# TeenyV4.net
KiCad netlist of a schematic drawn in EasyEDA Pro
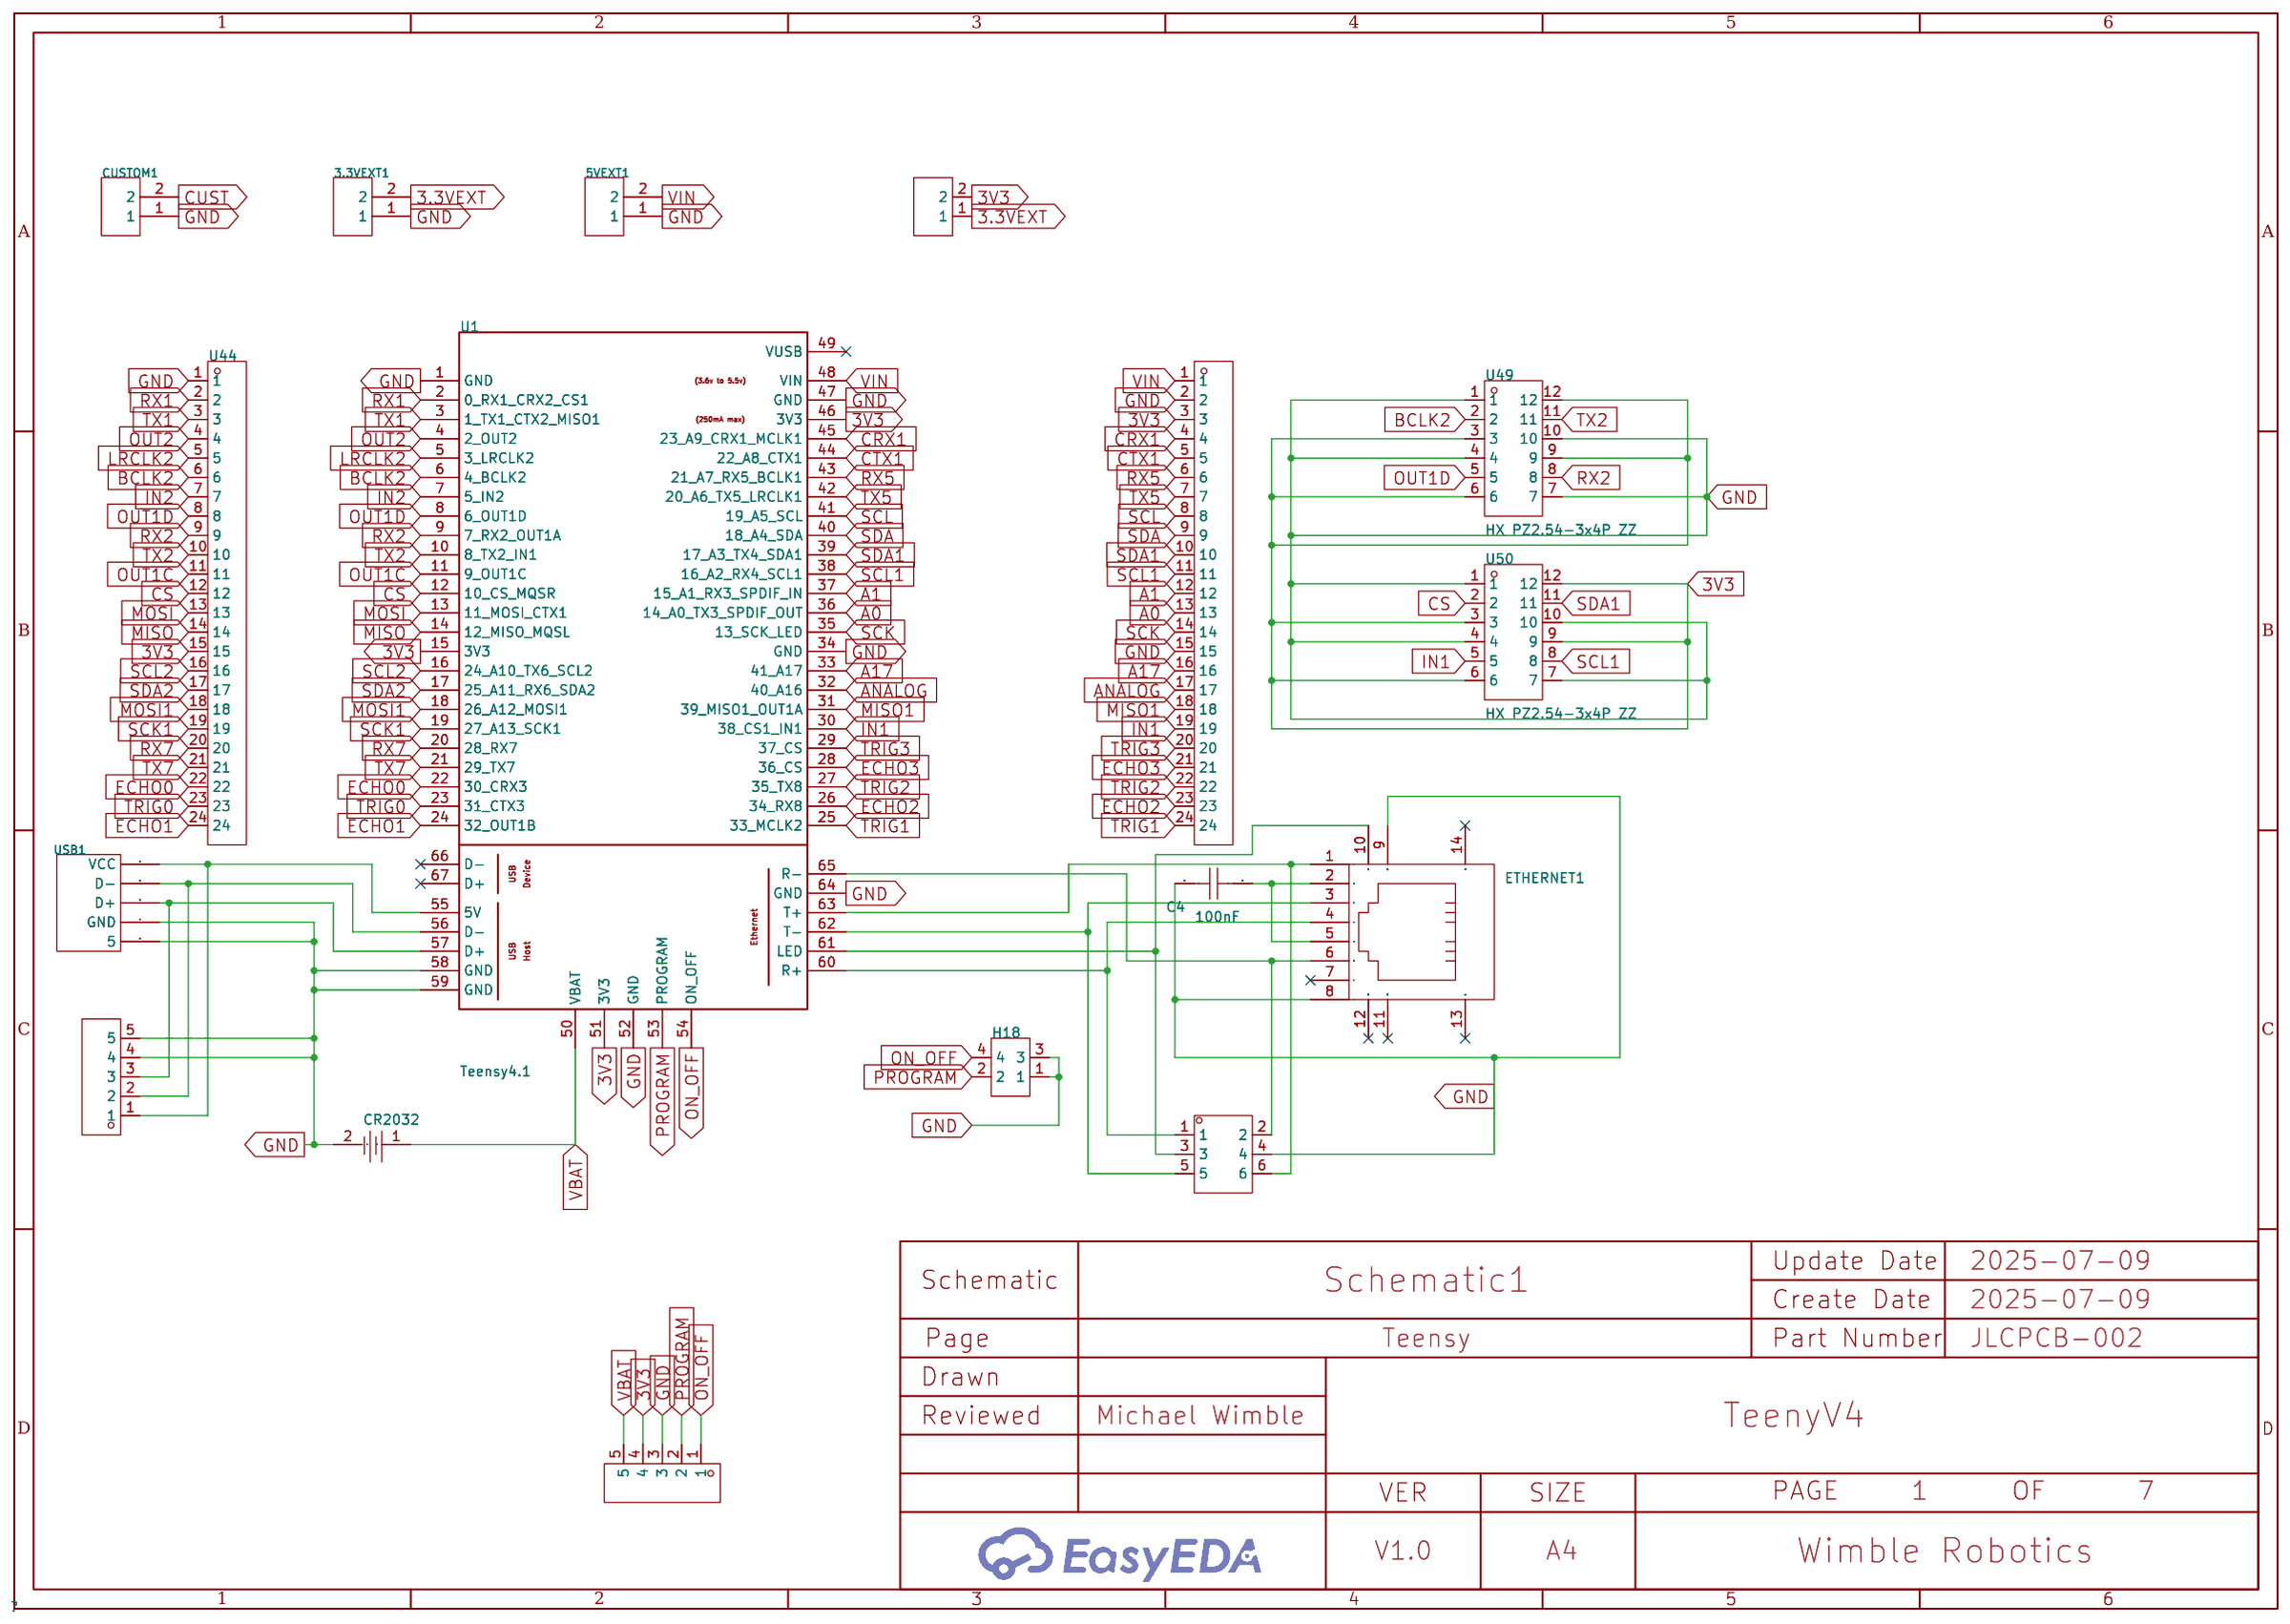
[diagram p0: Teensy]
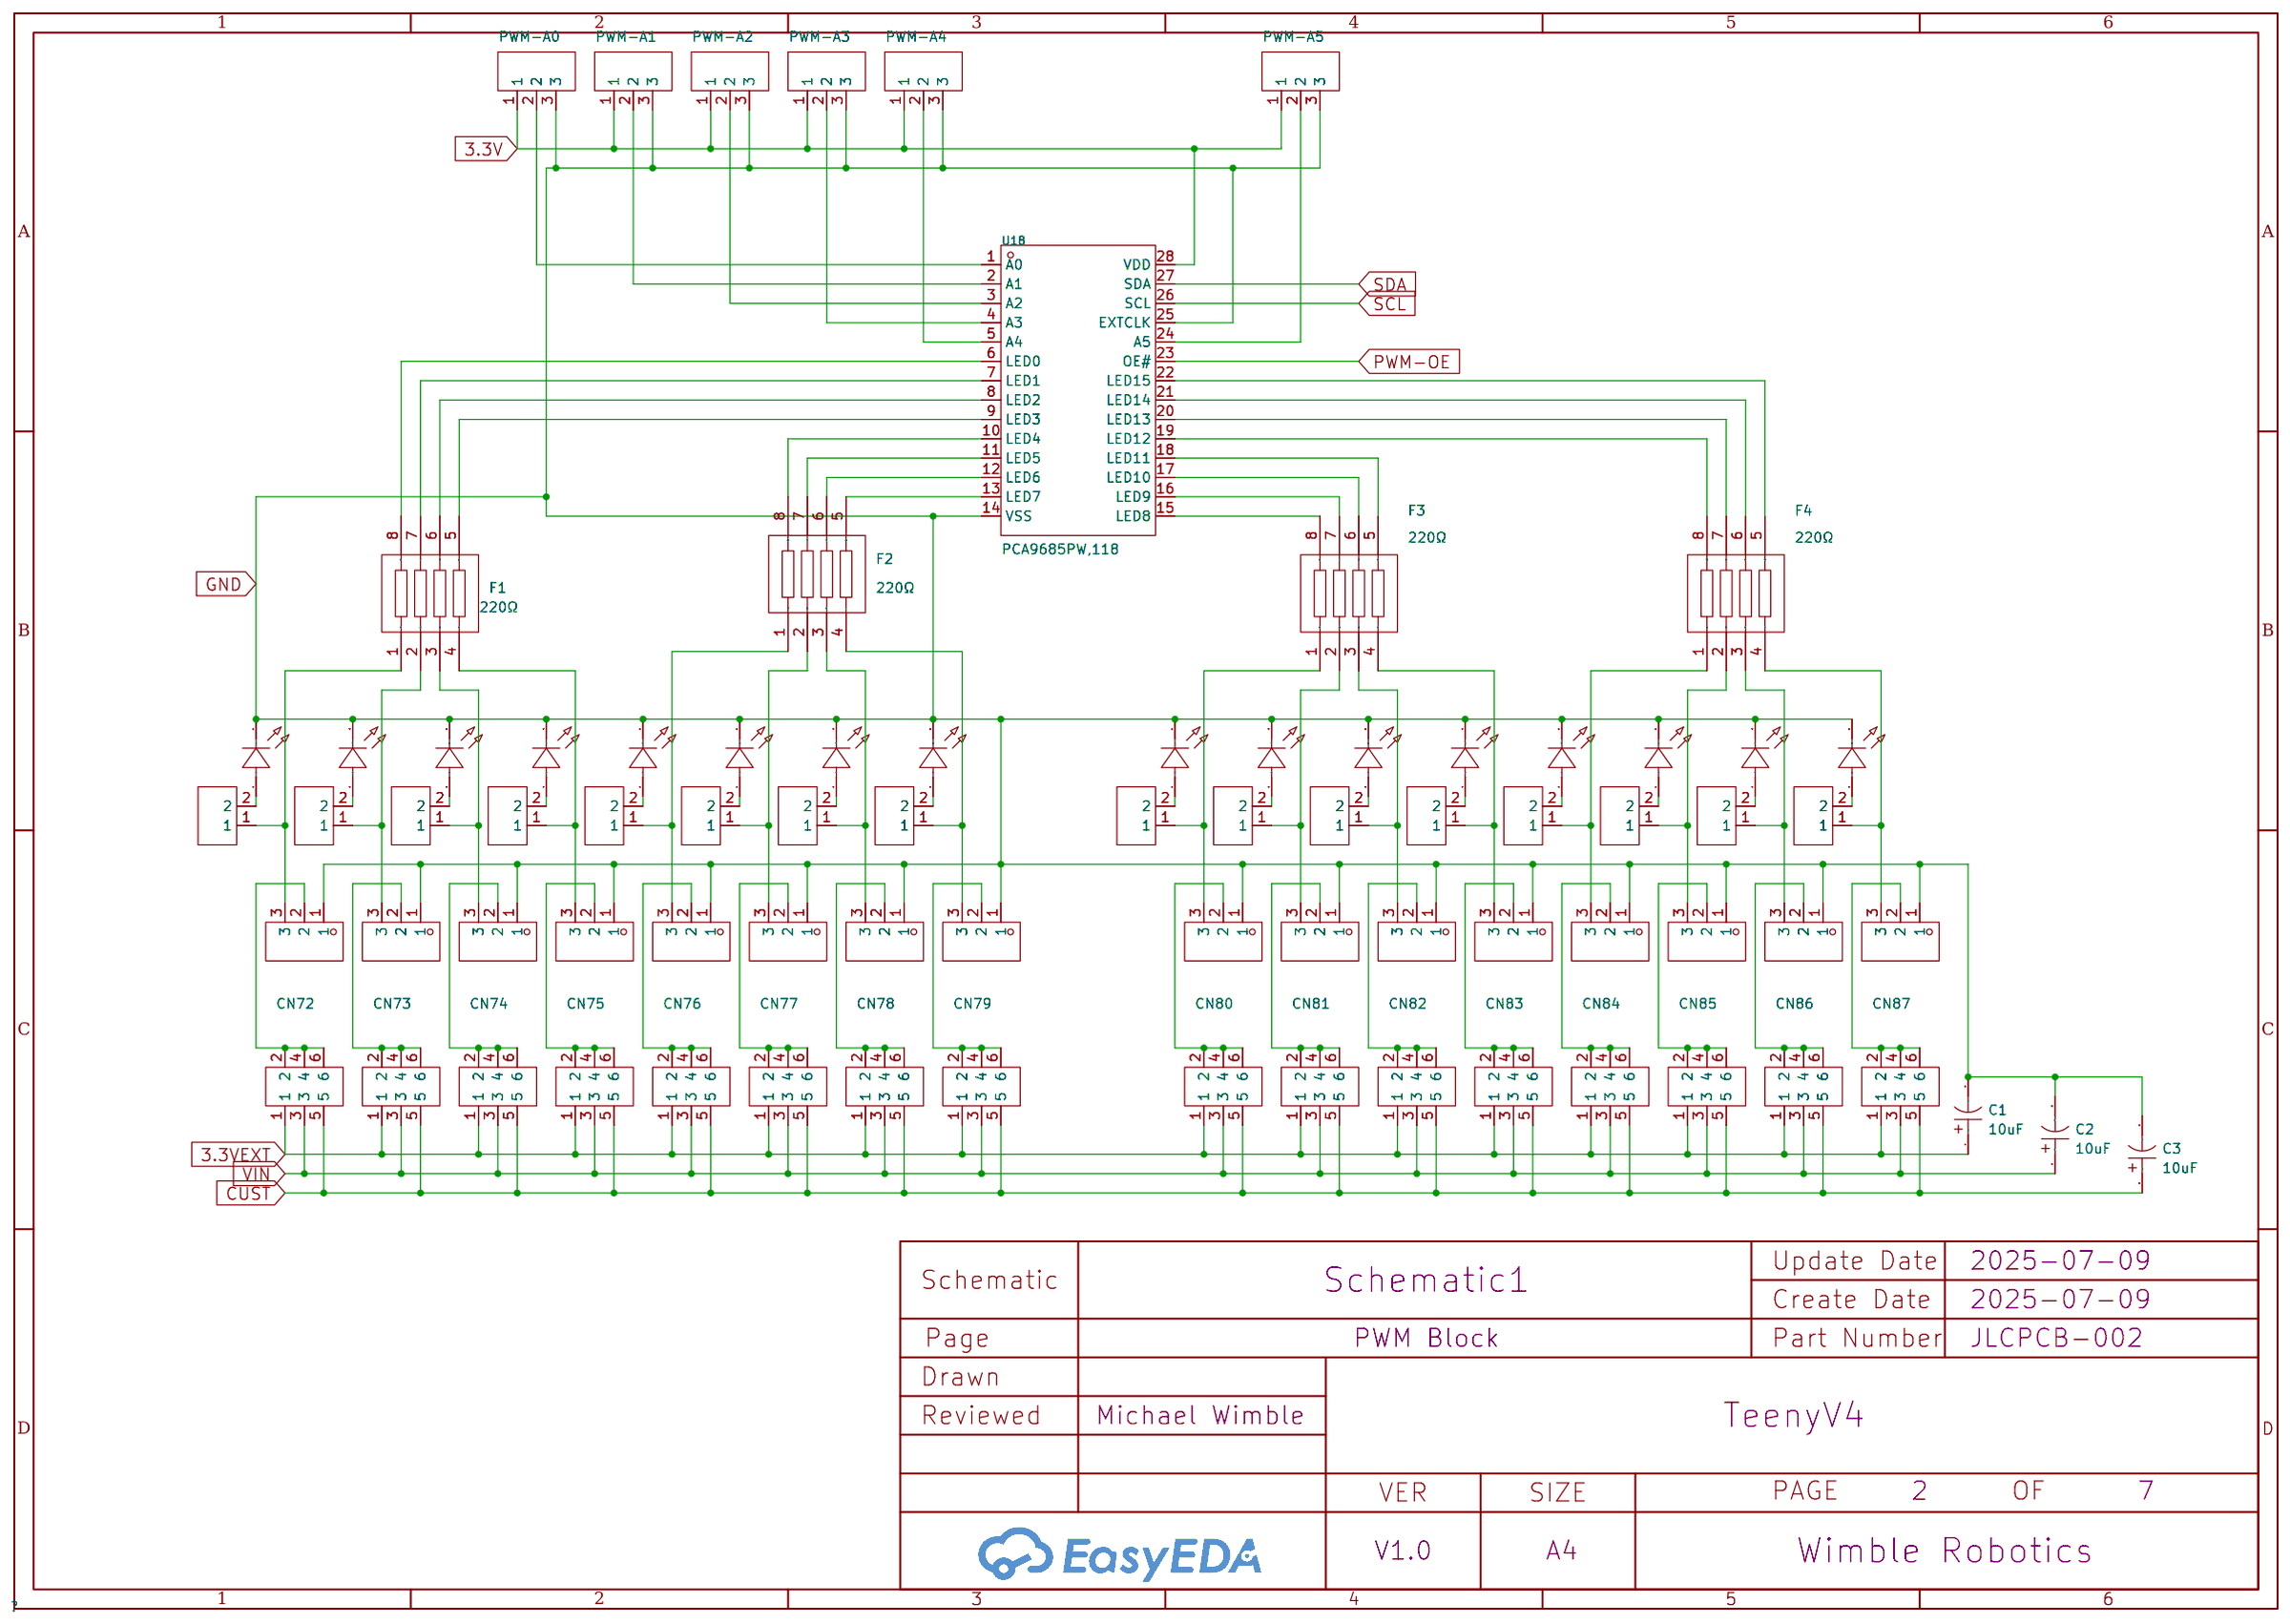
[diagram p1: PWM Block]
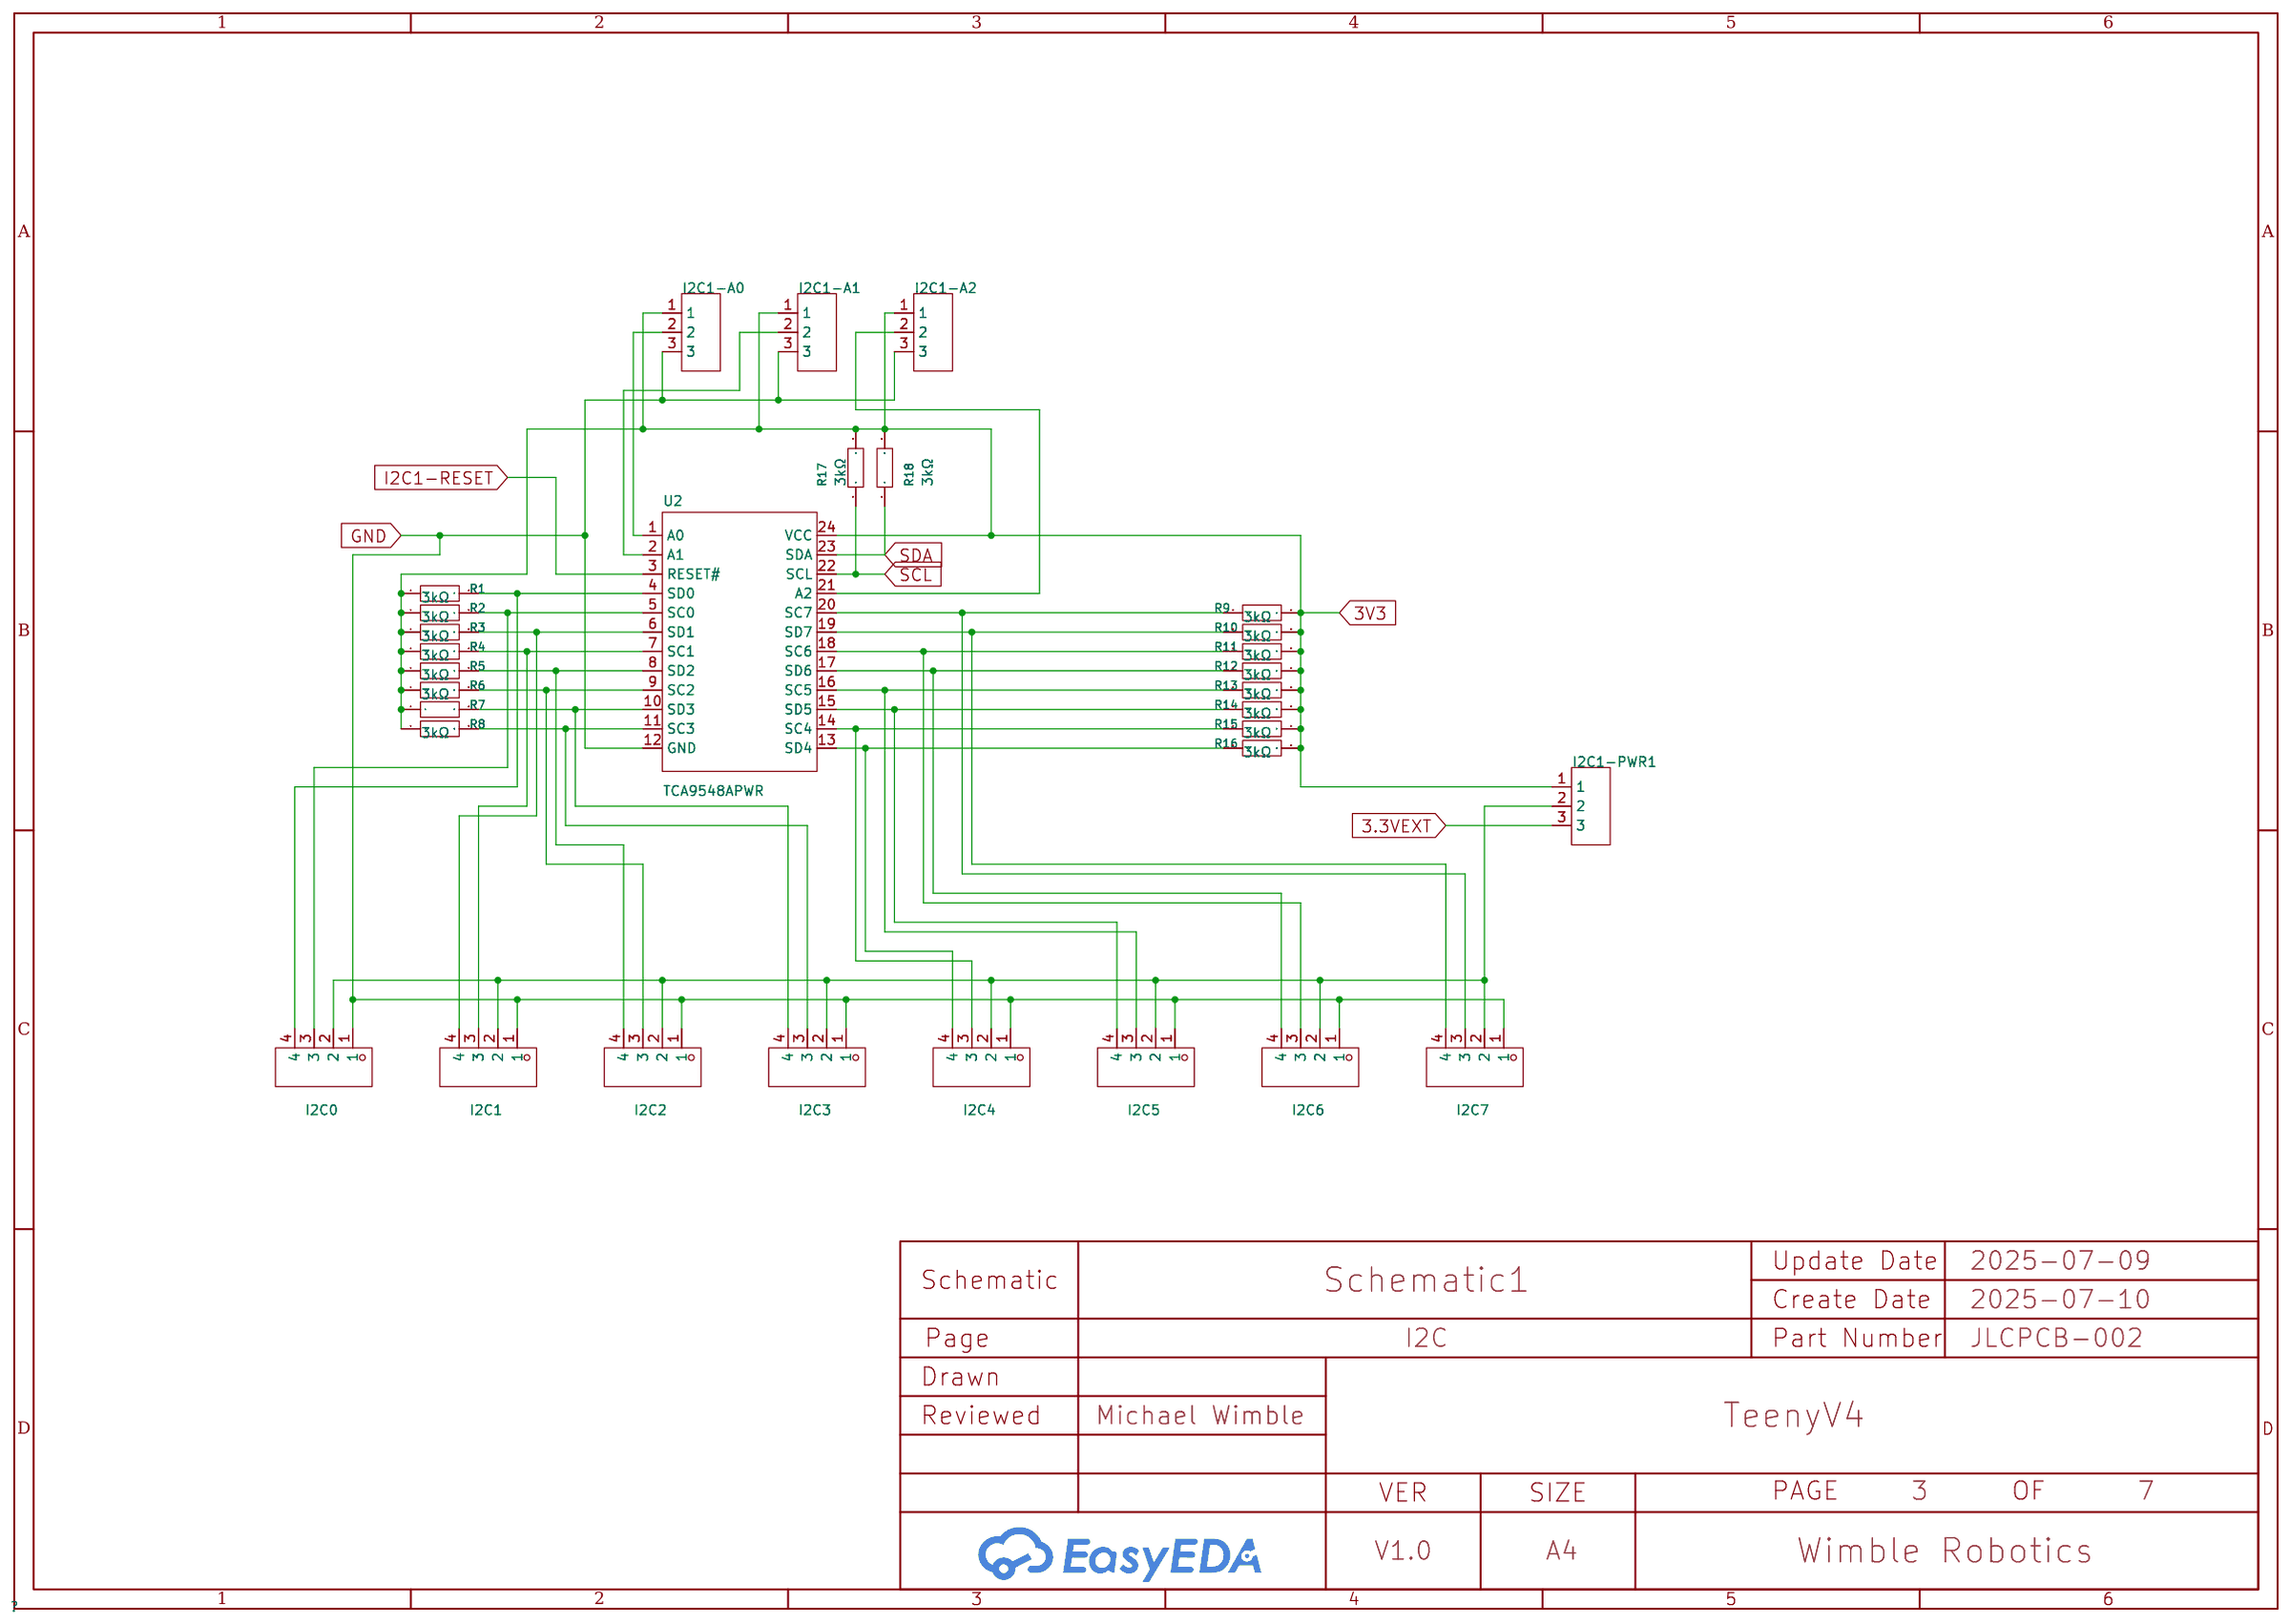
[diagram p2: I2C]
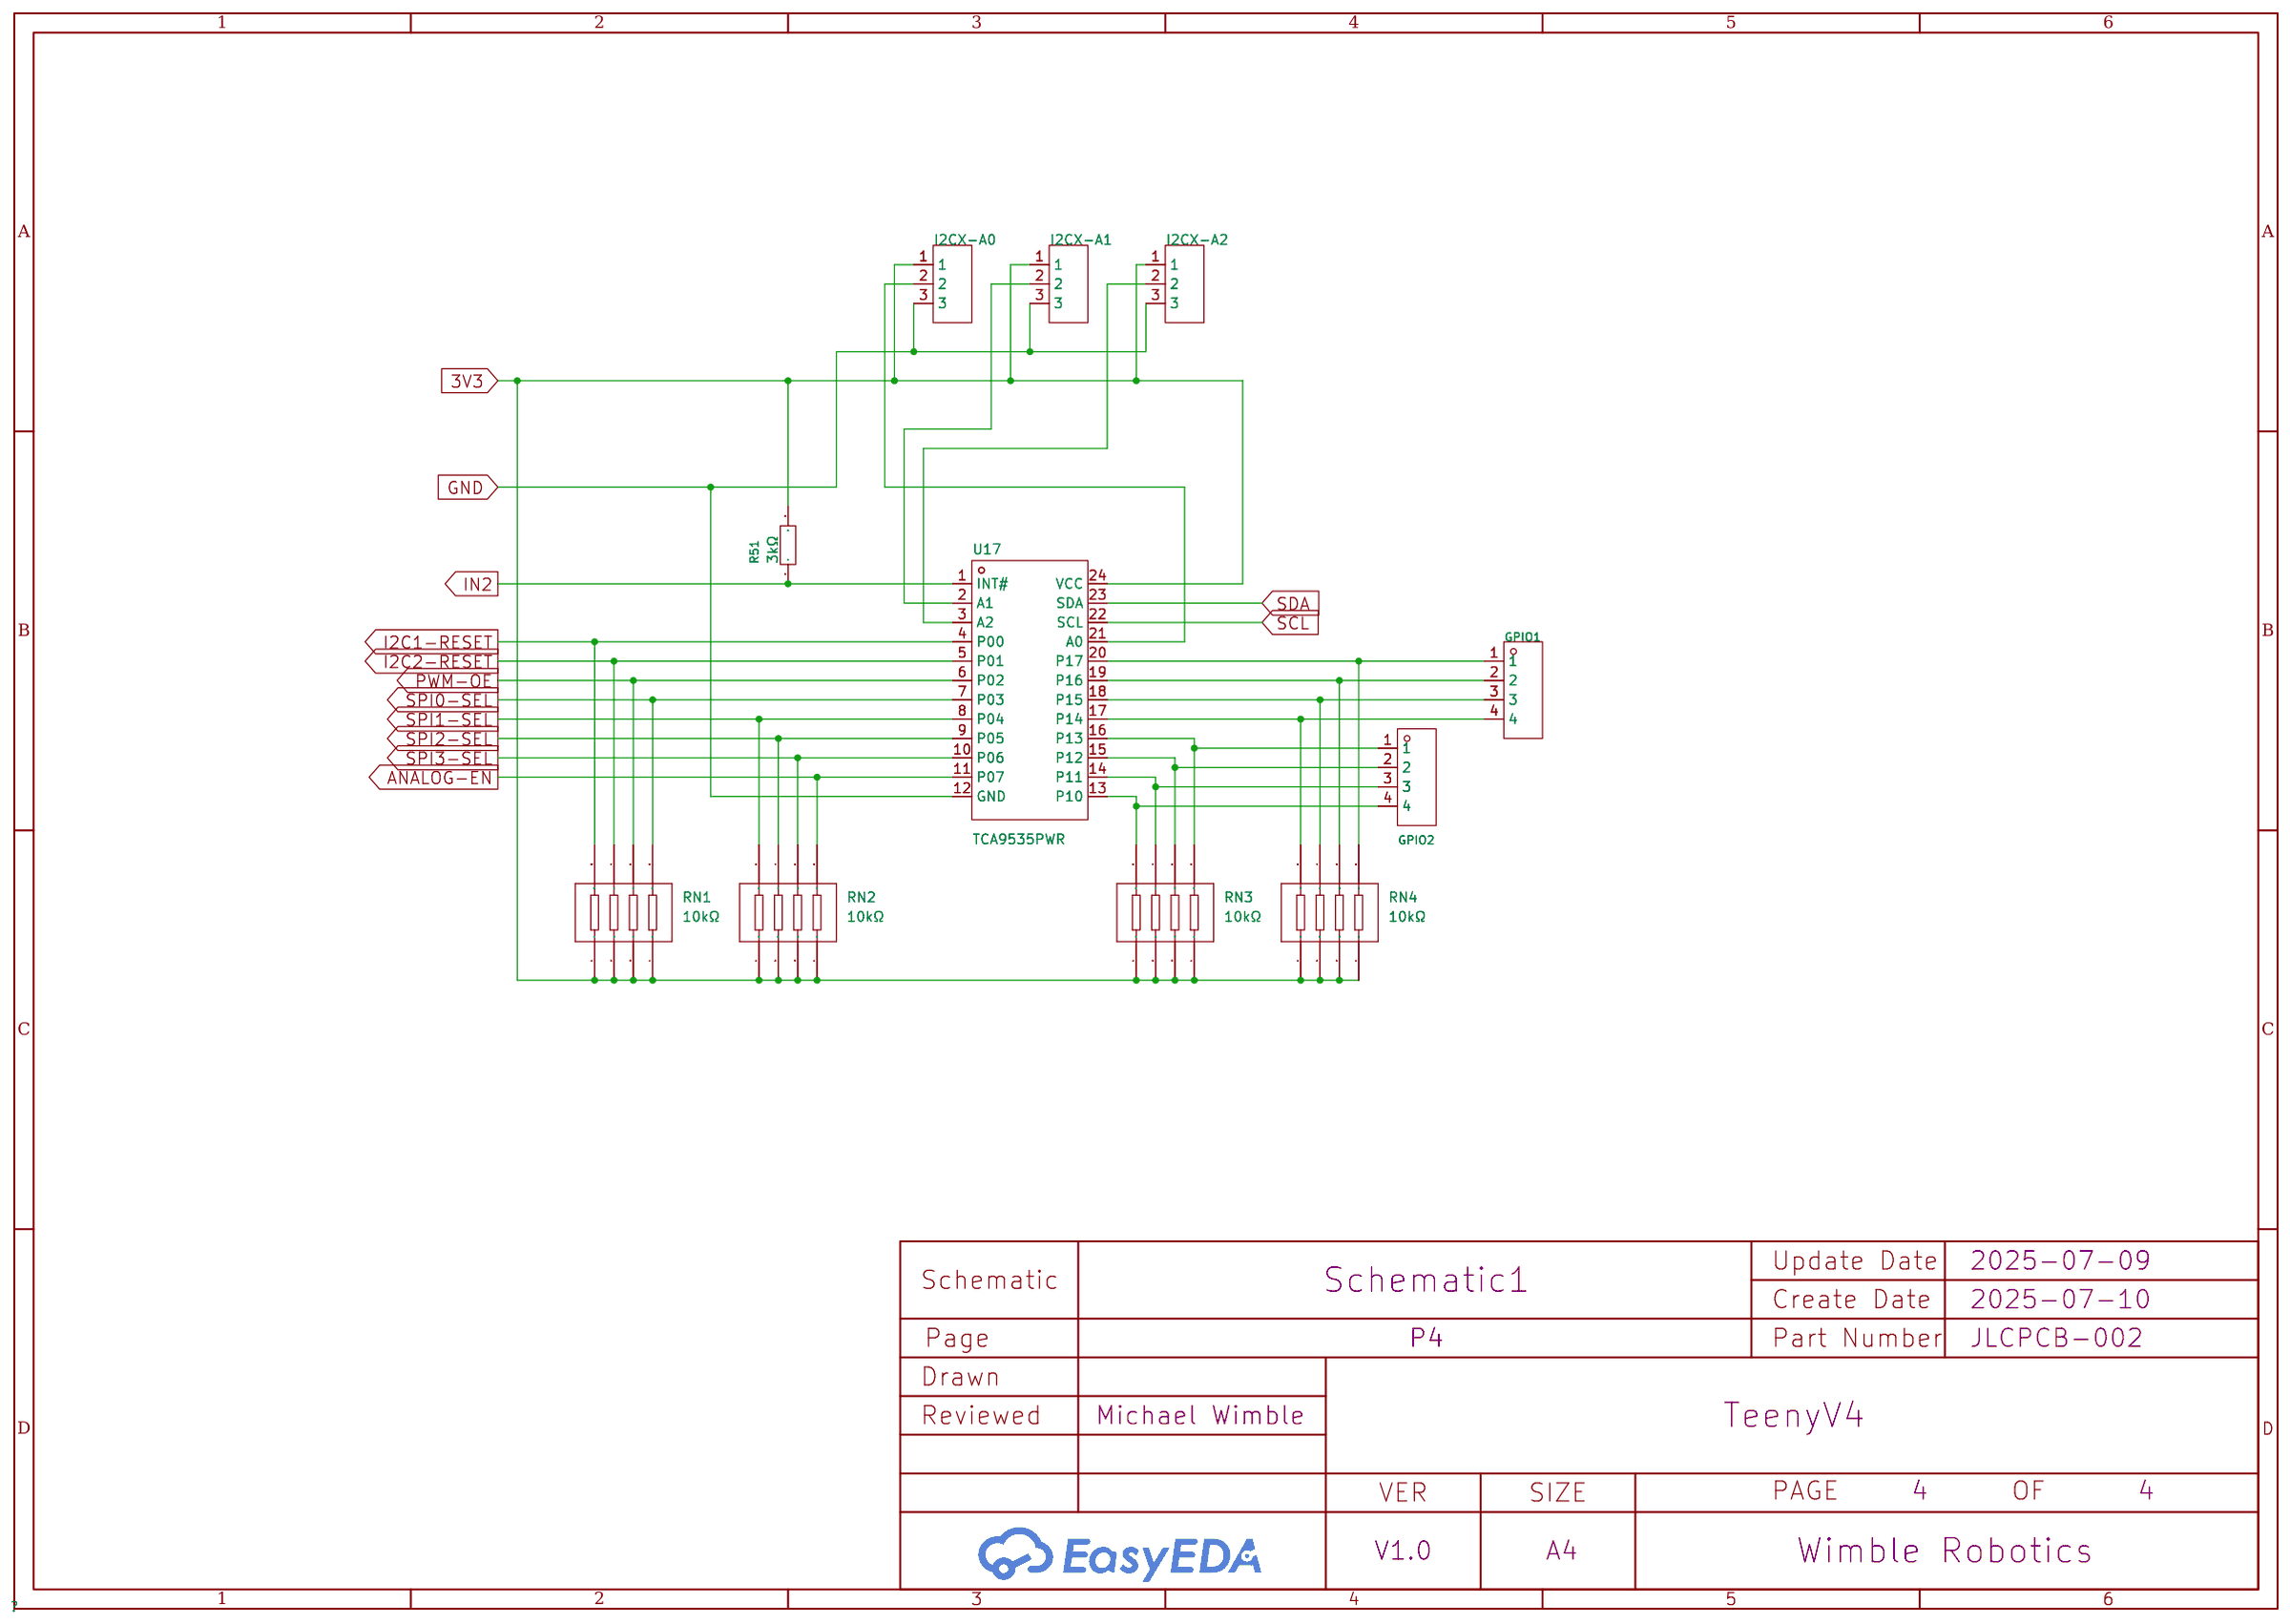
[diagram p3: GPIO]
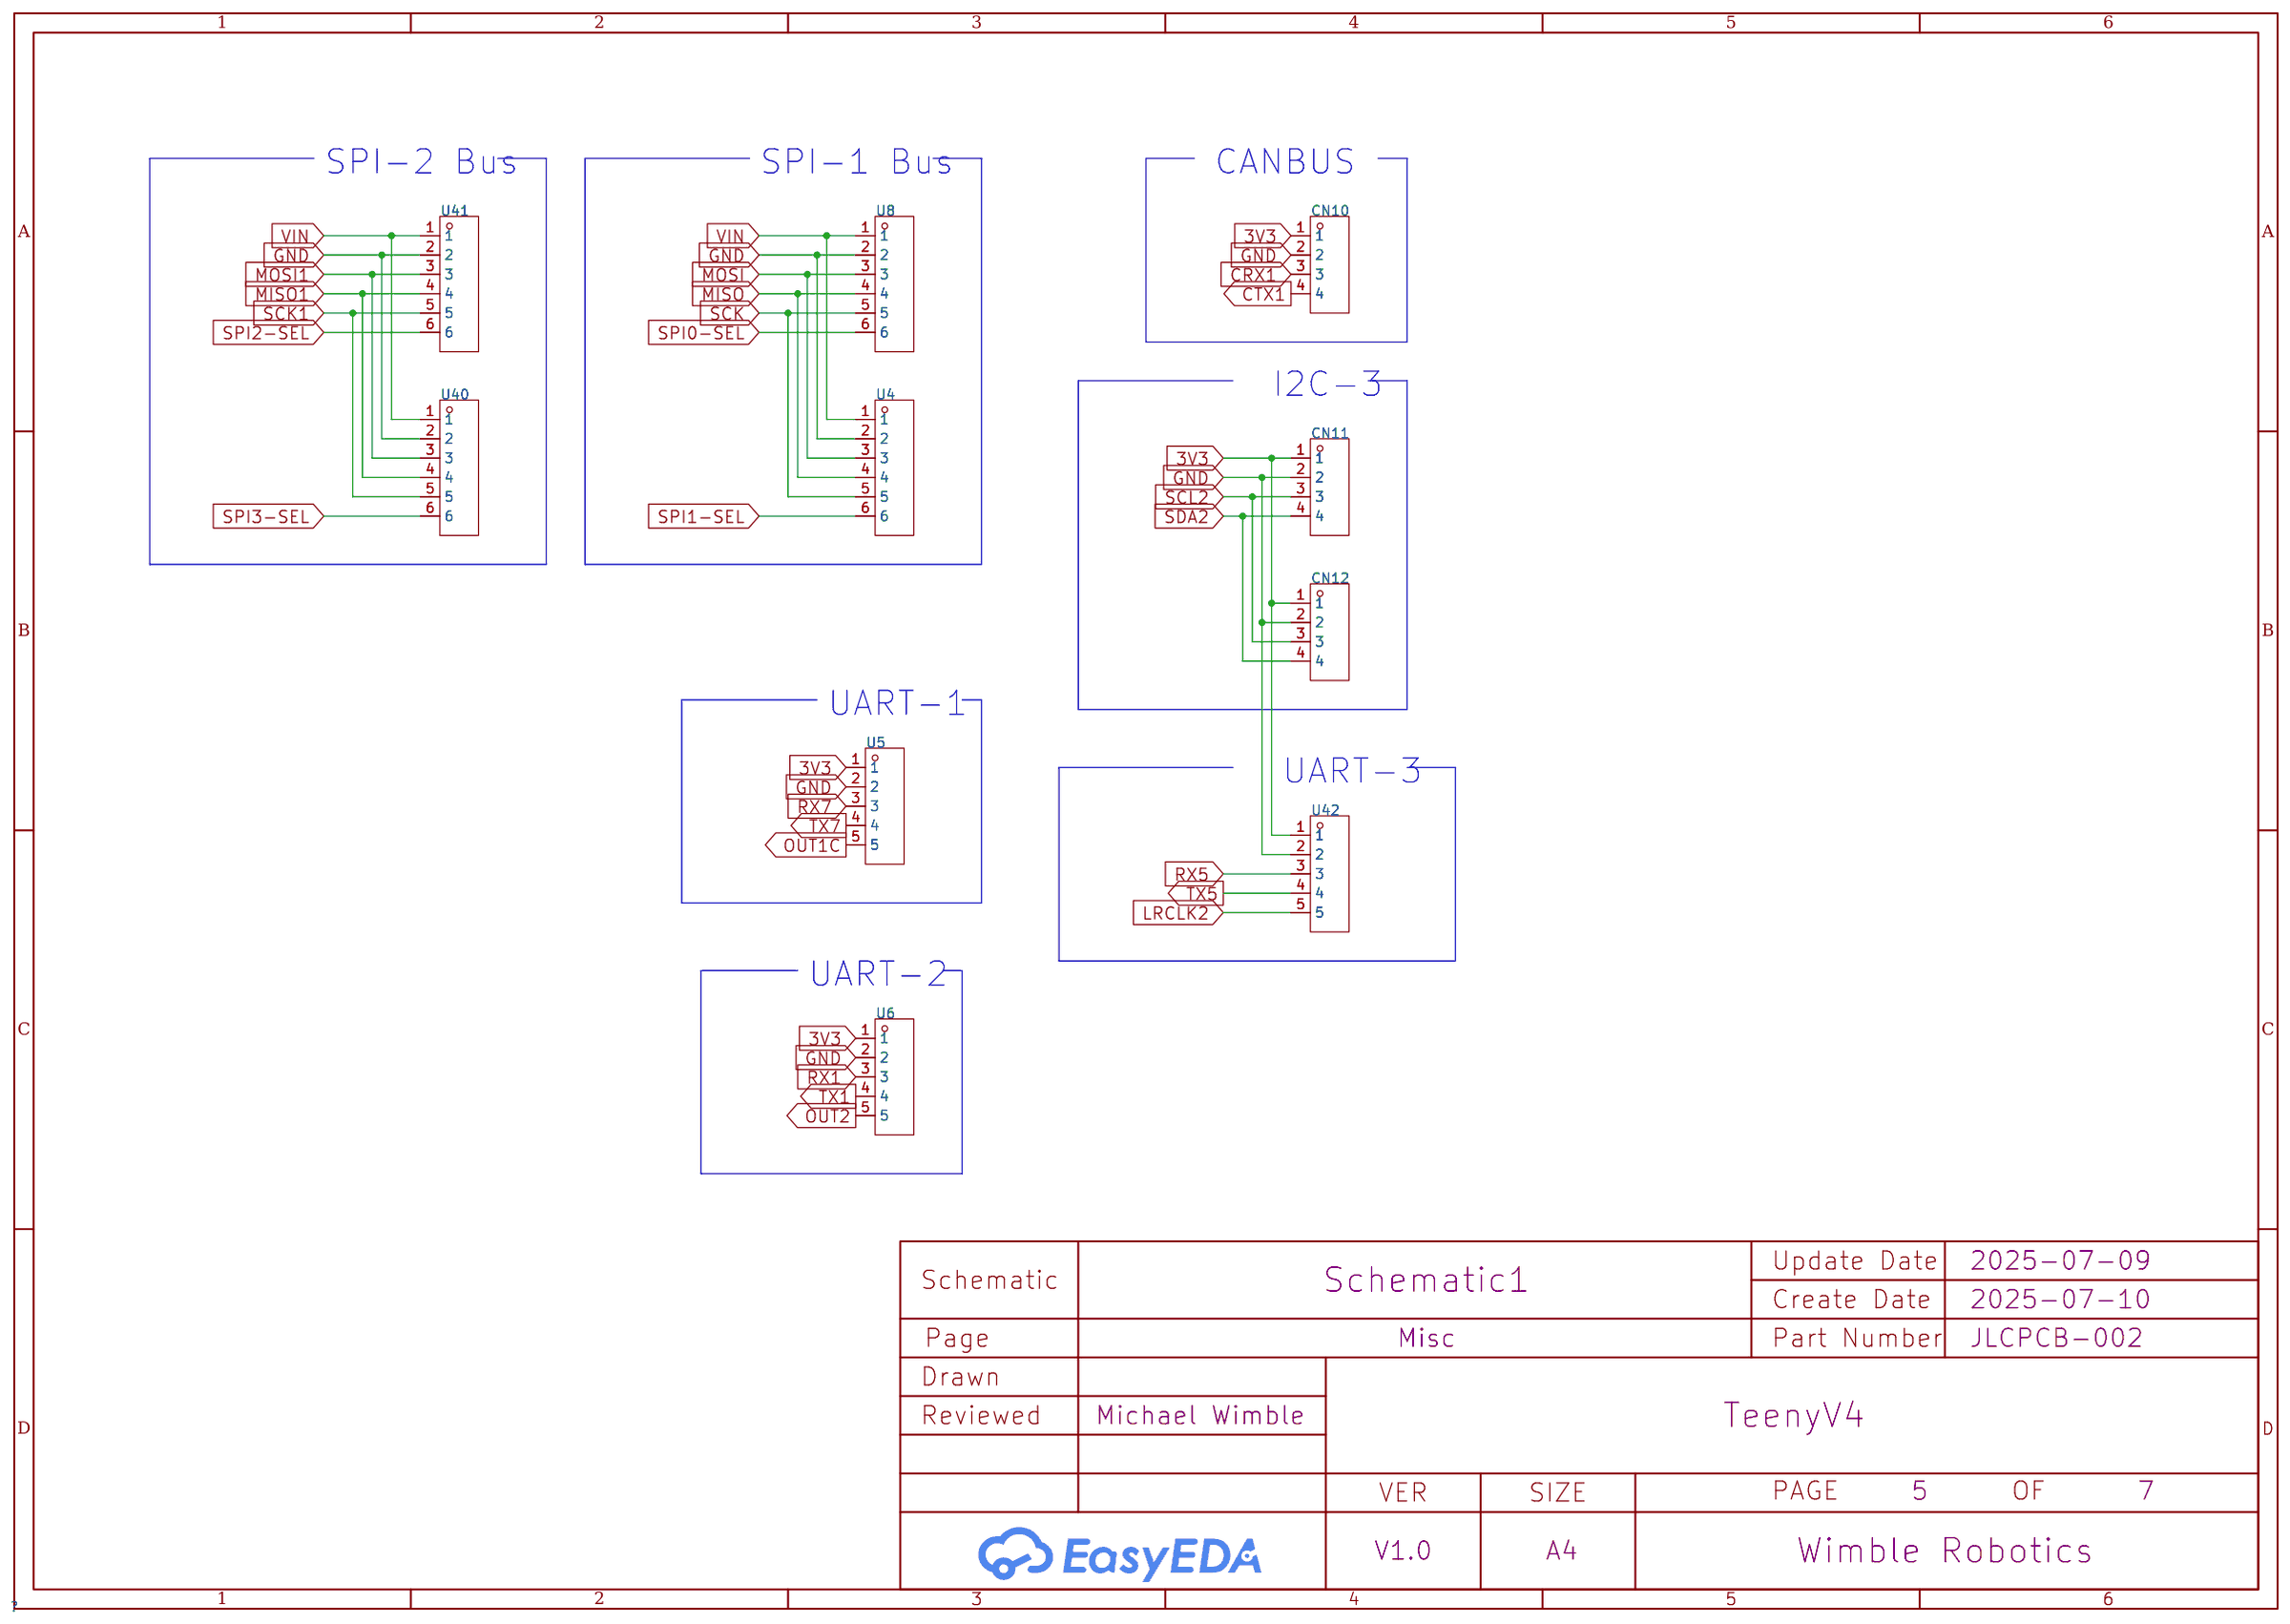
[diagram p4: Misc]
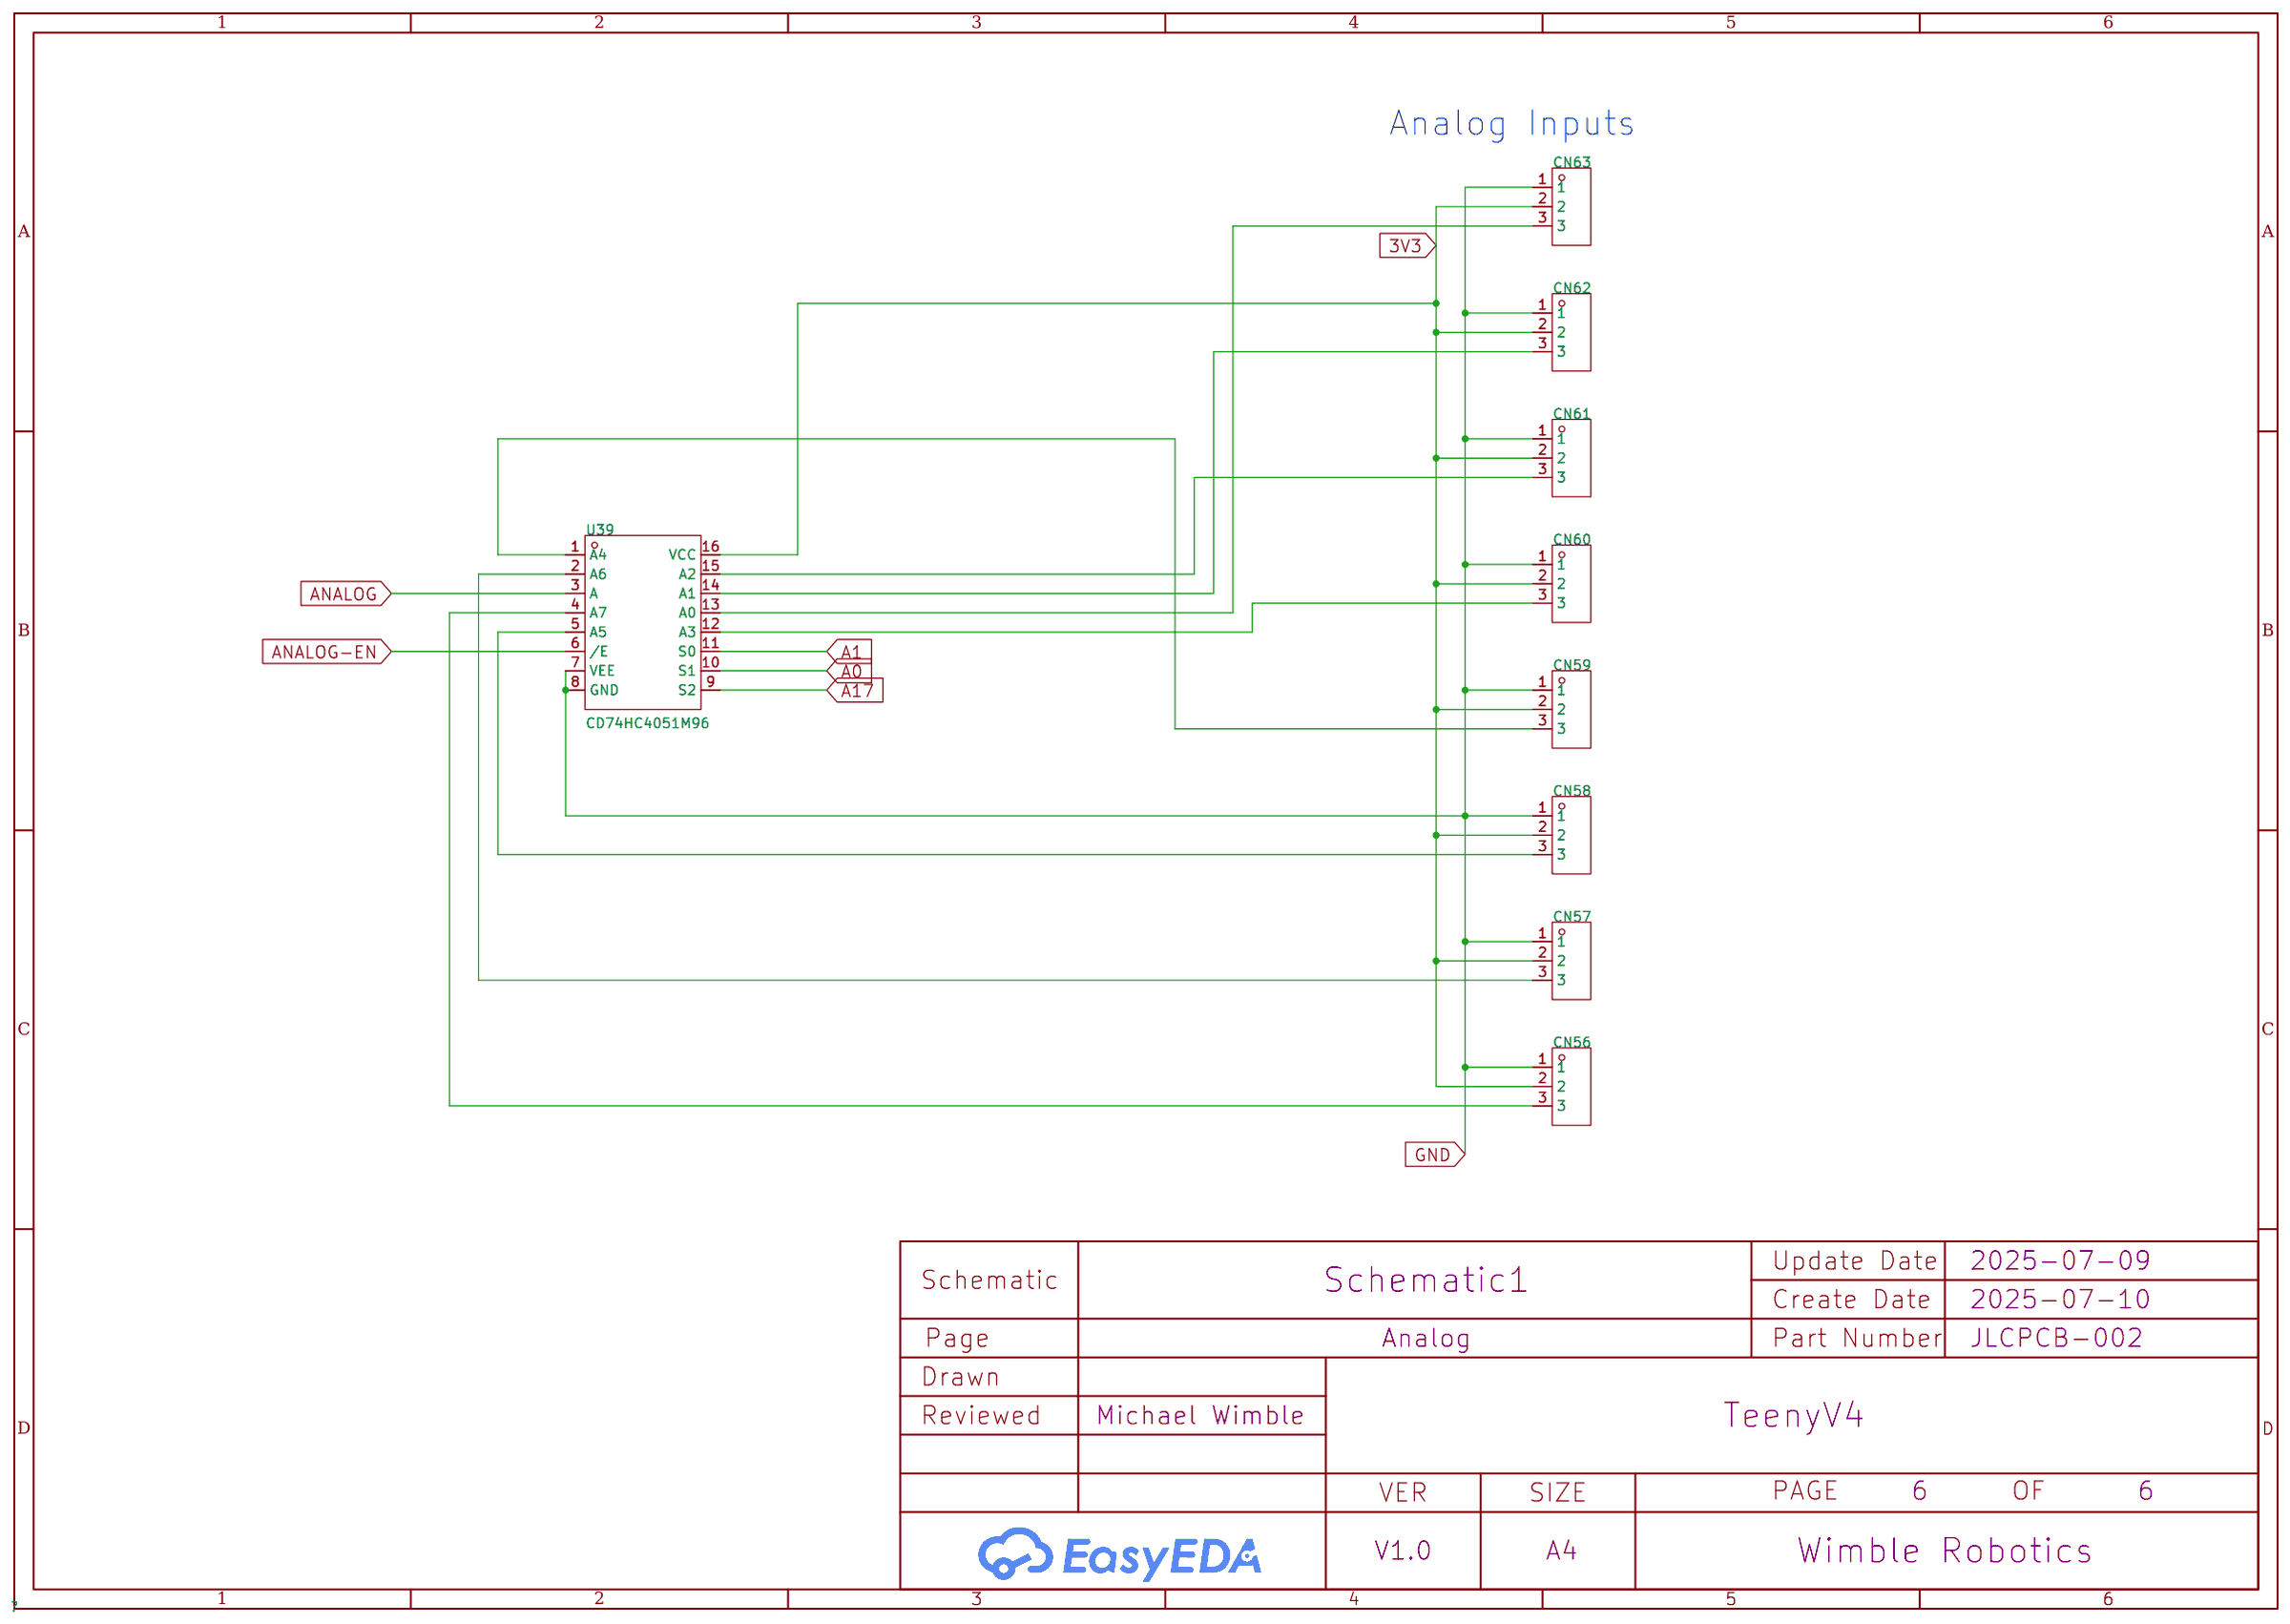
[diagram p5: Analog]
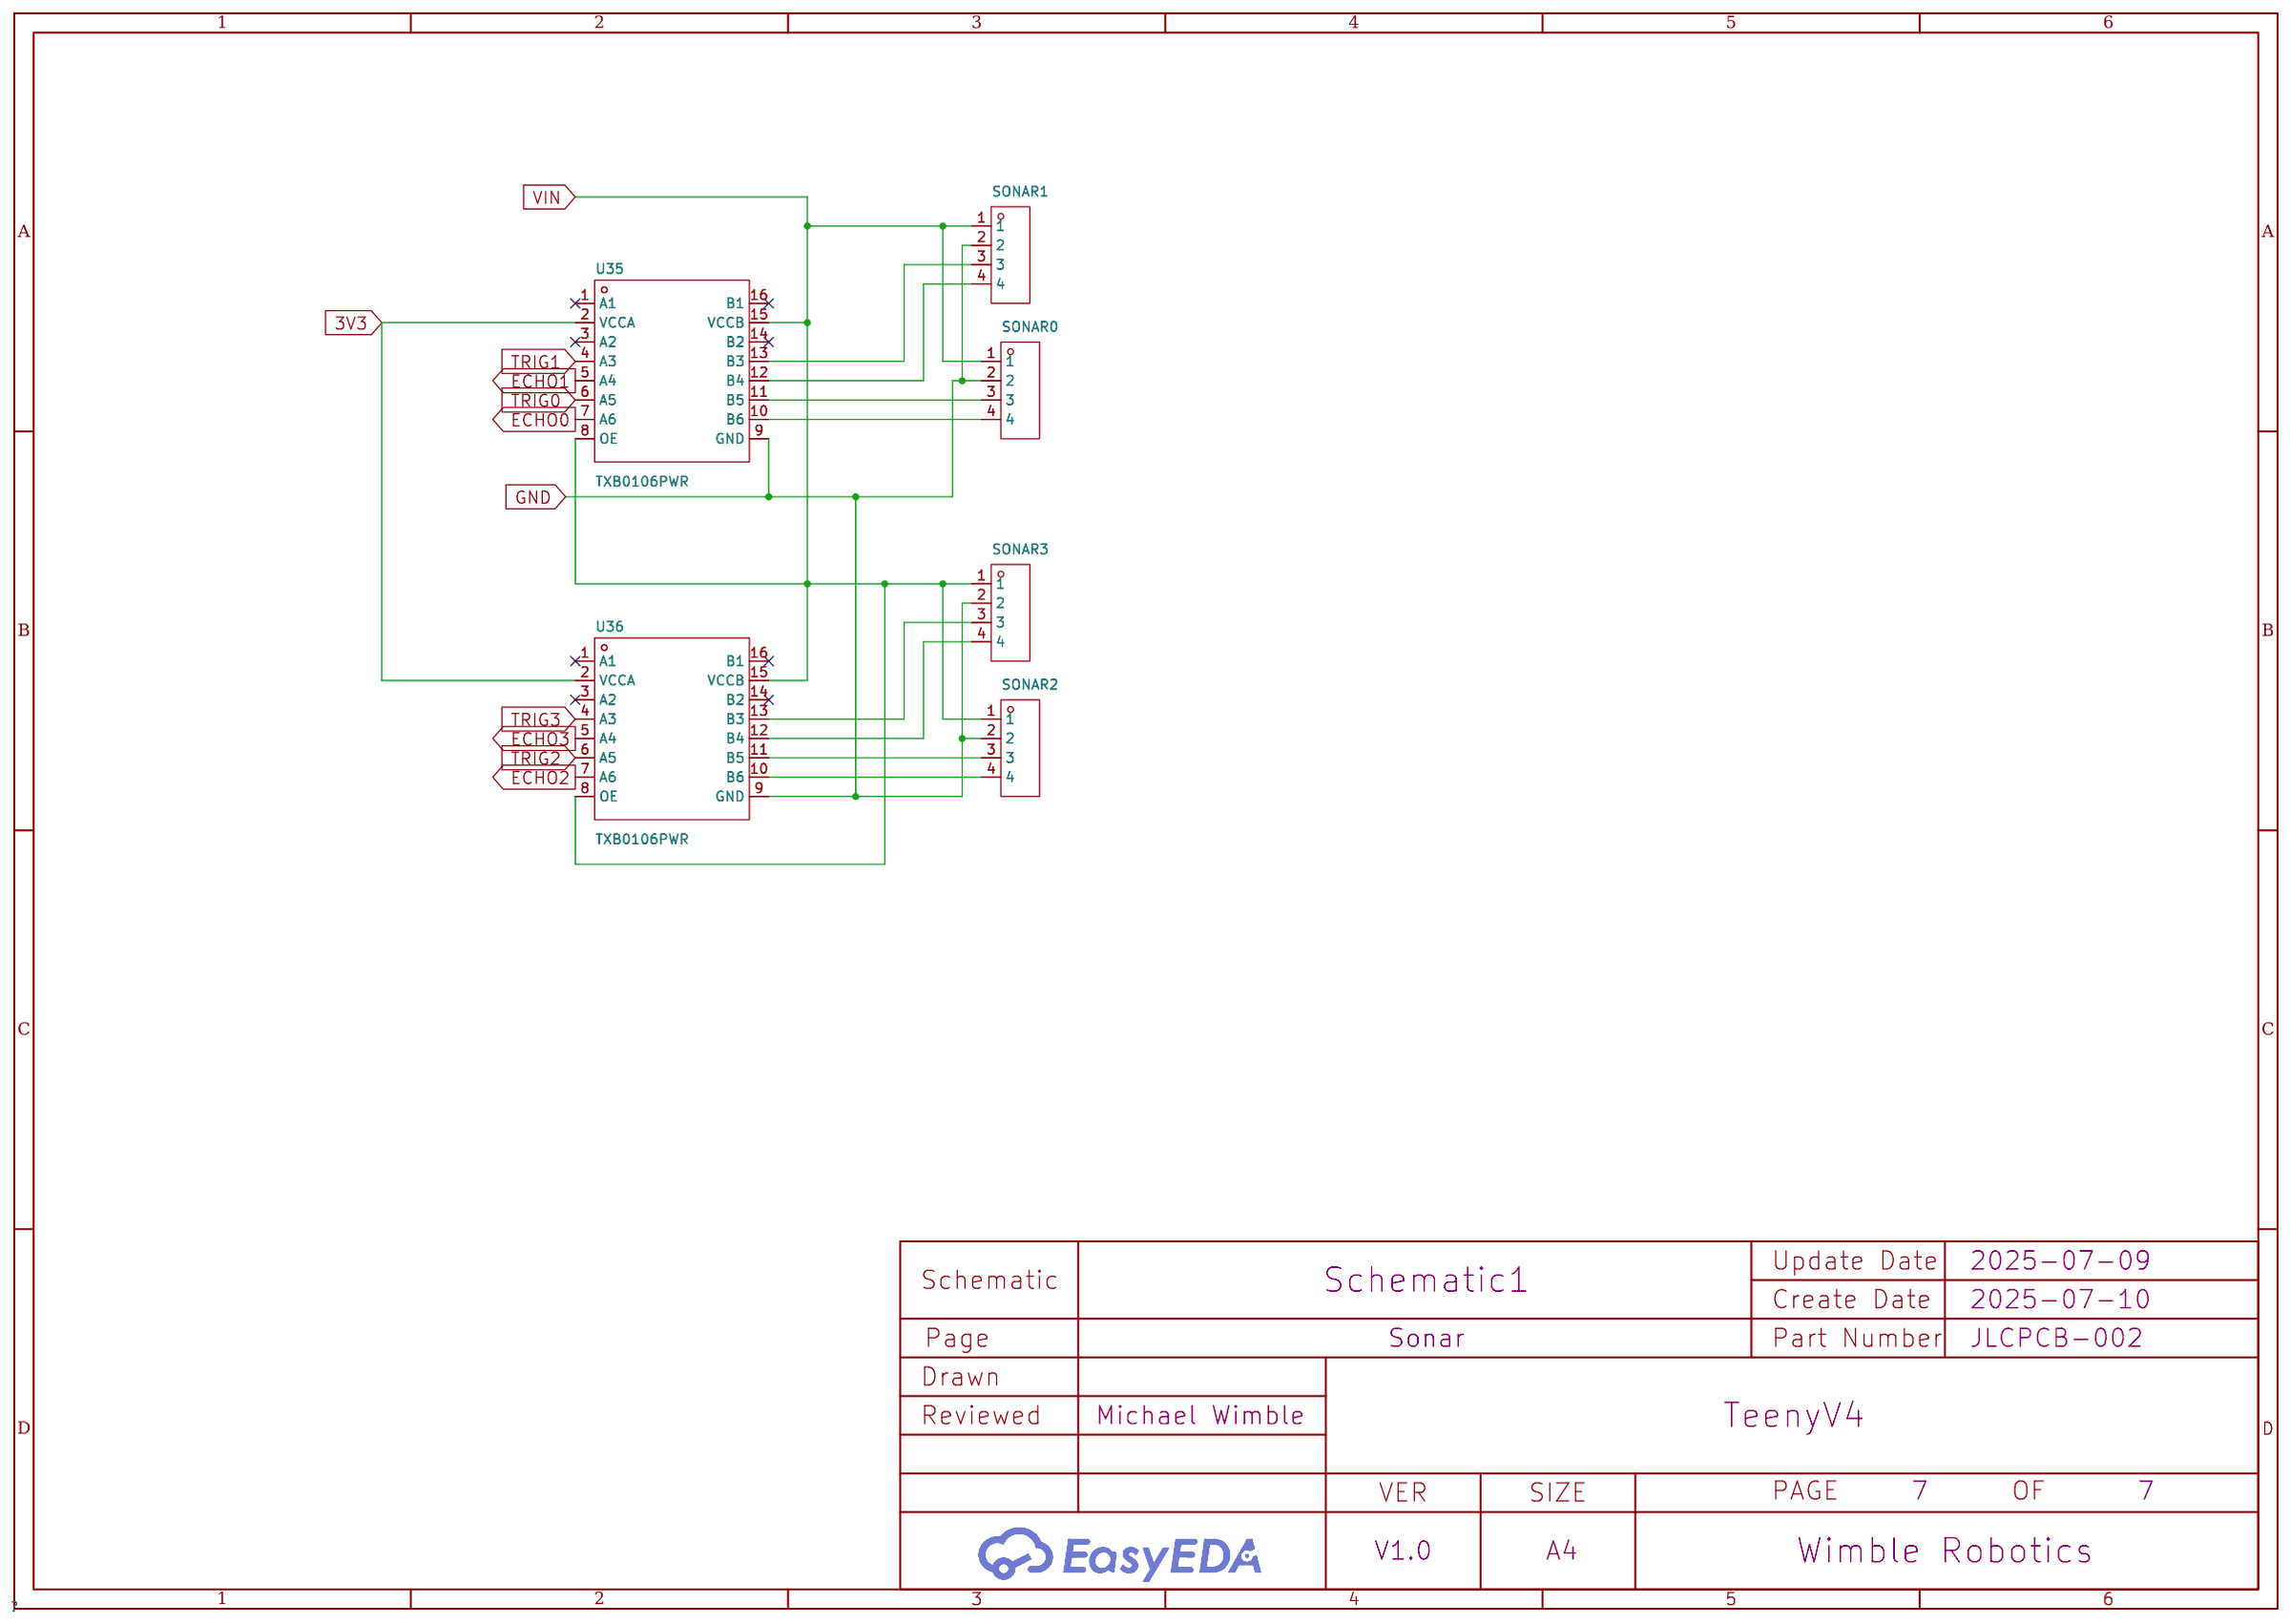
[diagram p6: Sonar]

(export (version "E")
  (design (tool "Eeschema 10.0.6"))
  (components
    (comp (ref "3.3VEXT1")
      (value "WJ127-5.0-2P")
      (footprint "easyedapro:CONN-TH_2P-P5.00_CPC3703CTR")
      (fields (field (name "Manufacturer") "KANGNEX(康奈克斯电气)"))
      (libsource (lib "easyedapro") (part "WJ127-5.0-2P"))
    )
    (comp (ref "5VEXT1")
      (value "WJ127-5.0-2P")
      (footprint "easyedapro:CONN-TH_2P-P5.00_CPC3703CTR")
      (fields (field (name "Manufacturer") "KANGNEX(康奈克斯电气)"))
      (libsource (lib "easyedapro") (part "WJ127-5.0-2P"))
    )
    (comp (ref "C4")
      (value "100nF")
      (footprint "easyedapro:C0805")
      (description "Capacitance:100nF Tolerance:±10% Tolerance:±10% Voltage Rating:50V Temperature Coefficient:-")
      (fields
        (field (name "Manufacturer Part") "CT41G-0805-2X1-50V-0.1μF-K(N)")
        (field (name "Manufacturer") "TORCH(火炬)")
      )
      (libsource (lib "easyedapro") (part "CT41G-0805-2X1-50V-0.1UF-K(N)"))
    )
    (comp (ref "CR2032")
      (value "CR2032-BS-6")
      (footprint "easyedapro:BAT-TH_CR2032-BS-6-1")
      (fields (field (name "Manufacturer") "LX(连欣科技)"))
      (libsource (lib "easyedapro") (part "CR2032-BS-6"))
    )
    (comp (ref "CUSTOM1")
      (value "WJ127-5.0-2P")
      (footprint "easyedapro:CONN-TH_2P-P5.00_CPC3703CTR")
      (fields (field (name "Manufacturer") "KANGNEX(康奈克斯电气)"))
      (libsource (lib "easyedapro") (part "WJ127-5.0-2P"))
    )
    (comp (ref "ETHERNET1")
      (value "J1B1211CCD")
      (footprint "easyedapro:RJ45-TH_J1B1211CCD")
      (fields (field (name "Manufacturer") "WIZNET"))
      (libsource (lib "easyedapro") (part "J1B1211CCD"))
    )
    (comp (ref "H18")
      (value "HX PZ2.54-2x2P ZZ")
      (footprint "easyedapro:HDR-TH_HX-PZ2.54-2X2P-ZZ")
      (fields (field (name "Manufacturer") "hanxia(韩下)"))
      (libsource (lib "easyedapro") (part "HX PZ2.54-2X2P ZZ"))
    )
    (comp (ref "H19")
      (value "PH-00013")
      (footprint "easyedapro:HDR-TH_2P-P2.54-V-M-R2-C1-S2.54")
      (fields (field (name "Manufacturer") "Liansheng(连盛)"))
      (libsource (lib "easyedapro") (part "PH-00013"))
    )
    (comp (ref "U1")
      (value "Teensy4.1")
      (footprint "easyedapro:Teensy41KiCad")
      (libsource (lib "easyedapro") (part "Teensy4.1"))
    )
    (comp (ref "U43")
      (value "HC-PM254-8.5H-1x24PZ")
      (footprint "easyedapro:HDR-TH_24P-P2.54-V-F")
      (fields (field (name "Manufacturer") "HC(虹成电子)"))
      (libsource (lib "easyedapro") (part "HC-PM254-8.5H-1X24PZ"))
    )
    (comp (ref "U44")
      (value "HC-PM254-8.5H-1x24PZ")
      (footprint "easyedapro:HDR-TH_24P-P2.54-V-F")
      (fields (field (name "Manufacturer") "HC(虹成电子)"))
      (libsource (lib "easyedapro") (part "HC-PM254-8.5H-1X24PZ"))
    )
    (comp (ref "U46")
      (value "PM2.54-1*5")
      (footprint "easyedapro:HDR-TH_5P-P2.54-V-F")
      (fields (field (name "Manufacturer") "ZHOURI(洲日)"))
      (libsource (lib "easyedapro") (part "PM2.54-1*5"))
    )
    (comp (ref "U47")
      (value "2.0-2*3P母")
      (footprint "easyedapro:HDR-TH_6P-P2.00-V-F-R2-C3-S2.00")
      (fields (field (name "Manufacturer") "BOOMELE(博穆精密)"))
      (libsource (lib "easyedapro") (part "2*3P"))
    )
    (comp (ref "U48")
      (value "PM2.54-1*5")
      (footprint "easyedapro:HDR-TH_5P-P2.54-V-F")
      (fields (field (name "Manufacturer") "ZHOURI(洲日)"))
      (libsource (lib "easyedapro") (part "PM2.54-1*5"))
    )
    (comp (ref "U49")
      (value "HX PZ2.54-3x4P ZZ")
      (footprint "easyedapro:HDR-TH_12P-P2.54-V-M-R3-C4-S2.54")
      (fields (field (name "Manufacturer") "hanxia(韩下)"))
      (libsource (lib "easyedapro") (part "HX PZ2.54-3X4P ZZ"))
    )
    (comp (ref "U50")
      (value "HX PZ2.54-3x4P ZZ")
      (footprint "easyedapro:HDR-TH_12P-P2.54-V-M-R3-C4-S2.54")
      (fields (field (name "Manufacturer") "hanxia(韩下)"))
      (libsource (lib "easyedapro") (part "HX PZ2.54-3X4P ZZ"))
    )
    (comp (ref "USB1")
      (value "904-131A2032S10100")
      (footprint "easyedapro:USB-A-SMD_FUS270-FSBW5K")
      (fields (field (name "Manufacturer") "精拓金"))
      (libsource (lib "easyedapro") (part "YJ-USB-AF-SMT-01"))
    )
    (comp (ref "C1")
      (value "10uF")
      (footprint "easyedapro:CAP-SMD_BD4.0-L4.3-W4.3-LS5.0-FD")
      (fields
        (field (name "Manufacturer Part") "VT10UF16V167RV0128")
        (field (name "Manufacturer") "KNSCHA(科尼盛)")
      )
      (libsource (lib "easyedapro") (part "VT10UF16V167RV0128"))
    )
    (comp (ref "C2")
      (value "10uF")
      (footprint "easyedapro:CAP-SMD_BD4.0-L4.3-W4.3-LS5.0-FD")
      (fields
        (field (name "Manufacturer Part") "VT10UF16V167RV0128")
        (field (name "Manufacturer") "KNSCHA(科尼盛)")
      )
      (libsource (lib "easyedapro") (part "VT10UF16V167RV0128"))
    )
    (comp (ref "C3")
      (value "10uF")
      (footprint "easyedapro:CAP-SMD_BD4.0-L4.3-W4.3-LS5.0-FD")
      (fields
        (field (name "Manufacturer Part") "VT10UF16V167RV0128")
        (field (name "Manufacturer") "KNSCHA(科尼盛)")
      )
      (libsource (lib "easyedapro") (part "VT10UF16V167RV0128"))
    )
    (comp (ref "CN72")
      (value "ZX-XH2.54-3PZZ")
      (footprint "easyedapro:CONN-TH_3P-P2.54_2501S-3P")
      (fields (field (name "Manufacturer") "Megastar(兆星)"))
      (libsource (lib "easyedapro") (part "ZX-XH2.54-3PZZ"))
    )
    (comp (ref "CN73")
      (value "ZX-XH2.54-3PZZ")
      (footprint "easyedapro:CONN-TH_3P-P2.54_2501S-3P")
      (fields (field (name "Manufacturer") "Megastar(兆星)"))
      (libsource (lib "easyedapro") (part "ZX-XH2.54-3PZZ"))
    )
    (comp (ref "CN74")
      (value "ZX-XH2.54-3PZZ")
      (footprint "easyedapro:CONN-TH_3P-P2.54_2501S-3P")
      (fields (field (name "Manufacturer") "Megastar(兆星)"))
      (libsource (lib "easyedapro") (part "ZX-XH2.54-3PZZ"))
    )
    (comp (ref "CN75")
      (value "ZX-XH2.54-3PZZ")
      (footprint "easyedapro:CONN-TH_3P-P2.54_2501S-3P")
      (fields (field (name "Manufacturer") "Megastar(兆星)"))
      (libsource (lib "easyedapro") (part "ZX-XH2.54-3PZZ"))
    )
    (comp (ref "CN76")
      (value "ZX-XH2.54-3PZZ")
      (footprint "easyedapro:CONN-TH_3P-P2.54_2501S-3P")
      (fields (field (name "Manufacturer") "Megastar(兆星)"))
      (libsource (lib "easyedapro") (part "ZX-XH2.54-3PZZ"))
    )
    (comp (ref "CN77")
      (value "ZX-XH2.54-3PZZ")
      (footprint "easyedapro:CONN-TH_3P-P2.54_2501S-3P")
      (fields (field (name "Manufacturer") "Megastar(兆星)"))
      (libsource (lib "easyedapro") (part "ZX-XH2.54-3PZZ"))
    )
    (comp (ref "CN78")
      (value "ZX-XH2.54-3PZZ")
      (footprint "easyedapro:CONN-TH_3P-P2.54_2501S-3P")
      (fields (field (name "Manufacturer") "Megastar(兆星)"))
      (libsource (lib "easyedapro") (part "ZX-XH2.54-3PZZ"))
    )
    (comp (ref "CN79")
      (value "ZX-XH2.54-3PZZ")
      (footprint "easyedapro:CONN-TH_3P-P2.54_2501S-3P")
      (fields (field (name "Manufacturer") "Megastar(兆星)"))
      (libsource (lib "easyedapro") (part "ZX-XH2.54-3PZZ"))
    )
    (comp (ref "CN80")
      (value "ZX-XH2.54-3PZZ")
      (footprint "easyedapro:CONN-TH_3P-P2.54_2501S-3P")
      (fields (field (name "Manufacturer") "Megastar(兆星)"))
      (libsource (lib "easyedapro") (part "ZX-XH2.54-3PZZ"))
    )
    (comp (ref "CN81")
      (value "ZX-XH2.54-3PZZ")
      (footprint "easyedapro:CONN-TH_3P-P2.54_2501S-3P")
      (fields (field (name "Manufacturer") "Megastar(兆星)"))
      (libsource (lib "easyedapro") (part "ZX-XH2.54-3PZZ"))
    )
    (comp (ref "CN82")
      (value "ZX-XH2.54-3PZZ")
      (footprint "easyedapro:CONN-TH_3P-P2.54_2501S-3P")
      (fields (field (name "Manufacturer") "Megastar(兆星)"))
      (libsource (lib "easyedapro") (part "ZX-XH2.54-3PZZ"))
    )
    (comp (ref "CN83")
      (value "ZX-XH2.54-3PZZ")
      (footprint "easyedapro:CONN-TH_3P-P2.54_2501S-3P")
      (fields (field (name "Manufacturer") "Megastar(兆星)"))
      (libsource (lib "easyedapro") (part "ZX-XH2.54-3PZZ"))
    )
    (comp (ref "CN84")
      (value "ZX-XH2.54-3PZZ")
      (footprint "easyedapro:CONN-TH_3P-P2.54_2501S-3P")
      (fields (field (name "Manufacturer") "Megastar(兆星)"))
      (libsource (lib "easyedapro") (part "ZX-XH2.54-3PZZ"))
    )
    (comp (ref "CN85")
      (value "ZX-XH2.54-3PZZ")
      (footprint "easyedapro:CONN-TH_3P-P2.54_2501S-3P")
      (fields (field (name "Manufacturer") "Megastar(兆星)"))
      (libsource (lib "easyedapro") (part "ZX-XH2.54-3PZZ"))
    )
    (comp (ref "CN86")
      (value "ZX-XH2.54-3PZZ")
      (footprint "easyedapro:CONN-TH_3P-P2.54_2501S-3P")
      (fields (field (name "Manufacturer") "Megastar(兆星)"))
      (libsource (lib "easyedapro") (part "ZX-XH2.54-3PZZ"))
    )
    (comp (ref "CN87")
      (value "ZX-XH2.54-3PZZ")
      (footprint "easyedapro:CONN-TH_3P-P2.54_2501S-3P")
      (fields (field (name "Manufacturer") "Megastar(兆星)"))
      (libsource (lib "easyedapro") (part "ZX-XH2.54-3PZZ"))
    )
    (comp (ref "F1")
      (value "220Ω")
      (footprint "easyedapro:RES-ARRAY-SMD_0603-8P-L3.2-W1.6-TL")
      (fields (field (name "Manufacturer Part") "YC164-JR-07220RL") (field (name "Manufacturer") "YAGEO(国巨)"))
      (libsource (lib "easyedapro") (part "YC164-JR-07220RL"))
    )
    (comp (ref "F2")
      (value "220Ω")
      (footprint "easyedapro:RES-ARRAY-SMD_0603-8P-L3.2-W1.6-TL")
      (fields (field (name "Manufacturer Part") "YC164-JR-07220RL") (field (name "Manufacturer") "YAGEO(国巨)"))
      (libsource (lib "easyedapro") (part "YC164-JR-07220RL"))
    )
    (comp (ref "F3")
      (value "220Ω")
      (footprint "easyedapro:RES-ARRAY-SMD_0603-8P-L3.2-W1.6-TL")
      (fields (field (name "Manufacturer Part") "YC164-JR-07220RL") (field (name "Manufacturer") "YAGEO(国巨)"))
      (libsource (lib "easyedapro") (part "YC164-JR-07220RL"))
    )
    (comp (ref "F4")
      (value "220Ω")
      (footprint "easyedapro:RES-ARRAY-SMD_0603-8P-L3.2-W1.6-TL")
      (fields (field (name "Manufacturer Part") "YC164-JR-07220RL") (field (name "Manufacturer") "YAGEO(国巨)"))
      (libsource (lib "easyedapro") (part "YC164-JR-07220RL"))
    )
    (comp (ref "H2")
      (value "PH-00013")
      (footprint "easyedapro:HDR-TH_2P-P2.54-V-M-R2-C1-S2.54")
      (fields (field (name "Manufacturer") "Liansheng(连盛)"))
      (libsource (lib "easyedapro") (part "PH-00013"))
    )
    (comp (ref "H3")
      (value "PH-00013")
      (footprint "easyedapro:HDR-TH_2P-P2.54-V-M-R2-C1-S2.54")
      (fields (field (name "Manufacturer") "Liansheng(连盛)"))
      (libsource (lib "easyedapro") (part "PH-00013"))
    )
    (comp (ref "H4")
      (value "PH-00013")
      (footprint "easyedapro:HDR-TH_2P-P2.54-V-M-R2-C1-S2.54")
      (fields (field (name "Manufacturer") "Liansheng(连盛)"))
      (libsource (lib "easyedapro") (part "PH-00013"))
    )
    (comp (ref "H5")
      (value "PH-00013")
      (footprint "easyedapro:HDR-TH_2P-P2.54-V-M-R2-C1-S2.54")
      (fields (field (name "Manufacturer") "Liansheng(连盛)"))
      (libsource (lib "easyedapro") (part "PH-00013"))
    )
    (comp (ref "H6")
      (value "PH-00013")
      (footprint "easyedapro:HDR-TH_2P-P2.54-V-M-R2-C1-S2.54")
      (fields (field (name "Manufacturer") "Liansheng(连盛)"))
      (libsource (lib "easyedapro") (part "PH-00013"))
    )
    (comp (ref "H7")
      (value "PH-00013")
      (footprint "easyedapro:HDR-TH_2P-P2.54-V-M-R2-C1-S2.54")
      (fields (field (name "Manufacturer") "Liansheng(连盛)"))
      (libsource (lib "easyedapro") (part "PH-00013"))
    )
    (comp (ref "H8")
      (value "PH-00013")
      (footprint "easyedapro:HDR-TH_2P-P2.54-V-M-R2-C1-S2.54")
      (fields (field (name "Manufacturer") "Liansheng(连盛)"))
      (libsource (lib "easyedapro") (part "PH-00013"))
    )
    (comp (ref "H9")
      (value "PH-00013")
      (footprint "easyedapro:HDR-TH_2P-P2.54-V-M-R2-C1-S2.54")
      (fields (field (name "Manufacturer") "Liansheng(连盛)"))
      (libsource (lib "easyedapro") (part "PH-00013"))
    )
    (comp (ref "H10")
      (value "PH-00013")
      (footprint "easyedapro:HDR-TH_2P-P2.54-V-M-R2-C1-S2.54")
      (fields (field (name "Manufacturer") "Liansheng(连盛)"))
      (libsource (lib "easyedapro") (part "PH-00013"))
    )
    (comp (ref "H11")
      (value "PH-00013")
      (footprint "easyedapro:HDR-TH_2P-P2.54-V-M-R2-C1-S2.54")
      (fields (field (name "Manufacturer") "Liansheng(连盛)"))
      (libsource (lib "easyedapro") (part "PH-00013"))
    )
    (comp (ref "H12")
      (value "PH-00013")
      (footprint "easyedapro:HDR-TH_2P-P2.54-V-M-R2-C1-S2.54")
      (fields (field (name "Manufacturer") "Liansheng(连盛)"))
      (libsource (lib "easyedapro") (part "PH-00013"))
    )
    (comp (ref "H13")
      (value "PH-00013")
      (footprint "easyedapro:HDR-TH_2P-P2.54-V-M-R2-C1-S2.54")
      (fields (field (name "Manufacturer") "Liansheng(连盛)"))
      (libsource (lib "easyedapro") (part "PH-00013"))
    )
    (comp (ref "H14")
      (value "PH-00013")
      (footprint "easyedapro:HDR-TH_2P-P2.54-V-M-R2-C1-S2.54")
      (fields (field (name "Manufacturer") "Liansheng(连盛)"))
      (libsource (lib "easyedapro") (part "PH-00013"))
    )
    (comp (ref "H15")
      (value "PH-00013")
      (footprint "easyedapro:HDR-TH_2P-P2.54-V-M-R2-C1-S2.54")
      (fields (field (name "Manufacturer") "Liansheng(连盛)"))
      (libsource (lib "easyedapro") (part "PH-00013"))
    )
    (comp (ref "H16")
      (value "PH-00013")
      (footprint "easyedapro:HDR-TH_2P-P2.54-V-M-R2-C1-S2.54")
      (fields (field (name "Manufacturer") "Liansheng(连盛)"))
      (libsource (lib "easyedapro") (part "PH-00013"))
    )
    (comp (ref "H17")
      (value "PH-00013")
      (footprint "easyedapro:HDR-TH_2P-P2.54-V-M-R2-C1-S2.54")
      (fields (field (name "Manufacturer") "Liansheng(连盛)"))
      (libsource (lib "easyedapro") (part "PH-00013"))
    )
    (comp (ref "LED1")
      (value "19-219/GHC-YR2T1B5Y/3T")
      (footprint "easyedapro:LED-SMD_L1.6-W0.8_19-219-GHC-YR2T1B5Y-3T")
      (fields (field (name "Manufacturer") "EVERLIGHT(亿光)"))
      (libsource (lib "easyedapro") (part "19-219/GHC-YR2T1B5Y/3T"))
    )
    (comp (ref "LED2")
      (value "19-219/GHC-YR2T1B5Y/3T")
      (footprint "easyedapro:LED-SMD_L1.6-W0.8_19-219-GHC-YR2T1B5Y-3T")
      (fields (field (name "Manufacturer") "EVERLIGHT(亿光)"))
      (libsource (lib "easyedapro") (part "19-219/GHC-YR2T1B5Y/3T"))
    )
    (comp (ref "LED3")
      (value "19-219/GHC-YR2T1B5Y/3T")
      (footprint "easyedapro:LED-SMD_L1.6-W0.8_19-219-GHC-YR2T1B5Y-3T")
      (fields (field (name "Manufacturer") "EVERLIGHT(亿光)"))
      (libsource (lib "easyedapro") (part "19-219/GHC-YR2T1B5Y/3T"))
    )
    (comp (ref "LED4")
      (value "19-219/GHC-YR2T1B5Y/3T")
      (footprint "easyedapro:LED-SMD_L1.6-W0.8_19-219-GHC-YR2T1B5Y-3T")
      (fields (field (name "Manufacturer") "EVERLIGHT(亿光)"))
      (libsource (lib "easyedapro") (part "19-219/GHC-YR2T1B5Y/3T"))
    )
    (comp (ref "LED5")
      (value "19-219/GHC-YR2T1B5Y/3T")
      (footprint "easyedapro:LED-SMD_L1.6-W0.8_19-219-GHC-YR2T1B5Y-3T")
      (fields (field (name "Manufacturer") "EVERLIGHT(亿光)"))
      (libsource (lib "easyedapro") (part "19-219/GHC-YR2T1B5Y/3T"))
    )
    (comp (ref "LED6")
      (value "19-219/GHC-YR2T1B5Y/3T")
      (footprint "easyedapro:LED-SMD_L1.6-W0.8_19-219-GHC-YR2T1B5Y-3T")
      (fields (field (name "Manufacturer") "EVERLIGHT(亿光)"))
      (libsource (lib "easyedapro") (part "19-219/GHC-YR2T1B5Y/3T"))
    )
    (comp (ref "LED7")
      (value "19-219/GHC-YR2T1B5Y/3T")
      (footprint "easyedapro:LED-SMD_L1.6-W0.8_19-219-GHC-YR2T1B5Y-3T")
      (fields (field (name "Manufacturer") "EVERLIGHT(亿光)"))
      (libsource (lib "easyedapro") (part "19-219/GHC-YR2T1B5Y/3T"))
    )
    (comp (ref "LED8")
      (value "19-219/GHC-YR2T1B5Y/3T")
      (footprint "easyedapro:LED-SMD_L1.6-W0.8_19-219-GHC-YR2T1B5Y-3T")
      (fields (field (name "Manufacturer") "EVERLIGHT(亿光)"))
      (libsource (lib "easyedapro") (part "19-219/GHC-YR2T1B5Y/3T"))
    )
    (comp (ref "LED9")
      (value "19-219/GHC-YR2T1B5Y/3T")
      (footprint "easyedapro:LED-SMD_L1.6-W0.8_19-219-GHC-YR2T1B5Y-3T")
      (fields (field (name "Manufacturer") "EVERLIGHT(亿光)"))
      (libsource (lib "easyedapro") (part "19-219/GHC-YR2T1B5Y/3T"))
    )
    (comp (ref "LED10")
      (value "19-219/GHC-YR2T1B5Y/3T")
      (footprint "easyedapro:LED-SMD_L1.6-W0.8_19-219-GHC-YR2T1B5Y-3T")
      (fields (field (name "Manufacturer") "EVERLIGHT(亿光)"))
      (libsource (lib "easyedapro") (part "19-219/GHC-YR2T1B5Y/3T"))
    )
    (comp (ref "LED11")
      (value "19-219/GHC-YR2T1B5Y/3T")
      (footprint "easyedapro:LED-SMD_L1.6-W0.8_19-219-GHC-YR2T1B5Y-3T")
      (fields (field (name "Manufacturer") "EVERLIGHT(亿光)"))
      (libsource (lib "easyedapro") (part "19-219/GHC-YR2T1B5Y/3T"))
    )
    (comp (ref "LED12")
      (value "19-219/GHC-YR2T1B5Y/3T")
      (footprint "easyedapro:LED-SMD_L1.6-W0.8_19-219-GHC-YR2T1B5Y-3T")
      (fields (field (name "Manufacturer") "EVERLIGHT(亿光)"))
      (libsource (lib "easyedapro") (part "19-219/GHC-YR2T1B5Y/3T"))
    )
    (comp (ref "LED13")
      (value "19-219/GHC-YR2T1B5Y/3T")
      (footprint "easyedapro:LED-SMD_L1.6-W0.8_19-219-GHC-YR2T1B5Y-3T")
      (fields (field (name "Manufacturer") "EVERLIGHT(亿光)"))
      (libsource (lib "easyedapro") (part "19-219/GHC-YR2T1B5Y/3T"))
    )
    (comp (ref "LED14")
      (value "19-219/GHC-YR2T1B5Y/3T")
      (footprint "easyedapro:LED-SMD_L1.6-W0.8_19-219-GHC-YR2T1B5Y-3T")
      (fields (field (name "Manufacturer") "EVERLIGHT(亿光)"))
      (libsource (lib "easyedapro") (part "19-219/GHC-YR2T1B5Y/3T"))
    )
    (comp (ref "LED15")
      (value "19-219/GHC-YR2T1B5Y/3T")
      (footprint "easyedapro:LED-SMD_L1.6-W0.8_19-219-GHC-YR2T1B5Y-3T")
      (fields (field (name "Manufacturer") "EVERLIGHT(亿光)"))
      (libsource (lib "easyedapro") (part "19-219/GHC-YR2T1B5Y/3T"))
    )
    (comp (ref "LED16")
      (value "19-219/GHC-YR2T1B5Y/3T")
      (footprint "easyedapro:LED-SMD_L1.6-W0.8_19-219-GHC-YR2T1B5Y-3T")
      (fields (field (name "Manufacturer") "EVERLIGHT(亿光)"))
      (libsource (lib "easyedapro") (part "19-219/GHC-YR2T1B5Y/3T"))
    )
    (comp (ref "PWM-A0")
      (value "PZ254V-11-03P")
      (footprint "easyedapro:HDR-TH_3P-P2.54-V-M")
      (fields (field (name "Manufacturer") "XFCN(兴飞)"))
      (libsource (lib "easyedapro") (part "PZ254V-11-03P_C2937625"))
    )
    (comp (ref "PWM-A1")
      (value "PZ254V-11-03P")
      (footprint "easyedapro:HDR-TH_3P-P2.54-V-M")
      (fields (field (name "Manufacturer") "XFCN(兴飞)"))
      (libsource (lib "easyedapro") (part "PZ254V-11-03P_C2937625"))
    )
    (comp (ref "PWM-A2")
      (value "PZ254V-11-03P")
      (footprint "easyedapro:HDR-TH_3P-P2.54-V-M")
      (fields (field (name "Manufacturer") "XFCN(兴飞)"))
      (libsource (lib "easyedapro") (part "PZ254V-11-03P_C2937625"))
    )
    (comp (ref "PWM-A3")
      (value "PZ254V-11-03P")
      (footprint "easyedapro:HDR-TH_3P-P2.54-V-M")
      (fields (field (name "Manufacturer") "XFCN(兴飞)"))
      (libsource (lib "easyedapro") (part "PZ254V-11-03P_C2937625"))
    )
    (comp (ref "PWM-A4")
      (value "PZ254V-11-03P")
      (footprint "easyedapro:HDR-TH_3P-P2.54-V-M")
      (fields (field (name "Manufacturer") "XFCN(兴飞)"))
      (libsource (lib "easyedapro") (part "PZ254V-11-03P_C2937625"))
    )
    (comp (ref "PWM-A5")
      (value "PZ254V-11-03P")
      (footprint "easyedapro:HDR-TH_3P-P2.54-V-M")
      (fields (field (name "Manufacturer") "XFCN(兴飞)"))
      (libsource (lib "easyedapro") (part "PZ254V-11-03P_C2937625"))
    )
    (comp (ref "U18")
      (value "PCA9685PW,118")
      (footprint "easyedapro:TSSOP-28_L9.7-W4.4-P0.65-LS6.4-TL")
      (fields (field (name "Manufacturer") "NXP(恩智浦)"))
      (libsource (lib "easyedapro") (part "PCA9685PW,118"))
    )
    (comp (ref "U19")
      (value "BX-PZ2.54-2-3PZZ")
      (footprint "easyedapro:HDR-TH_6P-P2.54-V-M-R2-C3-S2.54")
      (fields (field (name "Manufacturer") "Bossie(博锡)"))
      (libsource (lib "easyedapro") (part "BX-PZ2.54-2-3PZZ"))
    )
    (comp (ref "U20")
      (value "BX-PZ2.54-2-3PZZ")
      (footprint "easyedapro:HDR-TH_6P-P2.54-V-M-R2-C3-S2.54")
      (fields (field (name "Manufacturer") "Bossie(博锡)"))
      (libsource (lib "easyedapro") (part "BX-PZ2.54-2-3PZZ"))
    )
    (comp (ref "U21")
      (value "BX-PZ2.54-2-3PZZ")
      (footprint "easyedapro:HDR-TH_6P-P2.54-V-M-R2-C3-S2.54")
      (fields (field (name "Manufacturer") "Bossie(博锡)"))
      (libsource (lib "easyedapro") (part "BX-PZ2.54-2-3PZZ"))
    )
    (comp (ref "U22")
      (value "BX-PZ2.54-2-3PZZ")
      (footprint "easyedapro:HDR-TH_6P-P2.54-V-M-R2-C3-S2.54")
      (fields (field (name "Manufacturer") "Bossie(博锡)"))
      (libsource (lib "easyedapro") (part "BX-PZ2.54-2-3PZZ"))
    )
    (comp (ref "U23")
      (value "BX-PZ2.54-2-3PZZ")
      (footprint "easyedapro:HDR-TH_6P-P2.54-V-M-R2-C3-S2.54")
      (fields (field (name "Manufacturer") "Bossie(博锡)"))
      (libsource (lib "easyedapro") (part "BX-PZ2.54-2-3PZZ"))
    )
    (comp (ref "U24")
      (value "BX-PZ2.54-2-3PZZ")
      (footprint "easyedapro:HDR-TH_6P-P2.54-V-M-R2-C3-S2.54")
      (fields (field (name "Manufacturer") "Bossie(博锡)"))
      (libsource (lib "easyedapro") (part "BX-PZ2.54-2-3PZZ"))
    )
    (comp (ref "U25")
      (value "BX-PZ2.54-2-3PZZ")
      (footprint "easyedapro:HDR-TH_6P-P2.54-V-M-R2-C3-S2.54")
      (fields (field (name "Manufacturer") "Bossie(博锡)"))
      (libsource (lib "easyedapro") (part "BX-PZ2.54-2-3PZZ"))
    )
    (comp (ref "U26")
      (value "BX-PZ2.54-2-3PZZ")
      (footprint "easyedapro:HDR-TH_6P-P2.54-V-M-R2-C3-S2.54")
      (fields (field (name "Manufacturer") "Bossie(博锡)"))
      (libsource (lib "easyedapro") (part "BX-PZ2.54-2-3PZZ"))
    )
    (comp (ref "U27")
      (value "BX-PZ2.54-2-3PZZ")
      (footprint "easyedapro:HDR-TH_6P-P2.54-V-M-R2-C3-S2.54")
      (fields (field (name "Manufacturer") "Bossie(博锡)"))
      (libsource (lib "easyedapro") (part "BX-PZ2.54-2-3PZZ"))
    )
    (comp (ref "U28")
      (value "BX-PZ2.54-2-3PZZ")
      (footprint "easyedapro:HDR-TH_6P-P2.54-V-M-R2-C3-S2.54")
      (fields (field (name "Manufacturer") "Bossie(博锡)"))
      (libsource (lib "easyedapro") (part "BX-PZ2.54-2-3PZZ"))
    )
    (comp (ref "U29")
      (value "BX-PZ2.54-2-3PZZ")
      (footprint "easyedapro:HDR-TH_6P-P2.54-V-M-R2-C3-S2.54")
      (fields (field (name "Manufacturer") "Bossie(博锡)"))
      (libsource (lib "easyedapro") (part "BX-PZ2.54-2-3PZZ"))
    )
    (comp (ref "U30")
      (value "BX-PZ2.54-2-3PZZ")
      (footprint "easyedapro:HDR-TH_6P-P2.54-V-M-R2-C3-S2.54")
      (fields (field (name "Manufacturer") "Bossie(博锡)"))
      (libsource (lib "easyedapro") (part "BX-PZ2.54-2-3PZZ"))
    )
    (comp (ref "U31")
      (value "BX-PZ2.54-2-3PZZ")
      (footprint "easyedapro:HDR-TH_6P-P2.54-V-M-R2-C3-S2.54")
      (fields (field (name "Manufacturer") "Bossie(博锡)"))
      (libsource (lib "easyedapro") (part "BX-PZ2.54-2-3PZZ"))
    )
    (comp (ref "U32")
      (value "BX-PZ2.54-2-3PZZ")
      (footprint "easyedapro:HDR-TH_6P-P2.54-V-M-R2-C3-S2.54")
      (fields (field (name "Manufacturer") "Bossie(博锡)"))
      (libsource (lib "easyedapro") (part "BX-PZ2.54-2-3PZZ"))
    )
    (comp (ref "U33")
      (value "BX-PZ2.54-2-3PZZ")
      (footprint "easyedapro:HDR-TH_6P-P2.54-V-M-R2-C3-S2.54")
      (fields (field (name "Manufacturer") "Bossie(博锡)"))
      (libsource (lib "easyedapro") (part "BX-PZ2.54-2-3PZZ"))
    )
    (comp (ref "U34")
      (value "BX-PZ2.54-2-3PZZ")
      (footprint "easyedapro:HDR-TH_6P-P2.54-V-M-R2-C3-S2.54")
      (fields (field (name "Manufacturer") "Bossie(博锡)"))
      (libsource (lib "easyedapro") (part "BX-PZ2.54-2-3PZZ"))
    )
    (comp (ref "I2C0")
      (value "ZX-XH2.54-4PZZ")
      (footprint "easyedapro:CONN-TH_4P-P2.50_4PIN")
      (fields (field (name "Manufacturer") "Megastar(兆星)"))
      (libsource (lib "easyedapro") (part "ZX-XH2.54-4PZZ"))
    )
    (comp (ref "I2C1")
      (value "ZX-XH2.54-4PZZ")
      (footprint "easyedapro:CONN-TH_4P-P2.50_4PIN")
      (fields (field (name "Manufacturer") "Megastar(兆星)"))
      (libsource (lib "easyedapro") (part "ZX-XH2.54-4PZZ"))
    )
    (comp (ref "I2C1-A0")
      (value "PZ254V-11-03P")
      (footprint "easyedapro:HDR-TH_3P-P2.54-V-M")
      (fields (field (name "Manufacturer") "XFCN(兴飞)"))
      (libsource (lib "easyedapro") (part "PZ254V-11-03P_C2937625"))
    )
    (comp (ref "I2C1-A1")
      (value "PZ254V-11-03P")
      (footprint "easyedapro:HDR-TH_3P-P2.54-V-M")
      (fields (field (name "Manufacturer") "XFCN(兴飞)"))
      (libsource (lib "easyedapro") (part "PZ254V-11-03P_C2937625"))
    )
    (comp (ref "I2C1-A2")
      (value "PZ254V-11-03P")
      (footprint "easyedapro:HDR-TH_3P-P2.54-V-M")
      (fields (field (name "Manufacturer") "XFCN(兴飞)"))
      (libsource (lib "easyedapro") (part "PZ254V-11-03P_C2937625"))
    )
    (comp (ref "I2C1-PWR1")
      (value "PZ254V-11-03P")
      (footprint "easyedapro:HDR-TH_3P-P2.54-V-M")
      (fields (field (name "Manufacturer") "XFCN(兴飞)"))
      (libsource (lib "easyedapro") (part "PZ254V-11-03P_C2937625"))
    )
    (comp (ref "I2C2")
      (value "ZX-XH2.54-4PZZ")
      (footprint "easyedapro:CONN-TH_4P-P2.50_4PIN")
      (fields (field (name "Manufacturer") "Megastar(兆星)"))
      (libsource (lib "easyedapro") (part "ZX-XH2.54-4PZZ"))
    )
    (comp (ref "I2C3")
      (value "ZX-XH2.54-4PZZ")
      (footprint "easyedapro:CONN-TH_4P-P2.50_4PIN")
      (fields (field (name "Manufacturer") "Megastar(兆星)"))
      (libsource (lib "easyedapro") (part "ZX-XH2.54-4PZZ"))
    )
    (comp (ref "I2C4")
      (value "ZX-XH2.54-4PZZ")
      (footprint "easyedapro:CONN-TH_4P-P2.50_4PIN")
      (fields (field (name "Manufacturer") "Megastar(兆星)"))
      (libsource (lib "easyedapro") (part "ZX-XH2.54-4PZZ"))
    )
    (comp (ref "I2C5")
      (value "ZX-XH2.54-4PZZ")
      (footprint "easyedapro:CONN-TH_4P-P2.50_4PIN")
      (fields (field (name "Manufacturer") "Megastar(兆星)"))
      (libsource (lib "easyedapro") (part "ZX-XH2.54-4PZZ"))
    )
    (comp (ref "I2C6")
      (value "ZX-XH2.54-4PZZ")
      (footprint "easyedapro:CONN-TH_4P-P2.50_4PIN")
      (fields (field (name "Manufacturer") "Megastar(兆星)"))
      (libsource (lib "easyedapro") (part "ZX-XH2.54-4PZZ"))
    )
    (comp (ref "I2C7")
      (value "ZX-XH2.54-4PZZ")
      (footprint "easyedapro:CONN-TH_4P-P2.50_4PIN")
      (fields (field (name "Manufacturer") "Megastar(兆星)"))
      (libsource (lib "easyedapro") (part "ZX-XH2.54-4PZZ"))
    )
    (comp (ref "R1")
      (value "3kΩ")
      (footprint "easyedapro:R0603")
      (fields
        (field (name "Manufacturer Part") "0603WAF3001T5E")
        (field (name "Manufacturer") "UNI-ROYAL(厚声)")
      )
      (libsource (lib "easyedapro") (part "0603WAF3001T5E"))
    )
    (comp (ref "R2")
      (value "3kΩ")
      (footprint "easyedapro:R0603")
      (fields
        (field (name "Manufacturer Part") "0603WAF3001T5E")
        (field (name "Manufacturer") "UNI-ROYAL(厚声)")
      )
      (libsource (lib "easyedapro") (part "0603WAF3001T5E"))
    )
    (comp (ref "R3")
      (value "3kΩ")
      (footprint "easyedapro:R0603")
      (fields
        (field (name "Manufacturer Part") "0603WAF3001T5E")
        (field (name "Manufacturer") "UNI-ROYAL(厚声)")
      )
      (libsource (lib "easyedapro") (part "0603WAF3001T5E"))
    )
    (comp (ref "R4")
      (value "3kΩ")
      (footprint "easyedapro:R0603")
      (fields
        (field (name "Manufacturer Part") "0603WAF3001T5E")
        (field (name "Manufacturer") "UNI-ROYAL(厚声)")
      )
      (libsource (lib "easyedapro") (part "0603WAF3001T5E"))
    )
    (comp (ref "R5")
      (value "3kΩ")
      (footprint "easyedapro:R0603")
      (fields
        (field (name "Manufacturer Part") "0603WAF3001T5E")
        (field (name "Manufacturer") "UNI-ROYAL(厚声)")
      )
      (libsource (lib "easyedapro") (part "0603WAF3001T5E"))
    )
    (comp (ref "R6")
      (value "3kΩ")
      (footprint "easyedapro:R0603")
      (fields
        (field (name "Manufacturer Part") "0603WAF3001T5E")
        (field (name "Manufacturer") "UNI-ROYAL(厚声)")
      )
      (libsource (lib "easyedapro") (part "0603WAF3001T5E"))
    )
    (comp (ref "R7")
      (value "3kΩ")
      (footprint "easyedapro:R0603")
      (fields
        (field (name "Manufacturer Part") "0603WAF3001T5E")
        (field (name "Manufacturer") "UNI-ROYAL(厚声)")
      )
      (libsource (lib "easyedapro") (part "0603WAF3001T5E"))
    )
    (comp (ref "R8")
      (value "3kΩ")
      (footprint "easyedapro:R0603")
      (fields
        (field (name "Manufacturer Part") "0603WAF3001T5E")
        (field (name "Manufacturer") "UNI-ROYAL(厚声)")
      )
      (libsource (lib "easyedapro") (part "0603WAF3001T5E"))
    )
    (comp (ref "R9")
      (value "3kΩ")
      (footprint "easyedapro:R0603")
      (fields
        (field (name "Manufacturer Part") "0603WAF3001T5E")
        (field (name "Manufacturer") "UNI-ROYAL(厚声)")
      )
      (libsource (lib "easyedapro") (part "0603WAF3001T5E"))
    )
    (comp (ref "R10")
      (value "3kΩ")
      (footprint "easyedapro:R0603")
      (fields
        (field (name "Manufacturer Part") "0603WAF3001T5E")
        (field (name "Manufacturer") "UNI-ROYAL(厚声)")
      )
      (libsource (lib "easyedapro") (part "0603WAF3001T5E"))
    )
    (comp (ref "R11")
      (value "3kΩ")
      (footprint "easyedapro:R0603")
      (fields
        (field (name "Manufacturer Part") "0603WAF3001T5E")
        (field (name "Manufacturer") "UNI-ROYAL(厚声)")
      )
      (libsource (lib "easyedapro") (part "0603WAF3001T5E"))
    )
    (comp (ref "R12")
      (value "3kΩ")
      (footprint "easyedapro:R0603")
      (fields
        (field (name "Manufacturer Part") "0603WAF3001T5E")
        (field (name "Manufacturer") "UNI-ROYAL(厚声)")
      )
      (libsource (lib "easyedapro") (part "0603WAF3001T5E"))
    )
    (comp (ref "R13")
      (value "3kΩ")
      (footprint "easyedapro:R0603")
      (fields
        (field (name "Manufacturer Part") "0603WAF3001T5E")
        (field (name "Manufacturer") "UNI-ROYAL(厚声)")
      )
      (libsource (lib "easyedapro") (part "0603WAF3001T5E"))
    )
    (comp (ref "R14")
      (value "3kΩ")
      (footprint "easyedapro:R0603")
      (fields
        (field (name "Manufacturer Part") "0603WAF3001T5E")
        (field (name "Manufacturer") "UNI-ROYAL(厚声)")
      )
      (libsource (lib "easyedapro") (part "0603WAF3001T5E"))
    )
    (comp (ref "R15")
      (value "3kΩ")
      (footprint "easyedapro:R0603")
      (fields
        (field (name "Manufacturer Part") "0603WAF3001T5E")
        (field (name "Manufacturer") "UNI-ROYAL(厚声)")
      )
      (libsource (lib "easyedapro") (part "0603WAF3001T5E"))
    )
    (comp (ref "R16")
      (value "3kΩ")
      (footprint "easyedapro:R0603")
      (fields
        (field (name "Manufacturer Part") "0603WAF3001T5E")
        (field (name "Manufacturer") "UNI-ROYAL(厚声)")
      )
      (libsource (lib "easyedapro") (part "0603WAF3001T5E"))
    )
    (comp (ref "R17")
      (value "3kΩ")
      (footprint "easyedapro:R0603")
      (fields
        (field (name "Manufacturer Part") "0603WAF3001T5E")
        (field (name "Manufacturer") "UNI-ROYAL(厚声)")
      )
      (libsource (lib "easyedapro") (part "0603WAF3001T5E"))
    )
    (comp (ref "R18")
      (value "3kΩ")
      (footprint "easyedapro:R0603")
      (fields
        (field (name "Manufacturer Part") "0603WAF3001T5E")
        (field (name "Manufacturer") "UNI-ROYAL(厚声)")
      )
      (libsource (lib "easyedapro") (part "0603WAF3001T5E"))
    )
    (comp (ref "U2")
      (value "TCA9548APWR")
      (footprint "easyedapro:TSSOP-24_L7.8-W4.4-P0.65-LS6.4-BL")
      (fields (field (name "Manufacturer") "TI(德州仪器)"))
      (libsource (lib "easyedapro") (part "TCA9548APWR"))
    )
    (comp (ref "GPIO1")
      (value "PZ254V-11-04P")
      (footprint "easyedapro:HDR-TH_4P-P2.54-V-M")
      (fields (field (name "Manufacturer") "XFCN(兴飞)"))
      (libsource (lib "easyedapro") (part "PZ254V-11-04P_C2691448"))
    )
    (comp (ref "GPIO2")
      (value "PZ254V-11-04P")
      (footprint "easyedapro:HDR-TH_4P-P2.54-V-M")
      (fields (field (name "Manufacturer") "XFCN(兴飞)"))
      (libsource (lib "easyedapro") (part "PZ254V-11-04P_C2691448"))
    )
    (comp (ref "I2CX-A0")
      (value "PZ254V-11-03P")
      (footprint "easyedapro:HDR-TH_3P-P2.54-V-M")
      (fields (field (name "Manufacturer") "XFCN(兴飞)"))
      (libsource (lib "easyedapro") (part "PZ254V-11-03P_C2937625"))
    )
    (comp (ref "I2CX-A1")
      (value "PZ254V-11-03P")
      (footprint "easyedapro:HDR-TH_3P-P2.54-V-M")
      (fields (field (name "Manufacturer") "XFCN(兴飞)"))
      (libsource (lib "easyedapro") (part "PZ254V-11-03P_C2937625"))
    )
    (comp (ref "I2CX-A2")
      (value "PZ254V-11-03P")
      (footprint "easyedapro:HDR-TH_3P-P2.54-V-M")
      (fields (field (name "Manufacturer") "XFCN(兴飞)"))
      (libsource (lib "easyedapro") (part "PZ254V-11-03P_C2937625"))
    )
    (comp (ref "R51")
      (value "3kΩ")
      (footprint "easyedapro:R0603")
      (fields
        (field (name "Manufacturer Part") "0603WAF3001T5E")
        (field (name "Manufacturer") "UNI-ROYAL(厚声)")
      )
      (libsource (lib "easyedapro") (part "0603WAF3001T5E"))
    )
    (comp (ref "RN1")
      (value "10kΩ")
      (footprint "easyedapro:RES-ARRAY-SMD_0603-8P-L3.2-W1.6-BL")
      (fields
        (field (name "Manufacturer Part") "4D03WGJ0103T5E")
        (field (name "Manufacturer") "UNI-ROYAL(厚声)")
      )
      (libsource (lib "easyedapro") (part "4D03WGJ0103T5E"))
    )
    (comp (ref "RN2")
      (value "10kΩ")
      (footprint "easyedapro:RES-ARRAY-SMD_0603-8P-L3.2-W1.6-BL")
      (fields
        (field (name "Manufacturer Part") "4D03WGJ0103T5E")
        (field (name "Manufacturer") "UNI-ROYAL(厚声)")
      )
      (libsource (lib "easyedapro") (part "4D03WGJ0103T5E"))
    )
    (comp (ref "RN3")
      (value "10kΩ")
      (footprint "easyedapro:RES-ARRAY-SMD_0603-8P-L3.2-W1.6-BL")
      (fields
        (field (name "Manufacturer Part") "4D03WGJ0103T5E")
        (field (name "Manufacturer") "UNI-ROYAL(厚声)")
      )
      (libsource (lib "easyedapro") (part "4D03WGJ0103T5E"))
    )
    (comp (ref "RN4")
      (value "10kΩ")
      (footprint "easyedapro:RES-ARRAY-SMD_0603-8P-L3.2-W1.6-BL")
      (fields
        (field (name "Manufacturer Part") "4D03WGJ0103T5E")
        (field (name "Manufacturer") "UNI-ROYAL(厚声)")
      )
      (libsource (lib "easyedapro") (part "4D03WGJ0103T5E"))
    )
    (comp (ref "U17")
      (value "TCA9535PWR")
      (footprint "easyedapro:TSSOP-24_L7.8-W4.4-P0.65-LS6.4-BL")
      (fields (field (name "Manufacturer") "TI(德州仪器)"))
      (libsource (lib "easyedapro") (part "TCA9535PWR_C130204"))
    )
    (comp (ref "CN10")
      (value "ZX-XH2.54-4PZZ")
      (footprint "easyedapro:CONN-TH_4P-P2.50_4PIN")
      (fields (field (name "Manufacturer") "Megastar(兆星)"))
      (libsource (lib "easyedapro") (part "ZX-XH2.54-4PZZ"))
    )
    (comp (ref "CN11")
      (value "ZX-XH2.54-4PZZ")
      (footprint "easyedapro:CONN-TH_4P-P2.50_4PIN")
      (fields (field (name "Manufacturer") "Megastar(兆星)"))
      (libsource (lib "easyedapro") (part "ZX-XH2.54-4PZZ"))
    )
    (comp (ref "CN12")
      (value "ZX-XH2.54-4PZZ")
      (footprint "easyedapro:CONN-TH_4P-P2.50_4PIN")
      (fields (field (name "Manufacturer") "Megastar(兆星)"))
      (libsource (lib "easyedapro") (part "ZX-XH2.54-4PZZ"))
    )
    (comp (ref "U4")
      (value "ZX-XH2.54-6PZZ")
      (footprint "easyedapro:CONN-TH_6P-P2.50_ZX-XH2.54-6PZZ")
      (fields (field (name "Manufacturer") "Megastar(兆星)"))
      (libsource (lib "easyedapro") (part "ZX-XH2.54-6PZZ"))
    )
    (comp (ref "U5")
      (value "ZX-XH2.54-5PZZ")
      (footprint "easyedapro:CONN-TH_5P-P2.50_ZX-XH2.54-5PZZ")
      (fields (field (name "Manufacturer") "Megastar(兆星)"))
      (libsource (lib "easyedapro") (part "ZX-XH2.54-5PZZ"))
    )
    (comp (ref "U6")
      (value "ZX-XH2.54-5PZZ")
      (footprint "easyedapro:CONN-TH_5P-P2.50_ZX-XH2.54-5PZZ")
      (fields (field (name "Manufacturer") "Megastar(兆星)"))
      (libsource (lib "easyedapro") (part "ZX-XH2.54-5PZZ"))
    )
    (comp (ref "U8")
      (value "ZX-XH2.54-6PZZ")
      (footprint "easyedapro:CONN-TH_6P-P2.50_ZX-XH2.54-6PZZ")
      (fields (field (name "Manufacturer") "Megastar(兆星)"))
      (libsource (lib "easyedapro") (part "ZX-XH2.54-6PZZ"))
    )
    (comp (ref "U40")
      (value "ZX-XH2.54-6PZZ")
      (footprint "easyedapro:CONN-TH_6P-P2.50_ZX-XH2.54-6PZZ")
      (fields (field (name "Manufacturer") "Megastar(兆星)"))
      (libsource (lib "easyedapro") (part "ZX-XH2.54-6PZZ"))
    )
    (comp (ref "U41")
      (value "ZX-XH2.54-6PZZ")
      (footprint "easyedapro:CONN-TH_6P-P2.50_ZX-XH2.54-6PZZ")
      (fields (field (name "Manufacturer") "Megastar(兆星)"))
      (libsource (lib "easyedapro") (part "ZX-XH2.54-6PZZ"))
    )
    (comp (ref "U42")
      (value "ZX-XH2.54-5PZZ")
      (footprint "easyedapro:CONN-TH_5P-P2.50_ZX-XH2.54-5PZZ")
      (fields (field (name "Manufacturer") "Megastar(兆星)"))
      (libsource (lib "easyedapro") (part "ZX-XH2.54-5PZZ"))
    )
    (comp (ref "CN56")
      (value "ZX-XH2.54-3PZZ")
      (footprint "easyedapro:CONN-TH_3P-P2.54_2501S-3P")
      (fields (field (name "Manufacturer") "Megastar(兆星)"))
      (libsource (lib "easyedapro") (part "ZX-XH2.54-3PZZ"))
    )
    (comp (ref "CN57")
      (value "ZX-XH2.54-3PZZ")
      (footprint "easyedapro:CONN-TH_3P-P2.54_2501S-3P")
      (fields (field (name "Manufacturer") "Megastar(兆星)"))
      (libsource (lib "easyedapro") (part "ZX-XH2.54-3PZZ"))
    )
    (comp (ref "CN58")
      (value "ZX-XH2.54-3PZZ")
      (footprint "easyedapro:CONN-TH_3P-P2.54_2501S-3P")
      (fields (field (name "Manufacturer") "Megastar(兆星)"))
      (libsource (lib "easyedapro") (part "ZX-XH2.54-3PZZ"))
    )
    (comp (ref "CN59")
      (value "ZX-XH2.54-3PZZ")
      (footprint "easyedapro:CONN-TH_3P-P2.54_2501S-3P")
      (fields (field (name "Manufacturer") "Megastar(兆星)"))
      (libsource (lib "easyedapro") (part "ZX-XH2.54-3PZZ"))
    )
    (comp (ref "CN60")
      (value "ZX-XH2.54-3PZZ")
      (footprint "easyedapro:CONN-TH_3P-P2.54_2501S-3P")
      (fields (field (name "Manufacturer") "Megastar(兆星)"))
      (libsource (lib "easyedapro") (part "ZX-XH2.54-3PZZ"))
    )
    (comp (ref "CN61")
      (value "ZX-XH2.54-3PZZ")
      (footprint "easyedapro:CONN-TH_3P-P2.54_2501S-3P")
      (fields (field (name "Manufacturer") "Megastar(兆星)"))
      (libsource (lib "easyedapro") (part "ZX-XH2.54-3PZZ"))
    )
    (comp (ref "CN62")
      (value "ZX-XH2.54-3PZZ")
      (footprint "easyedapro:CONN-TH_3P-P2.54_2501S-3P")
      (fields (field (name "Manufacturer") "Megastar(兆星)"))
      (libsource (lib "easyedapro") (part "ZX-XH2.54-3PZZ"))
    )
    (comp (ref "CN63")
      (value "ZX-XH2.54-3PZZ")
      (footprint "easyedapro:CONN-TH_3P-P2.54_2501S-3P")
      (fields (field (name "Manufacturer") "Megastar(兆星)"))
      (libsource (lib "easyedapro") (part "ZX-XH2.54-3PZZ"))
    )
    (comp (ref "U39")
      (value "CD74HC4051M96")
      (footprint "easyedapro:SOIC-16_L9.9-W3.9-P1.27-LS6.0-BL")
      (fields (field (name "Manufacturer") "TI(德州仪器)"))
      (libsource (lib "easyedapro") (part "CD74HC4051M96"))
    )
    (comp (ref "SONAR0")
      (value "ZX-XH2.54-4PZZ")
      (footprint "easyedapro:CONN-TH_4P-P2.50_4PIN")
      (fields (field (name "Manufacturer") "Megastar(兆星)"))
      (libsource (lib "easyedapro") (part "ZX-XH2.54-4PZZ"))
    )
    (comp (ref "SONAR1")
      (value "ZX-XH2.54-4PZZ")
      (footprint "easyedapro:CONN-TH_4P-P2.50_4PIN")
      (fields (field (name "Manufacturer") "Megastar(兆星)"))
      (libsource (lib "easyedapro") (part "ZX-XH2.54-4PZZ"))
    )
    (comp (ref "SONAR2")
      (value "ZX-XH2.54-4PZZ")
      (footprint "easyedapro:CONN-TH_4P-P2.50_4PIN")
      (fields (field (name "Manufacturer") "Megastar(兆星)"))
      (libsource (lib "easyedapro") (part "ZX-XH2.54-4PZZ"))
    )
    (comp (ref "SONAR3")
      (value "ZX-XH2.54-4PZZ")
      (footprint "easyedapro:CONN-TH_4P-P2.50_4PIN")
      (fields (field (name "Manufacturer") "Megastar(兆星)"))
      (libsource (lib "easyedapro") (part "ZX-XH2.54-4PZZ"))
    )
    (comp (ref "U35")
      (value "TXB0106PWR")
      (footprint "easyedapro:TSSOP-16_L5.0-W4.4-P0.65-LS6.4-BL")
      (fields (field (name "Manufacturer") "TI(德州仪器)"))
      (libsource (lib "easyedapro") (part "TXB0106PWR"))
    )
    (comp (ref "U36")
      (value "TXB0106PWR")
      (footprint "easyedapro:TSSOP-16_L5.0-W4.4-P0.65-LS6.4-BL")
      (fields (field (name "Manufacturer") "TI(德州仪器)"))
      (libsource (lib "easyedapro") (part "TXB0106PWR"))
    )
  )
  (nets
    (net (code "1") (name "3.3V") (class "Default")
      (node (ref "PWM-A0") (pin "1") (pinfunction "1_1") (pintype "unspecified"))
      (node (ref "PWM-A1") (pin "1") (pinfunction "1_1") (pintype "unspecified"))
      (node (ref "PWM-A2") (pin "1") (pinfunction "1_1") (pintype "unspecified"))
      (node (ref "PWM-A3") (pin "1") (pinfunction "1_1") (pintype "unspecified"))
      (node (ref "PWM-A4") (pin "1") (pinfunction "1_1") (pintype "unspecified"))
      (node (ref "PWM-A5") (pin "1") (pinfunction "1_1") (pintype "unspecified"))
      (node (ref "U18") (pin "28") (pinfunction "VDD_28") (pintype "input"))
    )
    (net (code "2") (name "3.3VEXT") (class "Default")
      (node (ref "3.3VEXT1") (pin "2") (pinfunction "2_2") (pintype "input"))
      (node (ref "C1") (pin "1") (pinfunction "1_1") (pintype "input"))
      (node (ref "H19") (pin "1") (pinfunction "1_1") (pintype "unspecified"))
      (node (ref "I2C1-PWR1") (pin "3") (pinfunction "3_3") (pintype "unspecified"))
      (node (ref "U19") (pin "1") (pinfunction "1_1") (pintype "unspecified"))
      (node (ref "U20") (pin "1") (pinfunction "1_1") (pintype "unspecified"))
      (node (ref "U21") (pin "1") (pinfunction "1_1") (pintype "unspecified"))
      (node (ref "U22") (pin "1") (pinfunction "1_1") (pintype "unspecified"))
      (node (ref "U23") (pin "1") (pinfunction "1_1") (pintype "unspecified"))
      (node (ref "U24") (pin "1") (pinfunction "1_1") (pintype "unspecified"))
      (node (ref "U25") (pin "1") (pinfunction "1_1") (pintype "unspecified"))
      (node (ref "U26") (pin "1") (pinfunction "1_1") (pintype "unspecified"))
      (node (ref "U27") (pin "1") (pinfunction "1_1") (pintype "unspecified"))
      (node (ref "U28") (pin "1") (pinfunction "1_1") (pintype "unspecified"))
      (node (ref "U29") (pin "1") (pinfunction "1_1") (pintype "unspecified"))
      (node (ref "U30") (pin "1") (pinfunction "1_1") (pintype "unspecified"))
      (node (ref "U31") (pin "1") (pinfunction "1_1") (pintype "unspecified"))
      (node (ref "U32") (pin "1") (pinfunction "1_1") (pintype "unspecified"))
      (node (ref "U33") (pin "1") (pinfunction "1_1") (pintype "unspecified"))
      (node (ref "U34") (pin "1") (pinfunction "1_1") (pintype "unspecified"))
    )
    (net (code "3") (name "3V3") (class "Default")
      (node (ref "CN10") (pin "1") (pinfunction "1_1") (pintype "unspecified"))
      (node (ref "CN11") (pin "1") (pinfunction "1_1") (pintype "unspecified"))
      (node (ref "CN12") (pin "1") (pinfunction "1_1") (pintype "unspecified"))
      (node (ref "CN56") (pin "2") (pinfunction "2_2") (pintype "unspecified"))
      (node (ref "CN57") (pin "2") (pinfunction "2_2") (pintype "unspecified"))
      (node (ref "CN58") (pin "2") (pinfunction "2_2") (pintype "unspecified"))
      (node (ref "CN59") (pin "2") (pinfunction "2_2") (pintype "unspecified"))
      (node (ref "CN60") (pin "2") (pinfunction "2_2") (pintype "unspecified"))
      (node (ref "CN61") (pin "2") (pinfunction "2_2") (pintype "unspecified"))
      (node (ref "CN62") (pin "2") (pinfunction "2_2") (pintype "unspecified"))
      (node (ref "CN63") (pin "2") (pinfunction "2_2") (pintype "unspecified"))
      (node (ref "H19") (pin "2") (pinfunction "2_2") (pintype "unspecified"))
      (node (ref "I2C1-A0") (pin "1") (pinfunction "1_1") (pintype "unspecified"))
      (node (ref "I2C1-A1") (pin "1") (pinfunction "1_1") (pintype "unspecified"))
      (node (ref "I2C1-A2") (pin "1") (pinfunction "1_1") (pintype "unspecified"))
      (node (ref "I2C1-PWR1") (pin "1") (pinfunction "1_1") (pintype "unspecified"))
      (node (ref "I2CX-A0") (pin "1") (pinfunction "1_1") (pintype "unspecified"))
      (node (ref "I2CX-A1") (pin "1") (pinfunction "1_1") (pintype "unspecified"))
      (node (ref "I2CX-A2") (pin "1") (pinfunction "1_1") (pintype "unspecified"))
      (node (ref "R1") (pin "1") (pinfunction "1_1") (pintype "input"))
      (node (ref "R10") (pin "2") (pinfunction "2_2") (pintype "input"))
      (node (ref "R11") (pin "2") (pinfunction "2_2") (pintype "input"))
      (node (ref "R12") (pin "2") (pinfunction "2_2") (pintype "input"))
      (node (ref "R13") (pin "2") (pinfunction "2_2") (pintype "input"))
      (node (ref "R14") (pin "2") (pinfunction "2_2") (pintype "input"))
      (node (ref "R15") (pin "2") (pinfunction "2_2") (pintype "input"))
      (node (ref "R16") (pin "2") (pinfunction "2_2") (pintype "input"))
      (node (ref "R17") (pin "2") (pinfunction "2_2") (pintype "input"))
      (node (ref "R18") (pin "2") (pinfunction "2_2") (pintype "input"))
      (node (ref "R2") (pin "1") (pinfunction "1_1") (pintype "input"))
      (node (ref "R3") (pin "1") (pinfunction "1_1") (pintype "input"))
      (node (ref "R4") (pin "1") (pinfunction "1_1") (pintype "input"))
      (node (ref "R5") (pin "1") (pinfunction "1_1") (pintype "input"))
      (node (ref "R51") (pin "2") (pinfunction "2_2") (pintype "input"))
      (node (ref "R6") (pin "1") (pinfunction "1_1") (pintype "input"))
      (node (ref "R7") (pin "1") (pinfunction "1_1") (pintype "input"))
      (node (ref "R8") (pin "1") (pinfunction "1_1") (pintype "input"))
      (node (ref "R9") (pin "2") (pinfunction "2_2") (pintype "input"))
      (node (ref "RN1") (pin "1") (pinfunction "1_1") (pintype "input"))
      (node (ref "RN1") (pin "2") (pinfunction "2_2") (pintype "input"))
      (node (ref "RN1") (pin "3") (pinfunction "3_3") (pintype "input"))
      (node (ref "RN1") (pin "4") (pinfunction "4_4") (pintype "input"))
      (node (ref "RN2") (pin "1") (pinfunction "1_1") (pintype "input"))
      (node (ref "RN2") (pin "2") (pinfunction "2_2") (pintype "input"))
      (node (ref "RN2") (pin "3") (pinfunction "3_3") (pintype "input"))
      (node (ref "RN2") (pin "4") (pinfunction "4_4") (pintype "input"))
      (node (ref "RN3") (pin "1") (pinfunction "1_1") (pintype "input"))
      (node (ref "RN3") (pin "2") (pinfunction "2_2") (pintype "input"))
      (node (ref "RN3") (pin "3") (pinfunction "3_3") (pintype "input"))
      (node (ref "RN3") (pin "4") (pinfunction "4_4") (pintype "input"))
      (node (ref "RN4") (pin "1") (pinfunction "1_1") (pintype "input"))
      (node (ref "RN4") (pin "2") (pinfunction "2_2") (pintype "input"))
      (node (ref "RN4") (pin "3") (pinfunction "3_3") (pintype "input"))
      (node (ref "RN4") (pin "4") (pinfunction "4_4") (pintype "input"))
      (node (ref "U1") (pin "15") (pinfunction "3V3_15") (pintype "unspecified"))
      (node (ref "U1") (pin "46") (pinfunction "3V3_46") (pintype "output"))
      (node (ref "U1") (pin "51") (pinfunction "3V3_51") (pintype "unspecified"))
      (node (ref "U17") (pin "24") (pinfunction "VCC_24") (pintype "input"))
      (node (ref "U2") (pin "24") (pinfunction "VCC_24") (pintype "unspecified"))
      (node (ref "U35") (pin "2") (pinfunction "VCCA_2") (pintype "unspecified"))
      (node (ref "U36") (pin "2") (pinfunction "VCCA_2") (pintype "unspecified"))
      (node (ref "U39") (pin "16") (pinfunction "VCC_16") (pintype "unspecified"))
      (node (ref "U42") (pin "1") (pinfunction "1_1") (pintype "unspecified"))
      (node (ref "U43") (pin "3") (pinfunction "3_3") (pintype "unspecified"))
      (node (ref "U44") (pin "15") (pinfunction "15_15") (pintype "unspecified"))
      (node (ref "U48") (pin "4") (pinfunction "4_4") (pintype "input"))
      (node (ref "U49") (pin "12") (pinfunction "12_12") (pintype "unspecified"))
      (node (ref "U49") (pin "3") (pinfunction "3_3") (pintype "unspecified"))
      (node (ref "U49") (pin "6") (pinfunction "6_6") (pintype "unspecified"))
      (node (ref "U49") (pin "9") (pinfunction "9_9") (pintype "unspecified"))
      (node (ref "U5") (pin "1") (pinfunction "1_1") (pintype "unspecified"))
      (node (ref "U50") (pin "12") (pinfunction "12_12") (pintype "unspecified"))
      (node (ref "U50") (pin "3") (pinfunction "3_3") (pintype "unspecified"))
      (node (ref "U50") (pin "6") (pinfunction "6_6") (pintype "unspecified"))
      (node (ref "U50") (pin "9") (pinfunction "9_9") (pintype "unspecified"))
      (node (ref "U6") (pin "1") (pinfunction "1_1") (pintype "unspecified"))
    )
    (net (code "4") (name "A0") (class "Default")
      (node (ref "U1") (pin "36") (pinfunction "14_A0_TX3_SPDIF_OUT_36") (pintype "bidirectional"))
      (node (ref "U39") (pin "10") (pinfunction "S1_10") (pintype "unspecified"))
      (node (ref "U43") (pin "13") (pinfunction "13_13") (pintype "unspecified"))
    )
    (net (code "5") (name "A1") (class "Default")
      (node (ref "U1") (pin "37") (pinfunction "15_A1_RX3_SPDIF_IN_37") (pintype "bidirectional"))
      (node (ref "U39") (pin "11") (pinfunction "S0_11") (pintype "unspecified"))
      (node (ref "U43") (pin "12") (pinfunction "12_12") (pintype "unspecified"))
    )
    (net (code "6") (name "A17") (class "Default")
      (node (ref "U1") (pin "33") (pinfunction "41_A17_33") (pintype "bidirectional"))
      (node (ref "U39") (pin "9") (pinfunction "S2_9") (pintype "unspecified"))
      (node (ref "U43") (pin "16") (pinfunction "16_16") (pintype "unspecified"))
    )
    (net (code "7") (name "ANALOG") (class "Default")
      (node (ref "U1") (pin "32") (pinfunction "40_A16_32") (pintype "bidirectional"))
      (node (ref "U39") (pin "3") (pinfunction "A_3") (pintype "unspecified"))
      (node (ref "U43") (pin "17") (pinfunction "17_17") (pintype "unspecified"))
    )
    (net (code "8") (name "ANALOG-EN") (class "Default")
      (node (ref "RN2") (pin "5") (pinfunction "5_5") (pintype "input"))
      (node (ref "U17") (pin "11") (pinfunction "P07_11") (pintype "input"))
      (node (ref "U39") (pin "6") (pinfunction "/E_6") (pintype "unspecified"))
    )
    (net (code "9") (name "BCLK2") (class "Default")
      (node (ref "U1") (pin "6") (pinfunction "4_BCLK2_6") (pintype "bidirectional"))
      (node (ref "U44") (pin "6") (pinfunction "6_6") (pintype "unspecified"))
      (node (ref "U49") (pin "2") (pinfunction "2_2") (pintype "unspecified"))
    )
    (net (code "10") (name "CRX1") (class "Default")
      (node (ref "CN10") (pin "3") (pinfunction "3_3") (pintype "unspecified"))
      (node (ref "U1") (pin "45") (pinfunction "23_A9_CRX1_MCLK1_45") (pintype "bidirectional"))
      (node (ref "U43") (pin "4") (pinfunction "4_4") (pintype "unspecified"))
    )
    (net (code "11") (name "CS") (class "Default")
      (node (ref "U1") (pin "12") (pinfunction "10_CS_MQSR_12") (pintype "bidirectional"))
      (node (ref "U44") (pin "12") (pinfunction "12_12") (pintype "unspecified"))
      (node (ref "U50") (pin "2") (pinfunction "2_2") (pintype "unspecified"))
    )
    (net (code "12") (name "CTX1") (class "Default")
      (node (ref "CN10") (pin "4") (pinfunction "4_4") (pintype "unspecified"))
      (node (ref "U1") (pin "44") (pinfunction "22_A8_CTX1_44") (pintype "bidirectional"))
      (node (ref "U43") (pin "5") (pinfunction "5_5") (pintype "unspecified"))
    )
    (net (code "13") (name "CUST") (class "Default")
      (node (ref "C3") (pin "1") (pinfunction "1_1") (pintype "input"))
      (node (ref "CUSTOM1") (pin "2") (pinfunction "2_2") (pintype "input"))
      (node (ref "U19") (pin "5") (pinfunction "5_5") (pintype "unspecified"))
      (node (ref "U20") (pin "5") (pinfunction "5_5") (pintype "unspecified"))
      (node (ref "U21") (pin "5") (pinfunction "5_5") (pintype "unspecified"))
      (node (ref "U22") (pin "5") (pinfunction "5_5") (pintype "unspecified"))
      (node (ref "U23") (pin "5") (pinfunction "5_5") (pintype "unspecified"))
      (node (ref "U24") (pin "5") (pinfunction "5_5") (pintype "unspecified"))
      (node (ref "U25") (pin "5") (pinfunction "5_5") (pintype "unspecified"))
      (node (ref "U26") (pin "5") (pinfunction "5_5") (pintype "unspecified"))
      (node (ref "U27") (pin "5") (pinfunction "5_5") (pintype "unspecified"))
      (node (ref "U28") (pin "5") (pinfunction "5_5") (pintype "unspecified"))
      (node (ref "U29") (pin "5") (pinfunction "5_5") (pintype "unspecified"))
      (node (ref "U30") (pin "5") (pinfunction "5_5") (pintype "unspecified"))
      (node (ref "U31") (pin "5") (pinfunction "5_5") (pintype "unspecified"))
      (node (ref "U32") (pin "5") (pinfunction "5_5") (pintype "unspecified"))
      (node (ref "U33") (pin "5") (pinfunction "5_5") (pintype "unspecified"))
      (node (ref "U34") (pin "5") (pinfunction "5_5") (pintype "unspecified"))
    )
    (net (code "14") (name "ECHO0") (class "Default")
      (node (ref "U1") (pin "22") (pinfunction "30_CRX3_22") (pintype "bidirectional"))
      (node (ref "U35") (pin "7") (pinfunction "A6_7") (pintype "unspecified"))
      (node (ref "U44") (pin "22") (pinfunction "22_22") (pintype "unspecified"))
    )
    (net (code "15") (name "ECHO1") (class "Default")
      (node (ref "U1") (pin "24") (pinfunction "32_OUT1B_24") (pintype "bidirectional"))
      (node (ref "U35") (pin "5") (pinfunction "A4_5") (pintype "unspecified"))
      (node (ref "U44") (pin "24") (pinfunction "24_24") (pintype "unspecified"))
    )
    (net (code "16") (name "ECHO2") (class "Default")
      (node (ref "U1") (pin "26") (pinfunction "34_RX8_26") (pintype "bidirectional"))
      (node (ref "U36") (pin "7") (pinfunction "A6_7") (pintype "unspecified"))
      (node (ref "U43") (pin "23") (pinfunction "23_23") (pintype "unspecified"))
    )
    (net (code "17") (name "ECHO3") (class "Default")
      (node (ref "U1") (pin "28") (pinfunction "36_CS_28") (pintype "bidirectional"))
      (node (ref "U36") (pin "5") (pinfunction "A4_5") (pintype "unspecified"))
      (node (ref "U43") (pin "21") (pinfunction "21_21") (pintype "unspecified"))
    )
    (net (code "18") (name "GND") (class "Default")
      (node (ref "3.3VEXT1") (pin "1") (pinfunction "1_1") (pintype "input"))
      (node (ref "5VEXT1") (pin "1") (pinfunction "1_1") (pintype "input"))
      (node (ref "C1") (pin "2") (pinfunction "2_2") (pintype "input"))
      (node (ref "C2") (pin "2") (pinfunction "2_2") (pintype "input"))
      (node (ref "C3") (pin "2") (pinfunction "2_2") (pintype "input"))
      (node (ref "C4") (pin "2") (pinfunction "2_2") (pintype "unspecified"))
      (node (ref "CN10") (pin "2") (pinfunction "2_2") (pintype "unspecified"))
      (node (ref "CN11") (pin "2") (pinfunction "2_2") (pintype "unspecified"))
      (node (ref "CN12") (pin "2") (pinfunction "2_2") (pintype "unspecified"))
      (node (ref "CN56") (pin "1") (pinfunction "1_1") (pintype "unspecified"))
      (node (ref "CN57") (pin "1") (pinfunction "1_1") (pintype "unspecified"))
      (node (ref "CN58") (pin "1") (pinfunction "1_1") (pintype "unspecified"))
      (node (ref "CN59") (pin "1") (pinfunction "1_1") (pintype "unspecified"))
      (node (ref "CN60") (pin "1") (pinfunction "1_1") (pintype "unspecified"))
      (node (ref "CN61") (pin "1") (pinfunction "1_1") (pintype "unspecified"))
      (node (ref "CN62") (pin "1") (pinfunction "1_1") (pintype "unspecified"))
      (node (ref "CN63") (pin "1") (pinfunction "1_1") (pintype "unspecified"))
      (node (ref "CN72") (pin "1") (pinfunction "1_1") (pintype "unspecified"))
      (node (ref "CN73") (pin "1") (pinfunction "1_1") (pintype "unspecified"))
      (node (ref "CN74") (pin "1") (pinfunction "1_1") (pintype "unspecified"))
      (node (ref "CN75") (pin "1") (pinfunction "1_1") (pintype "unspecified"))
      (node (ref "CN76") (pin "1") (pinfunction "1_1") (pintype "unspecified"))
      (node (ref "CN77") (pin "1") (pinfunction "1_1") (pintype "unspecified"))
      (node (ref "CN78") (pin "1") (pinfunction "1_1") (pintype "unspecified"))
      (node (ref "CN79") (pin "1") (pinfunction "1_1") (pintype "unspecified"))
      (node (ref "CN80") (pin "1") (pinfunction "1_1") (pintype "unspecified"))
      (node (ref "CN81") (pin "1") (pinfunction "1_1") (pintype "unspecified"))
      (node (ref "CN82") (pin "1") (pinfunction "1_1") (pintype "unspecified"))
      (node (ref "CN83") (pin "1") (pinfunction "1_1") (pintype "unspecified"))
      (node (ref "CN84") (pin "1") (pinfunction "1_1") (pintype "unspecified"))
      (node (ref "CN85") (pin "1") (pinfunction "1_1") (pintype "unspecified"))
      (node (ref "CN86") (pin "1") (pinfunction "1_1") (pintype "unspecified"))
      (node (ref "CN87") (pin "1") (pinfunction "1_1") (pintype "unspecified"))
      (node (ref "CR2032") (pin "2") (pinfunction "2_2") (pintype "input"))
      (node (ref "CUSTOM1") (pin "1") (pinfunction "1_1") (pintype "input"))
      (node (ref "ETHERNET1") (pin "8") (pinfunction "8_8") (pintype "unspecified"))
      (node (ref "ETHERNET1") (pin "9") (pinfunction "LLED-_9") (pintype "unspecified"))
      (node (ref "H18") (pin "1") (pinfunction "1_1") (pintype "unspecified"))
      (node (ref "H18") (pin "3") (pinfunction "3_3") (pintype "unspecified"))
      (node (ref "I2C0") (pin "1") (pinfunction "1_1") (pintype "unspecified"))
      (node (ref "I2C1") (pin "1") (pinfunction "1_1") (pintype "unspecified"))
      (node (ref "I2C1-A0") (pin "3") (pinfunction "3_3") (pintype "unspecified"))
      (node (ref "I2C1-A1") (pin "3") (pinfunction "3_3") (pintype "unspecified"))
      (node (ref "I2C1-A2") (pin "3") (pinfunction "3_3") (pintype "unspecified"))
      (node (ref "I2C2") (pin "1") (pinfunction "1_1") (pintype "unspecified"))
      (node (ref "I2C3") (pin "1") (pinfunction "1_1") (pintype "unspecified"))
      (node (ref "I2C4") (pin "1") (pinfunction "1_1") (pintype "unspecified"))
      (node (ref "I2C5") (pin "1") (pinfunction "1_1") (pintype "unspecified"))
      (node (ref "I2C6") (pin "1") (pinfunction "1_1") (pintype "unspecified"))
      (node (ref "I2C7") (pin "1") (pinfunction "1_1") (pintype "unspecified"))
      (node (ref "I2CX-A0") (pin "3") (pinfunction "3_3") (pintype "unspecified"))
      (node (ref "I2CX-A1") (pin "3") (pinfunction "3_3") (pintype "unspecified"))
      (node (ref "I2CX-A2") (pin "3") (pinfunction "3_3") (pintype "unspecified"))
      (node (ref "LED1") (pin "2") (pinfunction "K_2") (pintype "unspecified"))
      (node (ref "LED10") (pin "2") (pinfunction "K_2") (pintype "unspecified"))
      (node (ref "LED11") (pin "2") (pinfunction "K_2") (pintype "unspecified"))
      (node (ref "LED12") (pin "2") (pinfunction "K_2") (pintype "unspecified"))
      (node (ref "LED13") (pin "2") (pinfunction "K_2") (pintype "unspecified"))
      (node (ref "LED14") (pin "2") (pinfunction "K_2") (pintype "unspecified"))
      (node (ref "LED15") (pin "2") (pinfunction "K_2") (pintype "unspecified"))
      (node (ref "LED16") (pin "2") (pinfunction "K_2") (pintype "unspecified"))
      (node (ref "LED2") (pin "2") (pinfunction "K_2") (pintype "unspecified"))
      (node (ref "LED3") (pin "2") (pinfunction "K_2") (pintype "unspecified"))
      (node (ref "LED4") (pin "2") (pinfunction "K_2") (pintype "unspecified"))
      (node (ref "LED5") (pin "2") (pinfunction "K_2") (pintype "unspecified"))
      (node (ref "LED6") (pin "2") (pinfunction "K_2") (pintype "unspecified"))
      (node (ref "LED7") (pin "2") (pinfunction "K_2") (pintype "unspecified"))
      (node (ref "LED8") (pin "2") (pinfunction "K_2") (pintype "unspecified"))
      (node (ref "LED9") (pin "2") (pinfunction "K_2") (pintype "unspecified"))
      (node (ref "PWM-A0") (pin "3") (pinfunction "3_3") (pintype "unspecified"))
      (node (ref "PWM-A1") (pin "3") (pinfunction "3_3") (pintype "unspecified"))
      (node (ref "PWM-A2") (pin "3") (pinfunction "3_3") (pintype "unspecified"))
      (node (ref "PWM-A3") (pin "3") (pinfunction "3_3") (pintype "unspecified"))
      (node (ref "PWM-A4") (pin "3") (pinfunction "3_3") (pintype "unspecified"))
      (node (ref "PWM-A5") (pin "3") (pinfunction "3_3") (pintype "unspecified"))
      (node (ref "SONAR0") (pin "2") (pinfunction "2_2") (pintype "unspecified"))
      (node (ref "SONAR1") (pin "2") (pinfunction "2_2") (pintype "unspecified"))
      (node (ref "SONAR2") (pin "2") (pinfunction "2_2") (pintype "unspecified"))
      (node (ref "SONAR3") (pin "2") (pinfunction "2_2") (pintype "unspecified"))
      (node (ref "U1") (pin "1") (pinfunction "GND_1") (pintype "unspecified"))
      (node (ref "U1") (pin "34") (pinfunction "GND_34") (pintype "unspecified"))
      (node (ref "U1") (pin "47") (pinfunction "GND_47") (pintype "output"))
      (node (ref "U1") (pin "52") (pinfunction "GND_52") (pintype "input"))
      (node (ref "U1") (pin "58") (pinfunction "GND_58") (pintype "unspecified"))
      (node (ref "U1") (pin "59") (pinfunction "GND_59") (pintype "unspecified"))
      (node (ref "U1") (pin "64") (pinfunction "GND_64") (pintype "unspecified"))
      (node (ref "U17") (pin "12") (pinfunction "GND_12") (pintype "input"))
      (node (ref "U18") (pin "14") (pinfunction "VSS_14") (pintype "input"))
      (node (ref "U18") (pin "25") (pinfunction "EXTCLK_25") (pintype "input"))
      (node (ref "U2") (pin "12") (pinfunction "GND_12") (pintype "unspecified"))
      (node (ref "U35") (pin "9") (pinfunction "GND_9") (pintype "unspecified"))
      (node (ref "U36") (pin "9") (pinfunction "GND_9") (pintype "unspecified"))
      (node (ref "U39") (pin "7") (pinfunction "VEE_7") (pintype "unspecified"))
      (node (ref "U39") (pin "8") (pinfunction "GND_8") (pintype "unspecified"))
      (node (ref "U4") (pin "2") (pinfunction "2_2") (pintype "unspecified"))
      (node (ref "U40") (pin "2") (pinfunction "2_2") (pintype "unspecified"))
      (node (ref "U41") (pin "2") (pinfunction "2_2") (pintype "unspecified"))
      (node (ref "U42") (pin "2") (pinfunction "2_2") (pintype "unspecified"))
      (node (ref "U43") (pin "15") (pinfunction "15_15") (pintype "unspecified"))
      (node (ref "U43") (pin "2") (pinfunction "2_2") (pintype "unspecified"))
      (node (ref "U44") (pin "1") (pinfunction "1_1") (pintype "unspecified"))
      (node (ref "U46") (pin "4") (pinfunction "4_4") (pintype "input"))
      (node (ref "U46") (pin "5") (pinfunction "5_5") (pintype "input"))
      (node (ref "U47") (pin "4") (pinfunction "4_4") (pintype "input"))
      (node (ref "U48") (pin "3") (pinfunction "3_3") (pintype "input"))
      (node (ref "U49") (pin "1") (pinfunction "1_1") (pintype "unspecified"))
      (node (ref "U49") (pin "10") (pinfunction "10_10") (pintype "unspecified"))
      (node (ref "U49") (pin "4") (pinfunction "4_4") (pintype "unspecified"))
      (node (ref "U49") (pin "7") (pinfunction "7_7") (pintype "unspecified"))
      (node (ref "U5") (pin "2") (pinfunction "2_2") (pintype "unspecified"))
      (node (ref "U50") (pin "1") (pinfunction "1_1") (pintype "unspecified"))
      (node (ref "U50") (pin "10") (pinfunction "10_10") (pintype "unspecified"))
      (node (ref "U50") (pin "4") (pinfunction "4_4") (pintype "unspecified"))
      (node (ref "U50") (pin "7") (pinfunction "7_7") (pintype "unspecified"))
      (node (ref "U6") (pin "2") (pinfunction "2_2") (pintype "unspecified"))
      (node (ref "U8") (pin "2") (pinfunction "2_2") (pintype "unspecified"))
      (node (ref "USB1") (pin "4") (pinfunction "GND_4") (pintype "input"))
      (node (ref "USB1") (pin "5") (pinfunction "5_5") (pintype "input"))
    )
    (net (code "19") (name "I2C1-RESET") (class "Default")
      (node (ref "RN1") (pin "8") (pinfunction "8_8") (pintype "input"))
      (node (ref "U17") (pin "4") (pinfunction "P00_4") (pintype "input"))
      (node (ref "U2") (pin "3") (pinfunction "RESET#_3") (pintype "unspecified"))
    )
    (net (code "20") (name "I2C2-RESET") (class "Default")
      (node (ref "RN1") (pin "7") (pinfunction "7_7") (pintype "input"))
      (node (ref "U17") (pin "5") (pinfunction "P01_5") (pintype "input"))
    )
    (net (code "21") (name "IN1") (class "Default")
      (node (ref "U1") (pin "30") (pinfunction "38_CS1_IN1_30") (pintype "bidirectional"))
      (node (ref "U43") (pin "19") (pinfunction "19_19") (pintype "unspecified"))
      (node (ref "U50") (pin "5") (pinfunction "5_5") (pintype "unspecified"))
    )
    (net (code "22") (name "IN2") (class "Default")
      (node (ref "R51") (pin "1") (pinfunction "1_1") (pintype "input"))
      (node (ref "U1") (pin "7") (pinfunction "5_IN2_7") (pintype "bidirectional"))
      (node (ref "U17") (pin "1") (pinfunction "INT#_1") (pintype "input"))
      (node (ref "U44") (pin "7") (pinfunction "7_7") (pintype "unspecified"))
    )
    (net (code "23") (name "LRCLK2") (class "Default")
      (node (ref "U1") (pin "5") (pinfunction "3_LRCLK2_5") (pintype "bidirectional"))
      (node (ref "U42") (pin "5") (pinfunction "5_5") (pintype "unspecified"))
      (node (ref "U44") (pin "5") (pinfunction "5_5") (pintype "unspecified"))
    )
    (net (code "24") (name "MISO") (class "Default")
      (node (ref "U1") (pin "14") (pinfunction "12_MISO_MQSL_14") (pintype "bidirectional"))
      (node (ref "U4") (pin "4") (pinfunction "4_4") (pintype "unspecified"))
      (node (ref "U44") (pin "14") (pinfunction "14_14") (pintype "unspecified"))
      (node (ref "U8") (pin "4") (pinfunction "4_4") (pintype "unspecified"))
    )
    (net (code "25") (name "MISO1") (class "Default")
      (node (ref "U1") (pin "31") (pinfunction "39_MISO1_OUT1A_31") (pintype "bidirectional"))
      (node (ref "U40") (pin "4") (pinfunction "4_4") (pintype "unspecified"))
      (node (ref "U41") (pin "4") (pinfunction "4_4") (pintype "unspecified"))
      (node (ref "U43") (pin "18") (pinfunction "18_18") (pintype "unspecified"))
    )
    (net (code "26") (name "MOSI") (class "Default")
      (node (ref "U1") (pin "13") (pinfunction "11_MOSI_CTX1_13") (pintype "bidirectional"))
      (node (ref "U4") (pin "3") (pinfunction "3_3") (pintype "unspecified"))
      (node (ref "U44") (pin "13") (pinfunction "13_13") (pintype "unspecified"))
      (node (ref "U8") (pin "3") (pinfunction "3_3") (pintype "unspecified"))
    )
    (net (code "27") (name "MOSI1") (class "Default")
      (node (ref "U1") (pin "18") (pinfunction "26_A12_MOSI1_18") (pintype "bidirectional"))
      (node (ref "U40") (pin "3") (pinfunction "3_3") (pintype "unspecified"))
      (node (ref "U41") (pin "3") (pinfunction "3_3") (pintype "unspecified"))
      (node (ref "U44") (pin "18") (pinfunction "18_18") (pintype "unspecified"))
    )
    (net (code "28") (name "Net-(C4-Pad1)") (class "Default")
      (node (ref "C4") (pin "1") (pinfunction "1_1") (pintype "unspecified"))
      (node (ref "ETHERNET1") (pin "2") (pinfunction "2_2") (pintype "unspecified"))
      (node (ref "ETHERNET1") (pin "5") (pinfunction "5_5") (pintype "unspecified"))
    )
    (net (code "29") (name "Net-(CN72-Pad2)") (class "Default")
      (node (ref "CN72") (pin "2") (pinfunction "2_2") (pintype "unspecified"))
      (node (ref "U19") (pin "2") (pinfunction "2_2") (pintype "unspecified"))
      (node (ref "U19") (pin "4") (pinfunction "4_4") (pintype "unspecified"))
      (node (ref "U19") (pin "6") (pinfunction "6_6") (pintype "unspecified"))
    )
    (net (code "30") (name "Net-(CN72-Pad3)") (class "Default")
      (node (ref "CN72") (pin "3") (pinfunction "3_3") (pintype "unspecified"))
      (node (ref "F1") (pin "1") (pinfunction "1_1") (pintype "unspecified"))
      (node (ref "H3") (pin "1") (pinfunction "1_1") (pintype "unspecified"))
    )
    (net (code "31") (name "Net-(CN73-Pad2)") (class "Default")
      (node (ref "CN73") (pin "2") (pinfunction "2_2") (pintype "unspecified"))
      (node (ref "U20") (pin "2") (pinfunction "2_2") (pintype "unspecified"))
      (node (ref "U20") (pin "4") (pinfunction "4_4") (pintype "unspecified"))
      (node (ref "U20") (pin "6") (pinfunction "6_6") (pintype "unspecified"))
    )
    (net (code "32") (name "Net-(CN73-Pad3)") (class "Default")
      (node (ref "CN73") (pin "3") (pinfunction "3_3") (pintype "unspecified"))
      (node (ref "F1") (pin "2") (pinfunction "2_2") (pintype "unspecified"))
      (node (ref "H2") (pin "1") (pinfunction "1_1") (pintype "unspecified"))
    )
    (net (code "33") (name "Net-(CN74-Pad2)") (class "Default")
      (node (ref "CN74") (pin "2") (pinfunction "2_2") (pintype "unspecified"))
      (node (ref "U21") (pin "2") (pinfunction "2_2") (pintype "unspecified"))
      (node (ref "U21") (pin "4") (pinfunction "4_4") (pintype "unspecified"))
      (node (ref "U21") (pin "6") (pinfunction "6_6") (pintype "unspecified"))
    )
    (net (code "34") (name "Net-(CN74-Pad3)") (class "Default")
      (node (ref "CN74") (pin "3") (pinfunction "3_3") (pintype "unspecified"))
      (node (ref "F1") (pin "3") (pinfunction "3_3") (pintype "unspecified"))
      (node (ref "H4") (pin "1") (pinfunction "1_1") (pintype "unspecified"))
    )
    (net (code "35") (name "Net-(CN75-Pad2)") (class "Default")
      (node (ref "CN75") (pin "2") (pinfunction "2_2") (pintype "unspecified"))
      (node (ref "U22") (pin "2") (pinfunction "2_2") (pintype "unspecified"))
      (node (ref "U22") (pin "4") (pinfunction "4_4") (pintype "unspecified"))
      (node (ref "U22") (pin "6") (pinfunction "6_6") (pintype "unspecified"))
    )
    (net (code "36") (name "Net-(CN75-Pad3)") (class "Default")
      (node (ref "CN75") (pin "3") (pinfunction "3_3") (pintype "unspecified"))
      (node (ref "F1") (pin "4") (pinfunction "4_4") (pintype "unspecified"))
      (node (ref "H5") (pin "1") (pinfunction "1_1") (pintype "unspecified"))
    )
    (net (code "37") (name "Net-(CN76-Pad2)") (class "Default")
      (node (ref "CN76") (pin "2") (pinfunction "2_2") (pintype "unspecified"))
      (node (ref "U23") (pin "2") (pinfunction "2_2") (pintype "unspecified"))
      (node (ref "U23") (pin "4") (pinfunction "4_4") (pintype "unspecified"))
      (node (ref "U23") (pin "6") (pinfunction "6_6") (pintype "unspecified"))
    )
    (net (code "38") (name "Net-(CN76-Pad3)") (class "Default")
      (node (ref "CN76") (pin "3") (pinfunction "3_3") (pintype "unspecified"))
      (node (ref "F2") (pin "1") (pinfunction "1_1") (pintype "unspecified"))
      (node (ref "H6") (pin "1") (pinfunction "1_1") (pintype "unspecified"))
    )
    (net (code "39") (name "Net-(CN77-Pad2)") (class "Default")
      (node (ref "CN77") (pin "2") (pinfunction "2_2") (pintype "unspecified"))
      (node (ref "U24") (pin "2") (pinfunction "2_2") (pintype "unspecified"))
      (node (ref "U24") (pin "4") (pinfunction "4_4") (pintype "unspecified"))
      (node (ref "U24") (pin "6") (pinfunction "6_6") (pintype "unspecified"))
    )
    (net (code "40") (name "Net-(CN77-Pad3)") (class "Default")
      (node (ref "CN77") (pin "3") (pinfunction "3_3") (pintype "unspecified"))
      (node (ref "F2") (pin "2") (pinfunction "2_2") (pintype "unspecified"))
      (node (ref "H7") (pin "1") (pinfunction "1_1") (pintype "unspecified"))
    )
    (net (code "41") (name "Net-(CN78-Pad2)") (class "Default")
      (node (ref "CN78") (pin "2") (pinfunction "2_2") (pintype "unspecified"))
      (node (ref "U25") (pin "2") (pinfunction "2_2") (pintype "unspecified"))
      (node (ref "U25") (pin "4") (pinfunction "4_4") (pintype "unspecified"))
      (node (ref "U25") (pin "6") (pinfunction "6_6") (pintype "unspecified"))
    )
    (net (code "42") (name "Net-(CN78-Pad3)") (class "Default")
      (node (ref "CN78") (pin "3") (pinfunction "3_3") (pintype "unspecified"))
      (node (ref "F2") (pin "3") (pinfunction "3_3") (pintype "unspecified"))
      (node (ref "H8") (pin "1") (pinfunction "1_1") (pintype "unspecified"))
    )
    (net (code "43") (name "Net-(CN79-Pad2)") (class "Default")
      (node (ref "CN79") (pin "2") (pinfunction "2_2") (pintype "unspecified"))
      (node (ref "U26") (pin "2") (pinfunction "2_2") (pintype "unspecified"))
      (node (ref "U26") (pin "4") (pinfunction "4_4") (pintype "unspecified"))
      (node (ref "U26") (pin "6") (pinfunction "6_6") (pintype "unspecified"))
    )
    (net (code "44") (name "Net-(CN79-Pad3)") (class "Default")
      (node (ref "CN79") (pin "3") (pinfunction "3_3") (pintype "unspecified"))
      (node (ref "F2") (pin "4") (pinfunction "4_4") (pintype "unspecified"))
      (node (ref "H9") (pin "1") (pinfunction "1_1") (pintype "unspecified"))
    )
    (net (code "45") (name "Net-(CN80-Pad2)") (class "Default")
      (node (ref "CN80") (pin "2") (pinfunction "2_2") (pintype "unspecified"))
      (node (ref "U27") (pin "2") (pinfunction "2_2") (pintype "unspecified"))
      (node (ref "U27") (pin "4") (pinfunction "4_4") (pintype "unspecified"))
      (node (ref "U27") (pin "6") (pinfunction "6_6") (pintype "unspecified"))
    )
    (net (code "46") (name "Net-(CN80-Pad3)") (class "Default")
      (node (ref "CN80") (pin "3") (pinfunction "3_3") (pintype "unspecified"))
      (node (ref "F3") (pin "1") (pinfunction "1_1") (pintype "unspecified"))
      (node (ref "H10") (pin "1") (pinfunction "1_1") (pintype "unspecified"))
    )
    (net (code "47") (name "Net-(CN81-Pad2)") (class "Default")
      (node (ref "CN81") (pin "2") (pinfunction "2_2") (pintype "unspecified"))
      (node (ref "U28") (pin "2") (pinfunction "2_2") (pintype "unspecified"))
      (node (ref "U28") (pin "4") (pinfunction "4_4") (pintype "unspecified"))
      (node (ref "U28") (pin "6") (pinfunction "6_6") (pintype "unspecified"))
    )
    (net (code "48") (name "Net-(CN81-Pad3)") (class "Default")
      (node (ref "CN81") (pin "3") (pinfunction "3_3") (pintype "unspecified"))
      (node (ref "F3") (pin "2") (pinfunction "2_2") (pintype "unspecified"))
      (node (ref "H11") (pin "1") (pinfunction "1_1") (pintype "unspecified"))
    )
    (net (code "49") (name "Net-(CN82-Pad2)") (class "Default")
      (node (ref "CN82") (pin "2") (pinfunction "2_2") (pintype "unspecified"))
      (node (ref "U29") (pin "2") (pinfunction "2_2") (pintype "unspecified"))
      (node (ref "U29") (pin "4") (pinfunction "4_4") (pintype "unspecified"))
      (node (ref "U29") (pin "6") (pinfunction "6_6") (pintype "unspecified"))
    )
    (net (code "50") (name "Net-(CN82-Pad3)") (class "Default")
      (node (ref "CN82") (pin "3") (pinfunction "3_3") (pintype "unspecified"))
      (node (ref "F3") (pin "3") (pinfunction "3_3") (pintype "unspecified"))
      (node (ref "H12") (pin "1") (pinfunction "1_1") (pintype "unspecified"))
    )
    (net (code "51") (name "Net-(CN83-Pad2)") (class "Default")
      (node (ref "CN83") (pin "2") (pinfunction "2_2") (pintype "unspecified"))
      (node (ref "U30") (pin "2") (pinfunction "2_2") (pintype "unspecified"))
      (node (ref "U30") (pin "4") (pinfunction "4_4") (pintype "unspecified"))
      (node (ref "U30") (pin "6") (pinfunction "6_6") (pintype "unspecified"))
    )
    (net (code "52") (name "Net-(CN83-Pad3)") (class "Default")
      (node (ref "CN83") (pin "3") (pinfunction "3_3") (pintype "unspecified"))
      (node (ref "F3") (pin "4") (pinfunction "4_4") (pintype "unspecified"))
      (node (ref "H13") (pin "1") (pinfunction "1_1") (pintype "unspecified"))
    )
    (net (code "53") (name "Net-(CN84-Pad2)") (class "Default")
      (node (ref "CN84") (pin "2") (pinfunction "2_2") (pintype "unspecified"))
      (node (ref "U31") (pin "2") (pinfunction "2_2") (pintype "unspecified"))
      (node (ref "U31") (pin "4") (pinfunction "4_4") (pintype "unspecified"))
      (node (ref "U31") (pin "6") (pinfunction "6_6") (pintype "unspecified"))
    )
    (net (code "54") (name "Net-(CN84-Pad3)") (class "Default")
      (node (ref "CN84") (pin "3") (pinfunction "3_3") (pintype "unspecified"))
      (node (ref "F4") (pin "1") (pinfunction "1_1") (pintype "unspecified"))
      (node (ref "H14") (pin "1") (pinfunction "1_1") (pintype "unspecified"))
    )
    (net (code "55") (name "Net-(CN85-Pad2)") (class "Default")
      (node (ref "CN85") (pin "2") (pinfunction "2_2") (pintype "unspecified"))
      (node (ref "U32") (pin "2") (pinfunction "2_2") (pintype "unspecified"))
      (node (ref "U32") (pin "4") (pinfunction "4_4") (pintype "unspecified"))
      (node (ref "U32") (pin "6") (pinfunction "6_6") (pintype "unspecified"))
    )
    (net (code "56") (name "Net-(CN85-Pad3)") (class "Default")
      (node (ref "CN85") (pin "3") (pinfunction "3_3") (pintype "unspecified"))
      (node (ref "F4") (pin "2") (pinfunction "2_2") (pintype "unspecified"))
      (node (ref "H15") (pin "1") (pinfunction "1_1") (pintype "unspecified"))
    )
    (net (code "57") (name "Net-(CN86-Pad2)") (class "Default")
      (node (ref "CN86") (pin "2") (pinfunction "2_2") (pintype "unspecified"))
      (node (ref "U33") (pin "2") (pinfunction "2_2") (pintype "unspecified"))
      (node (ref "U33") (pin "4") (pinfunction "4_4") (pintype "unspecified"))
      (node (ref "U33") (pin "6") (pinfunction "6_6") (pintype "unspecified"))
    )
    (net (code "58") (name "Net-(CN86-Pad3)") (class "Default")
      (node (ref "CN86") (pin "3") (pinfunction "3_3") (pintype "unspecified"))
      (node (ref "F4") (pin "3") (pinfunction "3_3") (pintype "unspecified"))
      (node (ref "H16") (pin "1") (pinfunction "1_1") (pintype "unspecified"))
    )
    (net (code "59") (name "Net-(CN87-Pad2)") (class "Default")
      (node (ref "CN87") (pin "2") (pinfunction "2_2") (pintype "unspecified"))
      (node (ref "U34") (pin "2") (pinfunction "2_2") (pintype "unspecified"))
      (node (ref "U34") (pin "4") (pinfunction "4_4") (pintype "unspecified"))
      (node (ref "U34") (pin "6") (pinfunction "6_6") (pintype "unspecified"))
    )
    (net (code "60") (name "Net-(CN87-Pad3)") (class "Default")
      (node (ref "CN87") (pin "3") (pinfunction "3_3") (pintype "unspecified"))
      (node (ref "F4") (pin "4") (pinfunction "4_4") (pintype "unspecified"))
      (node (ref "H17") (pin "1") (pinfunction "1_1") (pintype "unspecified"))
    )
    (net (code "61") (name "Net-(ETHERNET1-LLED+)") (class "Default")
      (node (ref "ETHERNET1") (pin "10") (pinfunction "LLED+_10") (pintype "unspecified"))
      (node (ref "U1") (pin "61") (pinfunction "LED_61") (pintype "bidirectional"))
      (node (ref "U47") (pin "3") (pinfunction "3_3") (pintype "input"))
    )
    (net (code "62") (name "Net-(I2C0-Pad2)") (class "Default")
      (node (ref "I2C0") (pin "2") (pinfunction "2_2") (pintype "unspecified"))
      (node (ref "I2C1") (pin "2") (pinfunction "2_2") (pintype "unspecified"))
      (node (ref "I2C1-PWR1") (pin "2") (pinfunction "2_2") (pintype "unspecified"))
      (node (ref "I2C2") (pin "2") (pinfunction "2_2") (pintype "unspecified"))
      (node (ref "I2C3") (pin "2") (pinfunction "2_2") (pintype "unspecified"))
      (node (ref "I2C4") (pin "2") (pinfunction "2_2") (pintype "unspecified"))
      (node (ref "I2C5") (pin "2") (pinfunction "2_2") (pintype "unspecified"))
      (node (ref "I2C6") (pin "2") (pinfunction "2_2") (pintype "unspecified"))
      (node (ref "I2C7") (pin "2") (pinfunction "2_2") (pintype "unspecified"))
    )
    (net (code "63") (name "Net-(LED1-A)") (class "Default")
      (node (ref "H2") (pin "2") (pinfunction "2_2") (pintype "unspecified"))
      (node (ref "LED1") (pin "1") (pinfunction "A_1") (pintype "unspecified"))
    )
    (net (code "64") (name "Net-(LED2-A)") (class "Default")
      (node (ref "H3") (pin "2") (pinfunction "2_2") (pintype "unspecified"))
      (node (ref "LED2") (pin "1") (pinfunction "A_1") (pintype "unspecified"))
    )
    (net (code "65") (name "Net-(LED3-A)") (class "Default")
      (node (ref "H4") (pin "2") (pinfunction "2_2") (pintype "unspecified"))
      (node (ref "LED3") (pin "1") (pinfunction "A_1") (pintype "unspecified"))
    )
    (net (code "66") (name "Net-(LED4-A)") (class "Default")
      (node (ref "H5") (pin "2") (pinfunction "2_2") (pintype "unspecified"))
      (node (ref "LED4") (pin "1") (pinfunction "A_1") (pintype "unspecified"))
    )
    (net (code "67") (name "Net-(LED5-A)") (class "Default")
      (node (ref "H6") (pin "2") (pinfunction "2_2") (pintype "unspecified"))
      (node (ref "LED5") (pin "1") (pinfunction "A_1") (pintype "unspecified"))
    )
    (net (code "68") (name "Net-(LED6-A)") (class "Default")
      (node (ref "H7") (pin "2") (pinfunction "2_2") (pintype "unspecified"))
      (node (ref "LED6") (pin "1") (pinfunction "A_1") (pintype "unspecified"))
    )
    (net (code "69") (name "Net-(LED7-A)") (class "Default")
      (node (ref "H8") (pin "2") (pinfunction "2_2") (pintype "unspecified"))
      (node (ref "LED7") (pin "1") (pinfunction "A_1") (pintype "unspecified"))
    )
    (net (code "70") (name "Net-(LED8-A)") (class "Default")
      (node (ref "H9") (pin "2") (pinfunction "2_2") (pintype "unspecified"))
      (node (ref "LED8") (pin "1") (pinfunction "A_1") (pintype "unspecified"))
    )
    (net (code "71") (name "Net-(LED9-A)") (class "Default")
      (node (ref "H10") (pin "2") (pinfunction "2_2") (pintype "unspecified"))
      (node (ref "LED9") (pin "1") (pinfunction "A_1") (pintype "unspecified"))
    )
    (net (code "72") (name "Net-(LED10-A)") (class "Default")
      (node (ref "H11") (pin "2") (pinfunction "2_2") (pintype "unspecified"))
      (node (ref "LED10") (pin "1") (pinfunction "A_1") (pintype "unspecified"))
    )
    (net (code "73") (name "Net-(LED11-A)") (class "Default")
      (node (ref "H12") (pin "2") (pinfunction "2_2") (pintype "unspecified"))
      (node (ref "LED11") (pin "1") (pinfunction "A_1") (pintype "unspecified"))
    )
    (net (code "74") (name "Net-(LED12-A)") (class "Default")
      (node (ref "H13") (pin "2") (pinfunction "2_2") (pintype "unspecified"))
      (node (ref "LED12") (pin "1") (pinfunction "A_1") (pintype "unspecified"))
    )
    (net (code "75") (name "Net-(LED13-A)") (class "Default")
      (node (ref "H14") (pin "2") (pinfunction "2_2") (pintype "unspecified"))
      (node (ref "LED13") (pin "1") (pinfunction "A_1") (pintype "unspecified"))
    )
    (net (code "76") (name "Net-(LED14-A)") (class "Default")
      (node (ref "H15") (pin "2") (pinfunction "2_2") (pintype "unspecified"))
      (node (ref "LED14") (pin "1") (pinfunction "A_1") (pintype "unspecified"))
    )
    (net (code "77") (name "Net-(LED15-A)") (class "Default")
      (node (ref "H16") (pin "2") (pinfunction "2_2") (pintype "unspecified"))
      (node (ref "LED15") (pin "1") (pinfunction "A_1") (pintype "unspecified"))
    )
    (net (code "78") (name "Net-(LED16-A)") (class "Default")
      (node (ref "H17") (pin "2") (pinfunction "2_2") (pintype "unspecified"))
      (node (ref "LED16") (pin "1") (pinfunction "A_1") (pintype "unspecified"))
    )
    (net (code "79") (name "Net-(U1-5V)") (class "Default")
      (node (ref "U1") (pin "55") (pinfunction "5V_55") (pintype "unspecified"))
      (node (ref "U46") (pin "1") (pinfunction "1_1") (pintype "input"))
      (node (ref "USB1") (pin "1") (pinfunction "VCC_1") (pintype "input"))
    )
    (net (code "80") (name "Net-(U1-R+)") (class "Default")
      (node (ref "ETHERNET1") (pin "4") (pinfunction "4_4") (pintype "unspecified"))
      (node (ref "U1") (pin "60") (pinfunction "R+_60") (pintype "bidirectional"))
      (node (ref "U47") (pin "1") (pinfunction "1_1") (pintype "input"))
    )
    (net (code "81") (name "Net-(U1-R-)") (class "Default")
      (node (ref "ETHERNET1") (pin "6") (pinfunction "6_6") (pintype "unspecified"))
      (node (ref "U1") (pin "65") (pinfunction "R-_65") (pintype "bidirectional"))
      (node (ref "U47") (pin "2") (pinfunction "2_2") (pintype "input"))
    )
    (net (code "82") (name "Net-(U1-T+)") (class "Default")
      (node (ref "ETHERNET1") (pin "1") (pinfunction "1_1") (pintype "unspecified"))
      (node (ref "U1") (pin "63") (pinfunction "T+_63") (pintype "bidirectional"))
      (node (ref "U47") (pin "6") (pinfunction "6_6") (pintype "input"))
    )
    (net (code "83") (name "Net-(U1-T-)") (class "Default")
      (node (ref "ETHERNET1") (pin "3") (pinfunction "3_3") (pintype "unspecified"))
      (node (ref "U1") (pin "62") (pinfunction "T-_62") (pintype "bidirectional"))
      (node (ref "U47") (pin "5") (pinfunction "5_5") (pintype "input"))
    )
    (net (code "84") (name "Net-(U2-A0)") (class "Default")
      (node (ref "I2C1-A0") (pin "2") (pinfunction "2_2") (pintype "unspecified"))
      (node (ref "U2") (pin "1") (pinfunction "A0_1") (pintype "unspecified"))
    )
    (net (code "85") (name "Net-(U2-A1)") (class "Default")
      (node (ref "I2C1-A1") (pin "2") (pinfunction "2_2") (pintype "unspecified"))
      (node (ref "U2") (pin "2") (pinfunction "A1_2") (pintype "unspecified"))
    )
    (net (code "86") (name "Net-(U2-A2)") (class "Default")
      (node (ref "I2C1-A2") (pin "2") (pinfunction "2_2") (pintype "unspecified"))
      (node (ref "U2") (pin "21") (pinfunction "A2_21") (pintype "unspecified"))
    )
    (net (code "87") (name "Net-(U2-SC0)") (class "Default")
      (node (ref "I2C0") (pin "3") (pinfunction "3_3") (pintype "unspecified"))
      (node (ref "R2") (pin "2") (pinfunction "2_2") (pintype "input"))
      (node (ref "U2") (pin "5") (pinfunction "SC0_5") (pintype "unspecified"))
    )
    (net (code "88") (name "Net-(U2-SC1)") (class "Default")
      (node (ref "I2C1") (pin "3") (pinfunction "3_3") (pintype "unspecified"))
      (node (ref "R4") (pin "2") (pinfunction "2_2") (pintype "input"))
      (node (ref "U2") (pin "7") (pinfunction "SC1_7") (pintype "unspecified"))
    )
    (net (code "89") (name "Net-(U2-SC2)") (class "Default")
      (node (ref "I2C2") (pin "3") (pinfunction "3_3") (pintype "unspecified"))
      (node (ref "R6") (pin "2") (pinfunction "2_2") (pintype "input"))
      (node (ref "U2") (pin "9") (pinfunction "SC2_9") (pintype "unspecified"))
    )
    (net (code "90") (name "Net-(U2-SC3)") (class "Default")
      (node (ref "I2C3") (pin "3") (pinfunction "3_3") (pintype "unspecified"))
      (node (ref "R8") (pin "2") (pinfunction "2_2") (pintype "input"))
      (node (ref "U2") (pin "11") (pinfunction "SC3_11") (pintype "unspecified"))
    )
    (net (code "91") (name "Net-(U2-SC4)") (class "Default")
      (node (ref "I2C4") (pin "3") (pinfunction "3_3") (pintype "unspecified"))
      (node (ref "R15") (pin "1") (pinfunction "1_1") (pintype "input"))
      (node (ref "U2") (pin "14") (pinfunction "SC4_14") (pintype "unspecified"))
    )
    (net (code "92") (name "Net-(U2-SC5)") (class "Default")
      (node (ref "I2C5") (pin "3") (pinfunction "3_3") (pintype "unspecified"))
      (node (ref "R13") (pin "1") (pinfunction "1_1") (pintype "input"))
      (node (ref "U2") (pin "16") (pinfunction "SC5_16") (pintype "unspecified"))
    )
    (net (code "93") (name "Net-(U2-SC6)") (class "Default")
      (node (ref "I2C6") (pin "3") (pinfunction "3_3") (pintype "unspecified"))
      (node (ref "R11") (pin "1") (pinfunction "1_1") (pintype "input"))
      (node (ref "U2") (pin "18") (pinfunction "SC6_18") (pintype "unspecified"))
    )
    (net (code "94") (name "Net-(U2-SC7)") (class "Default")
      (node (ref "I2C7") (pin "3") (pinfunction "3_3") (pintype "unspecified"))
      (node (ref "R9") (pin "1") (pinfunction "1_1") (pintype "input"))
      (node (ref "U2") (pin "20") (pinfunction "SC7_20") (pintype "unspecified"))
    )
    (net (code "95") (name "Net-(U2-SD0)") (class "Default")
      (node (ref "I2C0") (pin "4") (pinfunction "4_4") (pintype "unspecified"))
      (node (ref "R1") (pin "2") (pinfunction "2_2") (pintype "input"))
      (node (ref "U2") (pin "4") (pinfunction "SD0_4") (pintype "unspecified"))
    )
    (net (code "96") (name "Net-(U2-SD1)") (class "Default")
      (node (ref "I2C1") (pin "4") (pinfunction "4_4") (pintype "unspecified"))
      (node (ref "R3") (pin "2") (pinfunction "2_2") (pintype "input"))
      (node (ref "U2") (pin "6") (pinfunction "SD1_6") (pintype "unspecified"))
    )
    (net (code "97") (name "Net-(U2-SD2)") (class "Default")
      (node (ref "I2C2") (pin "4") (pinfunction "4_4") (pintype "unspecified"))
      (node (ref "R5") (pin "2") (pinfunction "2_2") (pintype "input"))
      (node (ref "U2") (pin "8") (pinfunction "SD2_8") (pintype "unspecified"))
    )
    (net (code "98") (name "Net-(U2-SD3)") (class "Default")
      (node (ref "I2C3") (pin "4") (pinfunction "4_4") (pintype "unspecified"))
      (node (ref "R7") (pin "2") (pinfunction "2_2") (pintype "input"))
      (node (ref "U2") (pin "10") (pinfunction "SD3_10") (pintype "unspecified"))
    )
    (net (code "99") (name "Net-(U2-SD4)") (class "Default")
      (node (ref "I2C4") (pin "4") (pinfunction "4_4") (pintype "unspecified"))
      (node (ref "R16") (pin "1") (pinfunction "1_1") (pintype "input"))
      (node (ref "U2") (pin "13") (pinfunction "SD4_13") (pintype "unspecified"))
    )
    (net (code "100") (name "Net-(U2-SD5)") (class "Default")
      (node (ref "I2C5") (pin "4") (pinfunction "4_4") (pintype "unspecified"))
      (node (ref "R14") (pin "1") (pinfunction "1_1") (pintype "input"))
      (node (ref "U2") (pin "15") (pinfunction "SD5_15") (pintype "unspecified"))
    )
    (net (code "101") (name "Net-(U2-SD6)") (class "Default")
      (node (ref "I2C6") (pin "4") (pinfunction "4_4") (pintype "unspecified"))
      (node (ref "R12") (pin "1") (pinfunction "1_1") (pintype "input"))
      (node (ref "U2") (pin "17") (pinfunction "SD6_17") (pintype "unspecified"))
    )
    (net (code "102") (name "Net-(U2-SD7)") (class "Default")
      (node (ref "I2C7") (pin "4") (pinfunction "4_4") (pintype "unspecified"))
      (node (ref "R10") (pin "1") (pinfunction "1_1") (pintype "input"))
      (node (ref "U2") (pin "19") (pinfunction "SD7_19") (pintype "unspecified"))
    )
    (net (code "103") (name "Net-(U17-A0)") (class "Default")
      (node (ref "I2CX-A0") (pin "2") (pinfunction "2_2") (pintype "unspecified"))
      (node (ref "U17") (pin "21") (pinfunction "A0_21") (pintype "input"))
    )
    (net (code "104") (name "Net-(U17-A1)") (class "Default")
      (node (ref "I2CX-A1") (pin "2") (pinfunction "2_2") (pintype "unspecified"))
      (node (ref "U17") (pin "2") (pinfunction "A1_2") (pintype "input"))
    )
    (net (code "105") (name "Net-(U17-A2)") (class "Default")
      (node (ref "I2CX-A2") (pin "2") (pinfunction "2_2") (pintype "unspecified"))
      (node (ref "U17") (pin "3") (pinfunction "A2_3") (pintype "input"))
    )
    (net (code "106") (name "Net-(U17-P10)") (class "Default")
      (node (ref "GPIO2") (pin "4") (pinfunction "4_4") (pintype "input"))
      (node (ref "RN3") (pin "8") (pinfunction "8_8") (pintype "input"))
      (node (ref "U17") (pin "13") (pinfunction "P10_13") (pintype "input"))
    )
    (net (code "107") (name "Net-(U17-P11)") (class "Default")
      (node (ref "GPIO2") (pin "3") (pinfunction "3_3") (pintype "input"))
      (node (ref "RN3") (pin "7") (pinfunction "7_7") (pintype "input"))
      (node (ref "U17") (pin "14") (pinfunction "P11_14") (pintype "input"))
    )
    (net (code "108") (name "Net-(U17-P12)") (class "Default")
      (node (ref "GPIO2") (pin "2") (pinfunction "2_2") (pintype "input"))
      (node (ref "RN3") (pin "6") (pinfunction "6_6") (pintype "input"))
      (node (ref "U17") (pin "15") (pinfunction "P12_15") (pintype "input"))
    )
    (net (code "109") (name "Net-(U17-P13)") (class "Default")
      (node (ref "GPIO2") (pin "1") (pinfunction "1_1") (pintype "input"))
      (node (ref "RN3") (pin "5") (pinfunction "5_5") (pintype "input"))
      (node (ref "U17") (pin "16") (pinfunction "P13_16") (pintype "input"))
    )
    (net (code "110") (name "Net-(U17-P14)") (class "Default")
      (node (ref "GPIO1") (pin "4") (pinfunction "4_4") (pintype "input"))
      (node (ref "RN4") (pin "8") (pinfunction "8_8") (pintype "input"))
      (node (ref "U17") (pin "17") (pinfunction "P14_17") (pintype "input"))
    )
    (net (code "111") (name "Net-(U17-P15)") (class "Default")
      (node (ref "GPIO1") (pin "3") (pinfunction "3_3") (pintype "input"))
      (node (ref "RN4") (pin "7") (pinfunction "7_7") (pintype "input"))
      (node (ref "U17") (pin "18") (pinfunction "P15_18") (pintype "input"))
    )
    (net (code "112") (name "Net-(U17-P16)") (class "Default")
      (node (ref "GPIO1") (pin "2") (pinfunction "2_2") (pintype "input"))
      (node (ref "RN4") (pin "6") (pinfunction "6_6") (pintype "input"))
      (node (ref "U17") (pin "19") (pinfunction "P16_19") (pintype "input"))
    )
    (net (code "113") (name "Net-(U17-P17)") (class "Default")
      (node (ref "GPIO1") (pin "1") (pinfunction "1_1") (pintype "input"))
      (node (ref "RN4") (pin "5") (pinfunction "5_5") (pintype "input"))
      (node (ref "U17") (pin "20") (pinfunction "P17_20") (pintype "input"))
    )
    (net (code "114") (name "Net-(U18-A0)") (class "Default")
      (node (ref "PWM-A0") (pin "2") (pinfunction "2_2") (pintype "unspecified"))
      (node (ref "U18") (pin "1") (pinfunction "A0_1") (pintype "input"))
    )
    (net (code "115") (name "Net-(U18-A1)") (class "Default")
      (node (ref "PWM-A1") (pin "2") (pinfunction "2_2") (pintype "unspecified"))
      (node (ref "U18") (pin "2") (pinfunction "A1_2") (pintype "input"))
    )
    (net (code "116") (name "Net-(U18-A2)") (class "Default")
      (node (ref "PWM-A2") (pin "2") (pinfunction "2_2") (pintype "unspecified"))
      (node (ref "U18") (pin "3") (pinfunction "A2_3") (pintype "input"))
    )
    (net (code "117") (name "Net-(U18-A3)") (class "Default")
      (node (ref "PWM-A3") (pin "2") (pinfunction "2_2") (pintype "unspecified"))
      (node (ref "U18") (pin "4") (pinfunction "A3_4") (pintype "input"))
    )
    (net (code "118") (name "Net-(U18-A4)") (class "Default")
      (node (ref "PWM-A4") (pin "2") (pinfunction "2_2") (pintype "unspecified"))
      (node (ref "U18") (pin "5") (pinfunction "A4_5") (pintype "input"))
    )
    (net (code "119") (name "Net-(U18-A5)") (class "Default")
      (node (ref "PWM-A5") (pin "2") (pinfunction "2_2") (pintype "unspecified"))
      (node (ref "U18") (pin "24") (pinfunction "A5_24") (pintype "input"))
    )
    (net (code "120") (name "Net-(U18-LED0)") (class "Default")
      (node (ref "F1") (pin "8") (pinfunction "8_8") (pintype "unspecified"))
      (node (ref "U18") (pin "6") (pinfunction "LED0_6") (pintype "input"))
    )
    (net (code "121") (name "Net-(U18-LED1)") (class "Default")
      (node (ref "F1") (pin "7") (pinfunction "7_7") (pintype "unspecified"))
      (node (ref "U18") (pin "7") (pinfunction "LED1_7") (pintype "input"))
    )
    (net (code "122") (name "Net-(U18-LED2)") (class "Default")
      (node (ref "F1") (pin "6") (pinfunction "6_6") (pintype "unspecified"))
      (node (ref "U18") (pin "8") (pinfunction "LED2_8") (pintype "input"))
    )
    (net (code "123") (name "Net-(U18-LED3)") (class "Default")
      (node (ref "F1") (pin "5") (pinfunction "5_5") (pintype "unspecified"))
      (node (ref "U18") (pin "9") (pinfunction "LED3_9") (pintype "input"))
    )
    (net (code "124") (name "Net-(U18-LED4)") (class "Default")
      (node (ref "F2") (pin "8") (pinfunction "8_8") (pintype "unspecified"))
      (node (ref "U18") (pin "10") (pinfunction "LED4_10") (pintype "input"))
    )
    (net (code "125") (name "Net-(U18-LED5)") (class "Default")
      (node (ref "F2") (pin "7") (pinfunction "7_7") (pintype "unspecified"))
      (node (ref "U18") (pin "11") (pinfunction "LED5_11") (pintype "input"))
    )
    (net (code "126") (name "Net-(U18-LED6)") (class "Default")
      (node (ref "F2") (pin "6") (pinfunction "6_6") (pintype "unspecified"))
      (node (ref "U18") (pin "12") (pinfunction "LED6_12") (pintype "input"))
    )
    (net (code "127") (name "Net-(U18-LED7)") (class "Default")
      (node (ref "F2") (pin "5") (pinfunction "5_5") (pintype "unspecified"))
      (node (ref "U18") (pin "13") (pinfunction "LED7_13") (pintype "input"))
    )
    (net (code "128") (name "Net-(U18-LED8)") (class "Default")
      (node (ref "F3") (pin "8") (pinfunction "8_8") (pintype "unspecified"))
      (node (ref "U18") (pin "15") (pinfunction "LED8_15") (pintype "input"))
    )
    (net (code "129") (name "Net-(U18-LED9)") (class "Default")
      (node (ref "F3") (pin "7") (pinfunction "7_7") (pintype "unspecified"))
      (node (ref "U18") (pin "16") (pinfunction "LED9_16") (pintype "input"))
    )
    (net (code "130") (name "Net-(U18-LED10)") (class "Default")
      (node (ref "F3") (pin "6") (pinfunction "6_6") (pintype "unspecified"))
      (node (ref "U18") (pin "17") (pinfunction "LED10_17") (pintype "input"))
    )
    (net (code "131") (name "Net-(U18-LED11)") (class "Default")
      (node (ref "F3") (pin "5") (pinfunction "5_5") (pintype "unspecified"))
      (node (ref "U18") (pin "18") (pinfunction "LED11_18") (pintype "input"))
    )
    (net (code "132") (name "Net-(U18-LED12)") (class "Default")
      (node (ref "F4") (pin "8") (pinfunction "8_8") (pintype "unspecified"))
      (node (ref "U18") (pin "19") (pinfunction "LED12_19") (pintype "input"))
    )
    (net (code "133") (name "Net-(U18-LED13)") (class "Default")
      (node (ref "F4") (pin "7") (pinfunction "7_7") (pintype "unspecified"))
      (node (ref "U18") (pin "20") (pinfunction "LED13_20") (pintype "input"))
    )
    (net (code "134") (name "Net-(U18-LED14)") (class "Default")
      (node (ref "F4") (pin "6") (pinfunction "6_6") (pintype "unspecified"))
      (node (ref "U18") (pin "21") (pinfunction "LED14_21") (pintype "input"))
    )
    (net (code "135") (name "Net-(U18-LED15)") (class "Default")
      (node (ref "F4") (pin "5") (pinfunction "5_5") (pintype "unspecified"))
      (node (ref "U18") (pin "22") (pinfunction "LED15_22") (pintype "input"))
    )
    (net (code "136") (name "Net-(U35-B3)") (class "Default")
      (node (ref "SONAR1") (pin "3") (pinfunction "3_3") (pintype "unspecified"))
      (node (ref "U35") (pin "13") (pinfunction "B3_13") (pintype "unspecified"))
    )
    (net (code "137") (name "Net-(U35-B4)") (class "Default")
      (node (ref "SONAR1") (pin "4") (pinfunction "4_4") (pintype "unspecified"))
      (node (ref "U35") (pin "12") (pinfunction "B4_12") (pintype "unspecified"))
    )
    (net (code "138") (name "Net-(U35-B5)") (class "Default")
      (node (ref "SONAR0") (pin "3") (pinfunction "3_3") (pintype "unspecified"))
      (node (ref "U35") (pin "11") (pinfunction "B5_11") (pintype "unspecified"))
    )
    (net (code "139") (name "Net-(U35-B6)") (class "Default")
      (node (ref "SONAR0") (pin "4") (pinfunction "4_4") (pintype "unspecified"))
      (node (ref "U35") (pin "10") (pinfunction "B6_10") (pintype "unspecified"))
    )
    (net (code "140") (name "Net-(U36-B3)") (class "Default")
      (node (ref "SONAR3") (pin "3") (pinfunction "3_3") (pintype "unspecified"))
      (node (ref "U36") (pin "13") (pinfunction "B3_13") (pintype "unspecified"))
    )
    (net (code "141") (name "Net-(U36-B4)") (class "Default")
      (node (ref "SONAR3") (pin "4") (pinfunction "4_4") (pintype "unspecified"))
      (node (ref "U36") (pin "12") (pinfunction "B4_12") (pintype "unspecified"))
    )
    (net (code "142") (name "Net-(U36-B5)") (class "Default")
      (node (ref "SONAR2") (pin "3") (pinfunction "3_3") (pintype "unspecified"))
      (node (ref "U36") (pin "11") (pinfunction "B5_11") (pintype "unspecified"))
    )
    (net (code "143") (name "Net-(U36-B6)") (class "Default")
      (node (ref "SONAR2") (pin "4") (pinfunction "4_4") (pintype "unspecified"))
      (node (ref "U36") (pin "10") (pinfunction "B6_10") (pintype "unspecified"))
    )
    (net (code "144") (name "Net-(U39-A0)") (class "Default")
      (node (ref "CN63") (pin "3") (pinfunction "3_3") (pintype "unspecified"))
      (node (ref "U39") (pin "13") (pinfunction "A0_13") (pintype "unspecified"))
    )
    (net (code "145") (name "Net-(U39-A1)") (class "Default")
      (node (ref "CN62") (pin "3") (pinfunction "3_3") (pintype "unspecified"))
      (node (ref "U39") (pin "14") (pinfunction "A1_14") (pintype "unspecified"))
    )
    (net (code "146") (name "Net-(U39-A2)") (class "Default")
      (node (ref "CN61") (pin "3") (pinfunction "3_3") (pintype "unspecified"))
      (node (ref "U39") (pin "15") (pinfunction "A2_15") (pintype "unspecified"))
    )
    (net (code "147") (name "Net-(U39-A3)") (class "Default")
      (node (ref "CN60") (pin "3") (pinfunction "3_3") (pintype "unspecified"))
      (node (ref "U39") (pin "12") (pinfunction "A3_12") (pintype "unspecified"))
    )
    (net (code "148") (name "Net-(U39-A4)") (class "Default")
      (node (ref "CN59") (pin "3") (pinfunction "3_3") (pintype "unspecified"))
      (node (ref "U39") (pin "1") (pinfunction "A4_1") (pintype "unspecified"))
    )
    (net (code "149") (name "Net-(U39-A5)") (class "Default")
      (node (ref "CN58") (pin "3") (pinfunction "3_3") (pintype "unspecified"))
      (node (ref "U39") (pin "5") (pinfunction "A5_5") (pintype "unspecified"))
    )
    (net (code "150") (name "Net-(U39-A6)") (class "Default")
      (node (ref "CN57") (pin "3") (pinfunction "3_3") (pintype "unspecified"))
      (node (ref "U39") (pin "2") (pinfunction "A6_2") (pintype "unspecified"))
    )
    (net (code "151") (name "Net-(U39-A7)") (class "Default")
      (node (ref "CN56") (pin "3") (pinfunction "3_3") (pintype "unspecified"))
      (node (ref "U39") (pin "4") (pinfunction "A7_4") (pintype "unspecified"))
    )
    (net (code "152") (name "Net-(USB1-D+)") (class "Default")
      (node (ref "U1") (pin "57") (pinfunction "D+_57") (pintype "bidirectional"))
      (node (ref "U46") (pin "3") (pinfunction "3_3") (pintype "input"))
      (node (ref "USB1") (pin "3") (pinfunction "D+_3") (pintype "input"))
    )
    (net (code "153") (name "Net-(USB1-D-)") (class "Default")
      (node (ref "U1") (pin "56") (pinfunction "D-_56") (pintype "bidirectional"))
      (node (ref "U46") (pin "2") (pinfunction "2_2") (pintype "input"))
      (node (ref "USB1") (pin "2") (pinfunction "D-_2") (pintype "input"))
    )
    (net (code "154") (name "ON_OFF") (class "Default")
      (node (ref "H18") (pin "4") (pinfunction "4_4") (pintype "unspecified"))
      (node (ref "U1") (pin "54") (pinfunction "ON_OFF_54") (pintype "input"))
      (node (ref "U48") (pin "1") (pinfunction "1_1") (pintype "input"))
    )
    (net (code "155") (name "OUT1C") (class "Default")
      (node (ref "U1") (pin "11") (pinfunction "9_OUT1C_11") (pintype "bidirectional"))
      (node (ref "U44") (pin "11") (pinfunction "11_11") (pintype "unspecified"))
      (node (ref "U5") (pin "5") (pinfunction "5_5") (pintype "unspecified"))
    )
    (net (code "156") (name "OUT1D") (class "Default")
      (node (ref "U1") (pin "8") (pinfunction "6_OUT1D_8") (pintype "bidirectional"))
      (node (ref "U44") (pin "8") (pinfunction "8_8") (pintype "unspecified"))
      (node (ref "U49") (pin "5") (pinfunction "5_5") (pintype "unspecified"))
    )
    (net (code "157") (name "OUT2") (class "Default")
      (node (ref "U1") (pin "4") (pinfunction "2_OUT2_4") (pintype "bidirectional"))
      (node (ref "U44") (pin "4") (pinfunction "4_4") (pintype "unspecified"))
      (node (ref "U6") (pin "5") (pinfunction "5_5") (pintype "unspecified"))
    )
    (net (code "158") (name "PROGRAM") (class "Default")
      (node (ref "H18") (pin "2") (pinfunction "2_2") (pintype "unspecified"))
      (node (ref "U1") (pin "53") (pinfunction "PROGRAM_53") (pintype "input"))
      (node (ref "U48") (pin "2") (pinfunction "2_2") (pintype "input"))
    )
    (net (code "159") (name "PWM-OE") (class "Default")
      (node (ref "RN1") (pin "6") (pinfunction "6_6") (pintype "input"))
      (node (ref "U17") (pin "6") (pinfunction "P02_6") (pintype "input"))
      (node (ref "U18") (pin "23") (pinfunction "OE#_23") (pintype "input"))
    )
    (net (code "160") (name "RX1") (class "Default")
      (node (ref "U1") (pin "2") (pinfunction "0_RX1_CRX2_CS1_2") (pintype "bidirectional"))
      (node (ref "U44") (pin "2") (pinfunction "2_2") (pintype "unspecified"))
      (node (ref "U6") (pin "3") (pinfunction "3_3") (pintype "unspecified"))
    )
    (net (code "161") (name "RX2") (class "Default")
      (node (ref "U1") (pin "9") (pinfunction "7_RX2_OUT1A_9") (pintype "bidirectional"))
      (node (ref "U44") (pin "9") (pinfunction "9_9") (pintype "unspecified"))
      (node (ref "U49") (pin "8") (pinfunction "8_8") (pintype "unspecified"))
    )
    (net (code "162") (name "RX5") (class "Default")
      (node (ref "U1") (pin "43") (pinfunction "21_A7_RX5_BCLK1_43") (pintype "bidirectional"))
      (node (ref "U42") (pin "3") (pinfunction "3_3") (pintype "unspecified"))
      (node (ref "U43") (pin "6") (pinfunction "6_6") (pintype "unspecified"))
    )
    (net (code "163") (name "RX7") (class "Default")
      (node (ref "U1") (pin "20") (pinfunction "28_RX7_20") (pintype "bidirectional"))
      (node (ref "U44") (pin "20") (pinfunction "20_20") (pintype "unspecified"))
      (node (ref "U5") (pin "3") (pinfunction "3_3") (pintype "unspecified"))
    )
    (net (code "164") (name "SCK") (class "Default")
      (node (ref "U1") (pin "35") (pinfunction "13_SCK_LED_35") (pintype "bidirectional"))
      (node (ref "U4") (pin "5") (pinfunction "5_5") (pintype "unspecified"))
      (node (ref "U43") (pin "14") (pinfunction "14_14") (pintype "unspecified"))
      (node (ref "U8") (pin "5") (pinfunction "5_5") (pintype "unspecified"))
    )
    (net (code "165") (name "SCK1") (class "Default")
      (node (ref "U1") (pin "19") (pinfunction "27_A13_SCK1_19") (pintype "bidirectional"))
      (node (ref "U40") (pin "5") (pinfunction "5_5") (pintype "unspecified"))
      (node (ref "U41") (pin "5") (pinfunction "5_5") (pintype "unspecified"))
      (node (ref "U44") (pin "19") (pinfunction "19_19") (pintype "unspecified"))
    )
    (net (code "166") (name "SCL") (class "Default")
      (node (ref "R17") (pin "1") (pinfunction "1_1") (pintype "input"))
      (node (ref "U1") (pin "41") (pinfunction "19_A5_SCL_41") (pintype "bidirectional"))
      (node (ref "U17") (pin "22") (pinfunction "SCL_22") (pintype "input"))
      (node (ref "U18") (pin "26") (pinfunction "SCL_26") (pintype "input"))
      (node (ref "U2") (pin "22") (pinfunction "SCL_22") (pintype "unspecified"))
      (node (ref "U43") (pin "8") (pinfunction "8_8") (pintype "unspecified"))
    )
    (net (code "167") (name "SCL1") (class "Default")
      (node (ref "U1") (pin "38") (pinfunction "16_A2_RX4_SCL1_38") (pintype "bidirectional"))
      (node (ref "U43") (pin "11") (pinfunction "11_11") (pintype "unspecified"))
      (node (ref "U50") (pin "8") (pinfunction "8_8") (pintype "unspecified"))
    )
    (net (code "168") (name "SCL2") (class "Default")
      (node (ref "CN11") (pin "3") (pinfunction "3_3") (pintype "unspecified"))
      (node (ref "CN12") (pin "3") (pinfunction "3_3") (pintype "unspecified"))
      (node (ref "U1") (pin "16") (pinfunction "24_A10_TX6_SCL2_16") (pintype "bidirectional"))
      (node (ref "U44") (pin "16") (pinfunction "16_16") (pintype "unspecified"))
    )
    (net (code "169") (name "SDA") (class "Default")
      (node (ref "R18") (pin "1") (pinfunction "1_1") (pintype "input"))
      (node (ref "U1") (pin "40") (pinfunction "18_A4_SDA_40") (pintype "bidirectional"))
      (node (ref "U17") (pin "23") (pinfunction "SDA_23") (pintype "input"))
      (node (ref "U18") (pin "27") (pinfunction "SDA_27") (pintype "input"))
      (node (ref "U2") (pin "23") (pinfunction "SDA_23") (pintype "unspecified"))
      (node (ref "U43") (pin "9") (pinfunction "9_9") (pintype "unspecified"))
    )
    (net (code "170") (name "SDA1") (class "Default")
      (node (ref "U1") (pin "39") (pinfunction "17_A3_TX4_SDA1_39") (pintype "bidirectional"))
      (node (ref "U43") (pin "10") (pinfunction "10_10") (pintype "unspecified"))
      (node (ref "U50") (pin "11") (pinfunction "11_11") (pintype "unspecified"))
    )
    (net (code "171") (name "SDA2") (class "Default")
      (node (ref "CN11") (pin "4") (pinfunction "4_4") (pintype "unspecified"))
      (node (ref "CN12") (pin "4") (pinfunction "4_4") (pintype "unspecified"))
      (node (ref "U1") (pin "17") (pinfunction "25_A11_RX6_SDA2_17") (pintype "bidirectional"))
      (node (ref "U44") (pin "17") (pinfunction "17_17") (pintype "unspecified"))
    )
    (net (code "172") (name "SPI0-SEL") (class "Default")
      (node (ref "RN1") (pin "5") (pinfunction "5_5") (pintype "input"))
      (node (ref "U17") (pin "7") (pinfunction "P03_7") (pintype "input"))
      (node (ref "U8") (pin "6") (pinfunction "6_6") (pintype "unspecified"))
    )
    (net (code "173") (name "SPI1-SEL") (class "Default")
      (node (ref "RN2") (pin "8") (pinfunction "8_8") (pintype "input"))
      (node (ref "U17") (pin "8") (pinfunction "P04_8") (pintype "input"))
      (node (ref "U4") (pin "6") (pinfunction "6_6") (pintype "unspecified"))
    )
    (net (code "174") (name "SPI2-SEL") (class "Default")
      (node (ref "RN2") (pin "7") (pinfunction "7_7") (pintype "input"))
      (node (ref "U17") (pin "9") (pinfunction "P05_9") (pintype "input"))
      (node (ref "U41") (pin "6") (pinfunction "6_6") (pintype "unspecified"))
    )
    (net (code "175") (name "SPI3-SEL") (class "Default")
      (node (ref "RN2") (pin "6") (pinfunction "6_6") (pintype "input"))
      (node (ref "U17") (pin "10") (pinfunction "P06_10") (pintype "input"))
      (node (ref "U40") (pin "6") (pinfunction "6_6") (pintype "unspecified"))
    )
    (net (code "176") (name "TRIG0") (class "Default")
      (node (ref "U1") (pin "23") (pinfunction "31_CTX3_23") (pintype "bidirectional"))
      (node (ref "U35") (pin "6") (pinfunction "A5_6") (pintype "unspecified"))
      (node (ref "U44") (pin "23") (pinfunction "23_23") (pintype "unspecified"))
    )
    (net (code "177") (name "TRIG1") (class "Default")
      (node (ref "U1") (pin "25") (pinfunction "33_MCLK2_25") (pintype "bidirectional"))
      (node (ref "U35") (pin "4") (pinfunction "A3_4") (pintype "unspecified"))
      (node (ref "U43") (pin "24") (pinfunction "24_24") (pintype "unspecified"))
    )
    (net (code "178") (name "TRIG2") (class "Default")
      (node (ref "U1") (pin "27") (pinfunction "35_TX8_27") (pintype "bidirectional"))
      (node (ref "U36") (pin "6") (pinfunction "A5_6") (pintype "unspecified"))
      (node (ref "U43") (pin "22") (pinfunction "22_22") (pintype "unspecified"))
    )
    (net (code "179") (name "TRIG3") (class "Default")
      (node (ref "U1") (pin "29") (pinfunction "37_CS_29") (pintype "bidirectional"))
      (node (ref "U36") (pin "4") (pinfunction "A3_4") (pintype "unspecified"))
      (node (ref "U43") (pin "20") (pinfunction "20_20") (pintype "unspecified"))
    )
    (net (code "180") (name "TX1") (class "Default")
      (node (ref "U1") (pin "3") (pinfunction "1_TX1_CTX2_MISO1_3") (pintype "bidirectional"))
      (node (ref "U44") (pin "3") (pinfunction "3_3") (pintype "unspecified"))
      (node (ref "U6") (pin "4") (pinfunction "4_4") (pintype "unspecified"))
    )
    (net (code "181") (name "TX2") (class "Default")
      (node (ref "U1") (pin "10") (pinfunction "8_TX2_IN1_10") (pintype "bidirectional"))
      (node (ref "U44") (pin "10") (pinfunction "10_10") (pintype "unspecified"))
      (node (ref "U49") (pin "11") (pinfunction "11_11") (pintype "unspecified"))
    )
    (net (code "182") (name "TX5") (class "Default")
      (node (ref "U1") (pin "42") (pinfunction "20_A6_TX5_LRCLK1_42") (pintype "bidirectional"))
      (node (ref "U42") (pin "4") (pinfunction "4_4") (pintype "unspecified"))
      (node (ref "U43") (pin "7") (pinfunction "7_7") (pintype "unspecified"))
    )
    (net (code "183") (name "TX7") (class "Default")
      (node (ref "U1") (pin "21") (pinfunction "29_TX7_21") (pintype "bidirectional"))
      (node (ref "U44") (pin "21") (pinfunction "21_21") (pintype "unspecified"))
      (node (ref "U5") (pin "4") (pinfunction "4_4") (pintype "unspecified"))
    )
    (net (code "184") (name "VBAT") (class "Default")
      (node (ref "CR2032") (pin "1") (pinfunction "1_1") (pintype "input"))
      (node (ref "U1") (pin "50") (pinfunction "VBAT_50") (pintype "unspecified"))
      (node (ref "U48") (pin "5") (pinfunction "5_5") (pintype "input"))
    )
    (net (code "185") (name "VIN") (class "Default")
      (node (ref "5VEXT1") (pin "2") (pinfunction "2_2") (pintype "input"))
      (node (ref "C2") (pin "1") (pinfunction "1_1") (pintype "input"))
      (node (ref "SONAR0") (pin "1") (pinfunction "1_1") (pintype "unspecified"))
      (node (ref "SONAR1") (pin "1") (pinfunction "1_1") (pintype "unspecified"))
      (node (ref "SONAR2") (pin "1") (pinfunction "1_1") (pintype "unspecified"))
      (node (ref "SONAR3") (pin "1") (pinfunction "1_1") (pintype "unspecified"))
      (node (ref "U1") (pin "48") (pinfunction "VIN_48") (pintype "unspecified"))
      (node (ref "U19") (pin "3") (pinfunction "3_3") (pintype "unspecified"))
      (node (ref "U20") (pin "3") (pinfunction "3_3") (pintype "unspecified"))
      (node (ref "U21") (pin "3") (pinfunction "3_3") (pintype "unspecified"))
      (node (ref "U22") (pin "3") (pinfunction "3_3") (pintype "unspecified"))
      (node (ref "U23") (pin "3") (pinfunction "3_3") (pintype "unspecified"))
      (node (ref "U24") (pin "3") (pinfunction "3_3") (pintype "unspecified"))
      (node (ref "U25") (pin "3") (pinfunction "3_3") (pintype "unspecified"))
      (node (ref "U26") (pin "3") (pinfunction "3_3") (pintype "unspecified"))
      (node (ref "U27") (pin "3") (pinfunction "3_3") (pintype "unspecified"))
      (node (ref "U28") (pin "3") (pinfunction "3_3") (pintype "unspecified"))
      (node (ref "U29") (pin "3") (pinfunction "3_3") (pintype "unspecified"))
      (node (ref "U30") (pin "3") (pinfunction "3_3") (pintype "unspecified"))
      (node (ref "U31") (pin "3") (pinfunction "3_3") (pintype "unspecified"))
      (node (ref "U32") (pin "3") (pinfunction "3_3") (pintype "unspecified"))
      (node (ref "U33") (pin "3") (pinfunction "3_3") (pintype "unspecified"))
      (node (ref "U34") (pin "3") (pinfunction "3_3") (pintype "unspecified"))
      (node (ref "U35") (pin "15") (pinfunction "VCCB_15") (pintype "unspecified"))
      (node (ref "U35") (pin "8") (pinfunction "OE_8") (pintype "unspecified"))
      (node (ref "U36") (pin "15") (pinfunction "VCCB_15") (pintype "unspecified"))
      (node (ref "U36") (pin "8") (pinfunction "OE_8") (pintype "unspecified"))
      (node (ref "U4") (pin "1") (pinfunction "1_1") (pintype "unspecified"))
      (node (ref "U40") (pin "1") (pinfunction "1_1") (pintype "unspecified"))
      (node (ref "U41") (pin "1") (pinfunction "1_1") (pintype "unspecified"))
      (node (ref "U43") (pin "1") (pinfunction "1_1") (pintype "unspecified"))
      (node (ref "U8") (pin "1") (pinfunction "1_1") (pintype "unspecified"))
    )
    (net (code "186") (name "unconnected-(ETHERNET1-GND-Pad13)") (class "Default")
      (node (ref "ETHERNET1") (pin "13") (pinfunction "GND_13") (pintype "unspecified+no_connect"))
    )
    (net (code "187") (name "unconnected-(ETHERNET1-GND-Pad14)") (class "Default")
      (node (ref "ETHERNET1") (pin "14") (pinfunction "GND_14") (pintype "unspecified+no_connect"))
    )
    (net (code "188") (name "unconnected-(ETHERNET1-Pad7)") (class "Default")
      (node (ref "ETHERNET1") (pin "7") (pinfunction "7_7") (pintype "unspecified+no_connect"))
    )
    (net (code "189") (name "unconnected-(ETHERNET1-RLED+-Pad12)") (class "Default")
      (node (ref "ETHERNET1") (pin "12") (pinfunction "RLED+_12") (pintype "unspecified+no_connect"))
    )
    (net (code "190") (name "unconnected-(ETHERNET1-RLED--Pad11)") (class "Default")
      (node (ref "ETHERNET1") (pin "11") (pinfunction "RLED-_11") (pintype "unspecified+no_connect"))
    )
    (net (code "191") (name "unconnected-(U1-D+-Pad67)") (class "Default")
      (node (ref "U1") (pin "67") (pinfunction "D+_67") (pintype "bidirectional+no_connect"))
    )
    (net (code "192") (name "unconnected-(U1-D--Pad66)") (class "Default")
      (node (ref "U1") (pin "66") (pinfunction "D-_66") (pintype "bidirectional+no_connect"))
    )
    (net (code "193") (name "unconnected-(U1-VUSB-Pad49)") (class "Default")
      (node (ref "U1") (pin "49") (pinfunction "VUSB_49") (pintype "unspecified+no_connect"))
    )
    (net (code "194") (name "unconnected-(U35-A1-Pad1)") (class "Default")
      (node (ref "U35") (pin "1") (pinfunction "A1_1") (pintype "unspecified+no_connect"))
    )
    (net (code "195") (name "unconnected-(U35-A2-Pad3)") (class "Default")
      (node (ref "U35") (pin "3") (pinfunction "A2_3") (pintype "unspecified+no_connect"))
    )
    (net (code "196") (name "unconnected-(U35-B1-Pad16)") (class "Default")
      (node (ref "U35") (pin "16") (pinfunction "B1_16") (pintype "unspecified+no_connect"))
    )
    (net (code "197") (name "unconnected-(U35-B2-Pad14)") (class "Default")
      (node (ref "U35") (pin "14") (pinfunction "B2_14") (pintype "unspecified+no_connect"))
    )
    (net (code "198") (name "unconnected-(U36-A1-Pad1)") (class "Default")
      (node (ref "U36") (pin "1") (pinfunction "A1_1") (pintype "unspecified+no_connect"))
    )
    (net (code "199") (name "unconnected-(U36-A2-Pad3)") (class "Default")
      (node (ref "U36") (pin "3") (pinfunction "A2_3") (pintype "unspecified+no_connect"))
    )
    (net (code "200") (name "unconnected-(U36-B1-Pad16)") (class "Default")
      (node (ref "U36") (pin "16") (pinfunction "B1_16") (pintype "unspecified+no_connect"))
    )
    (net (code "201") (name "unconnected-(U36-B2-Pad14)") (class "Default")
      (node (ref "U36") (pin "14") (pinfunction "B2_14") (pintype "unspecified+no_connect"))
    )
  )
)
